# Main_Board.net
KiCad netlist of a schematic drawn in EAGLE
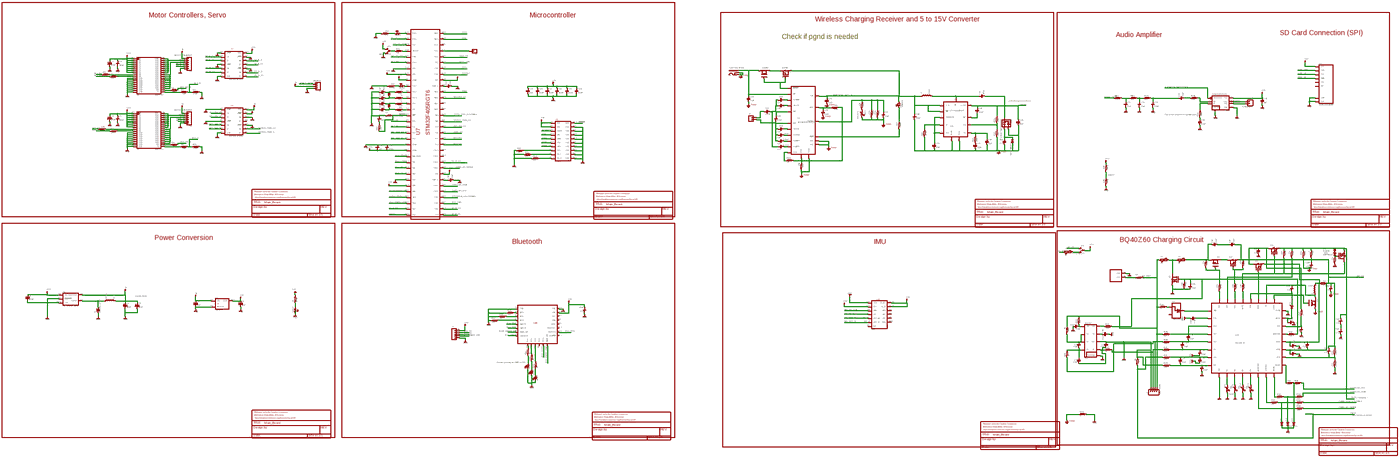
[diagram p0: schematic, sheet 1, overview]
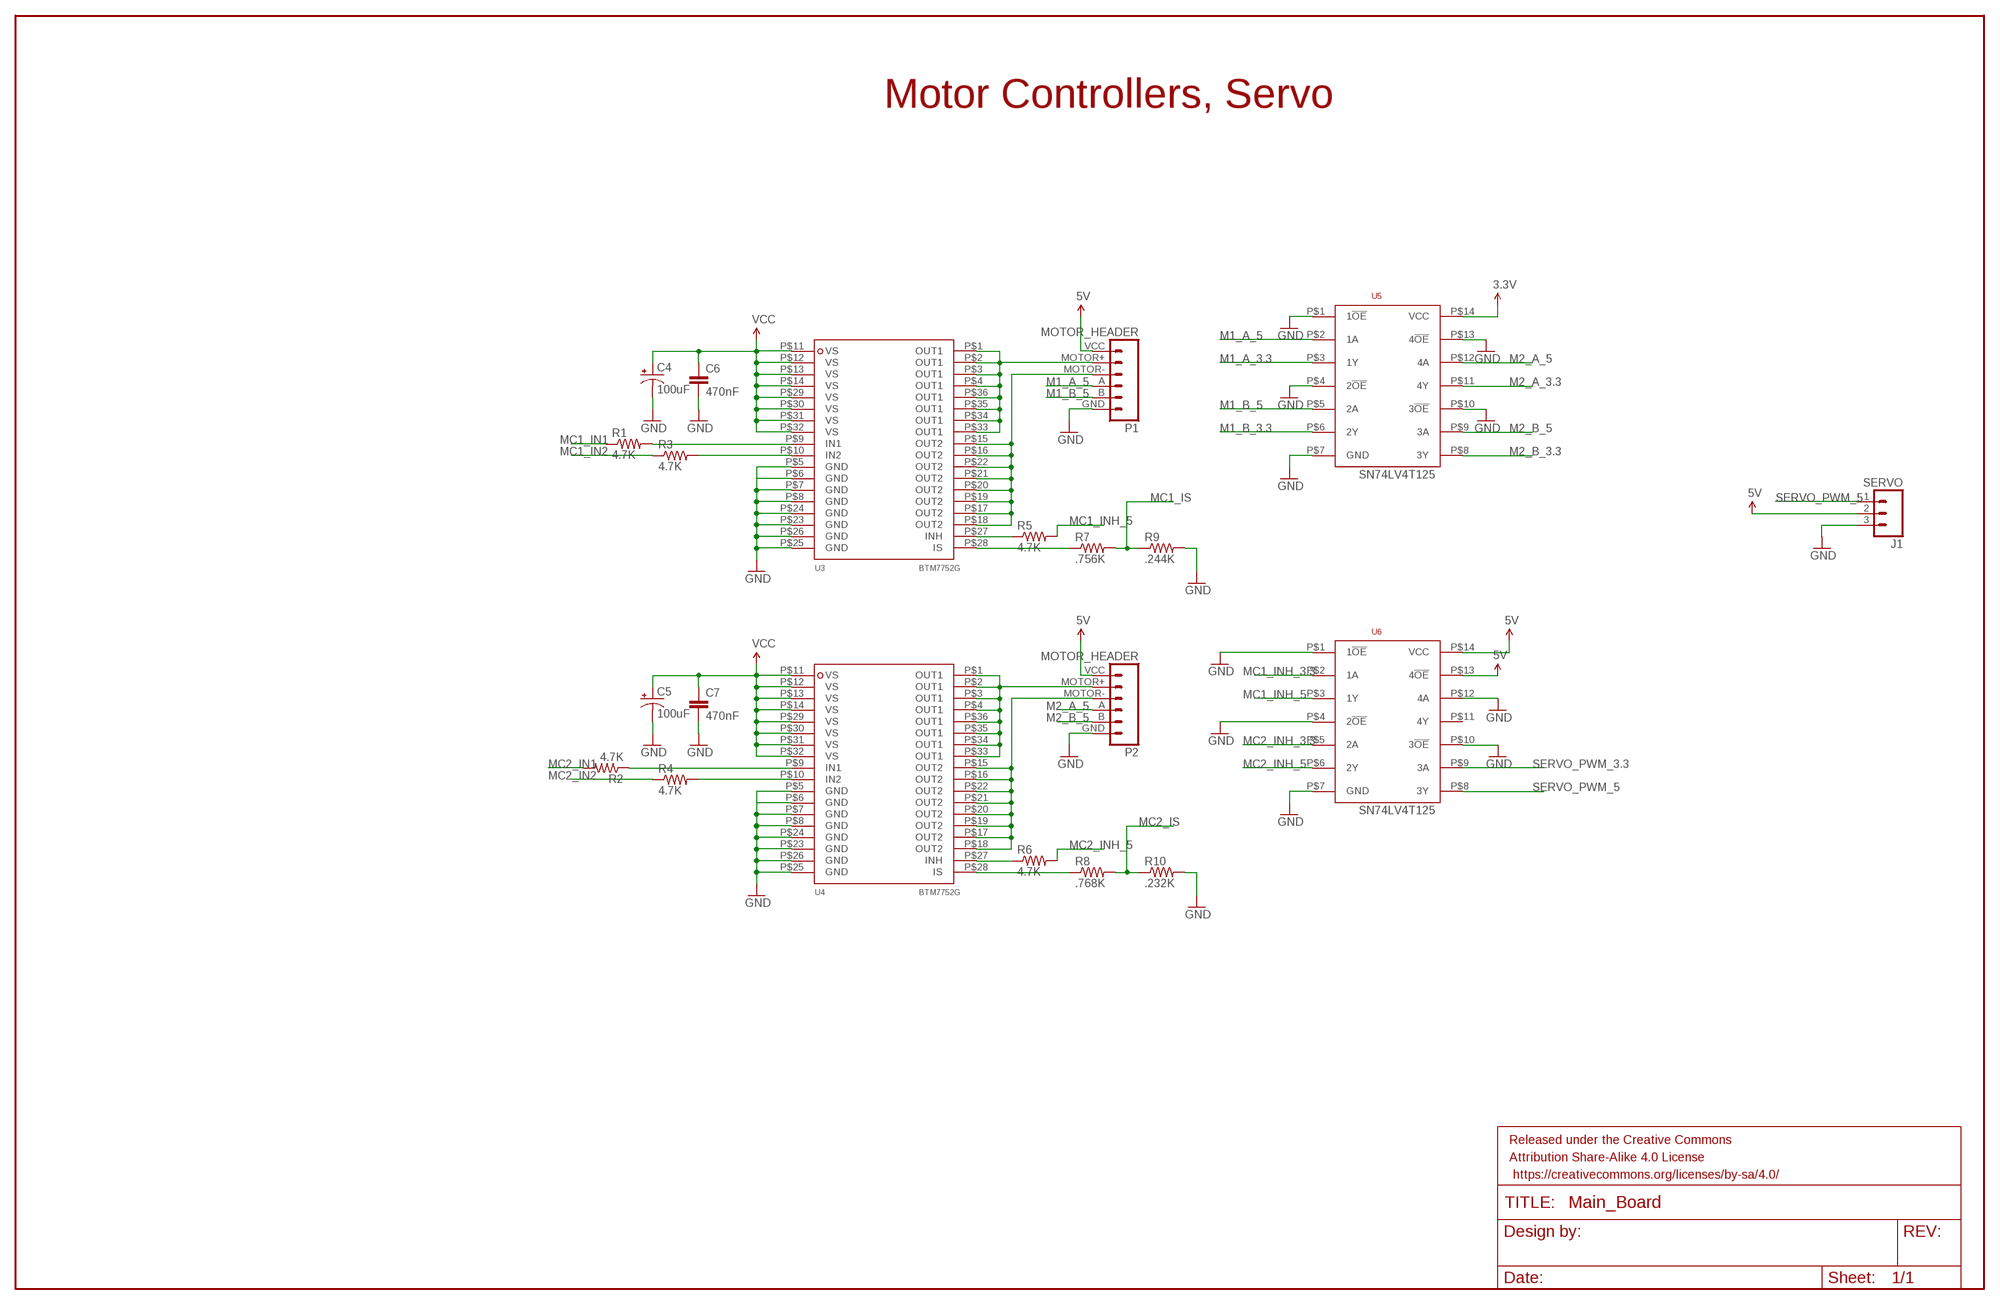
[diagram p1: schematic, sheet 1, part 1 of 8]
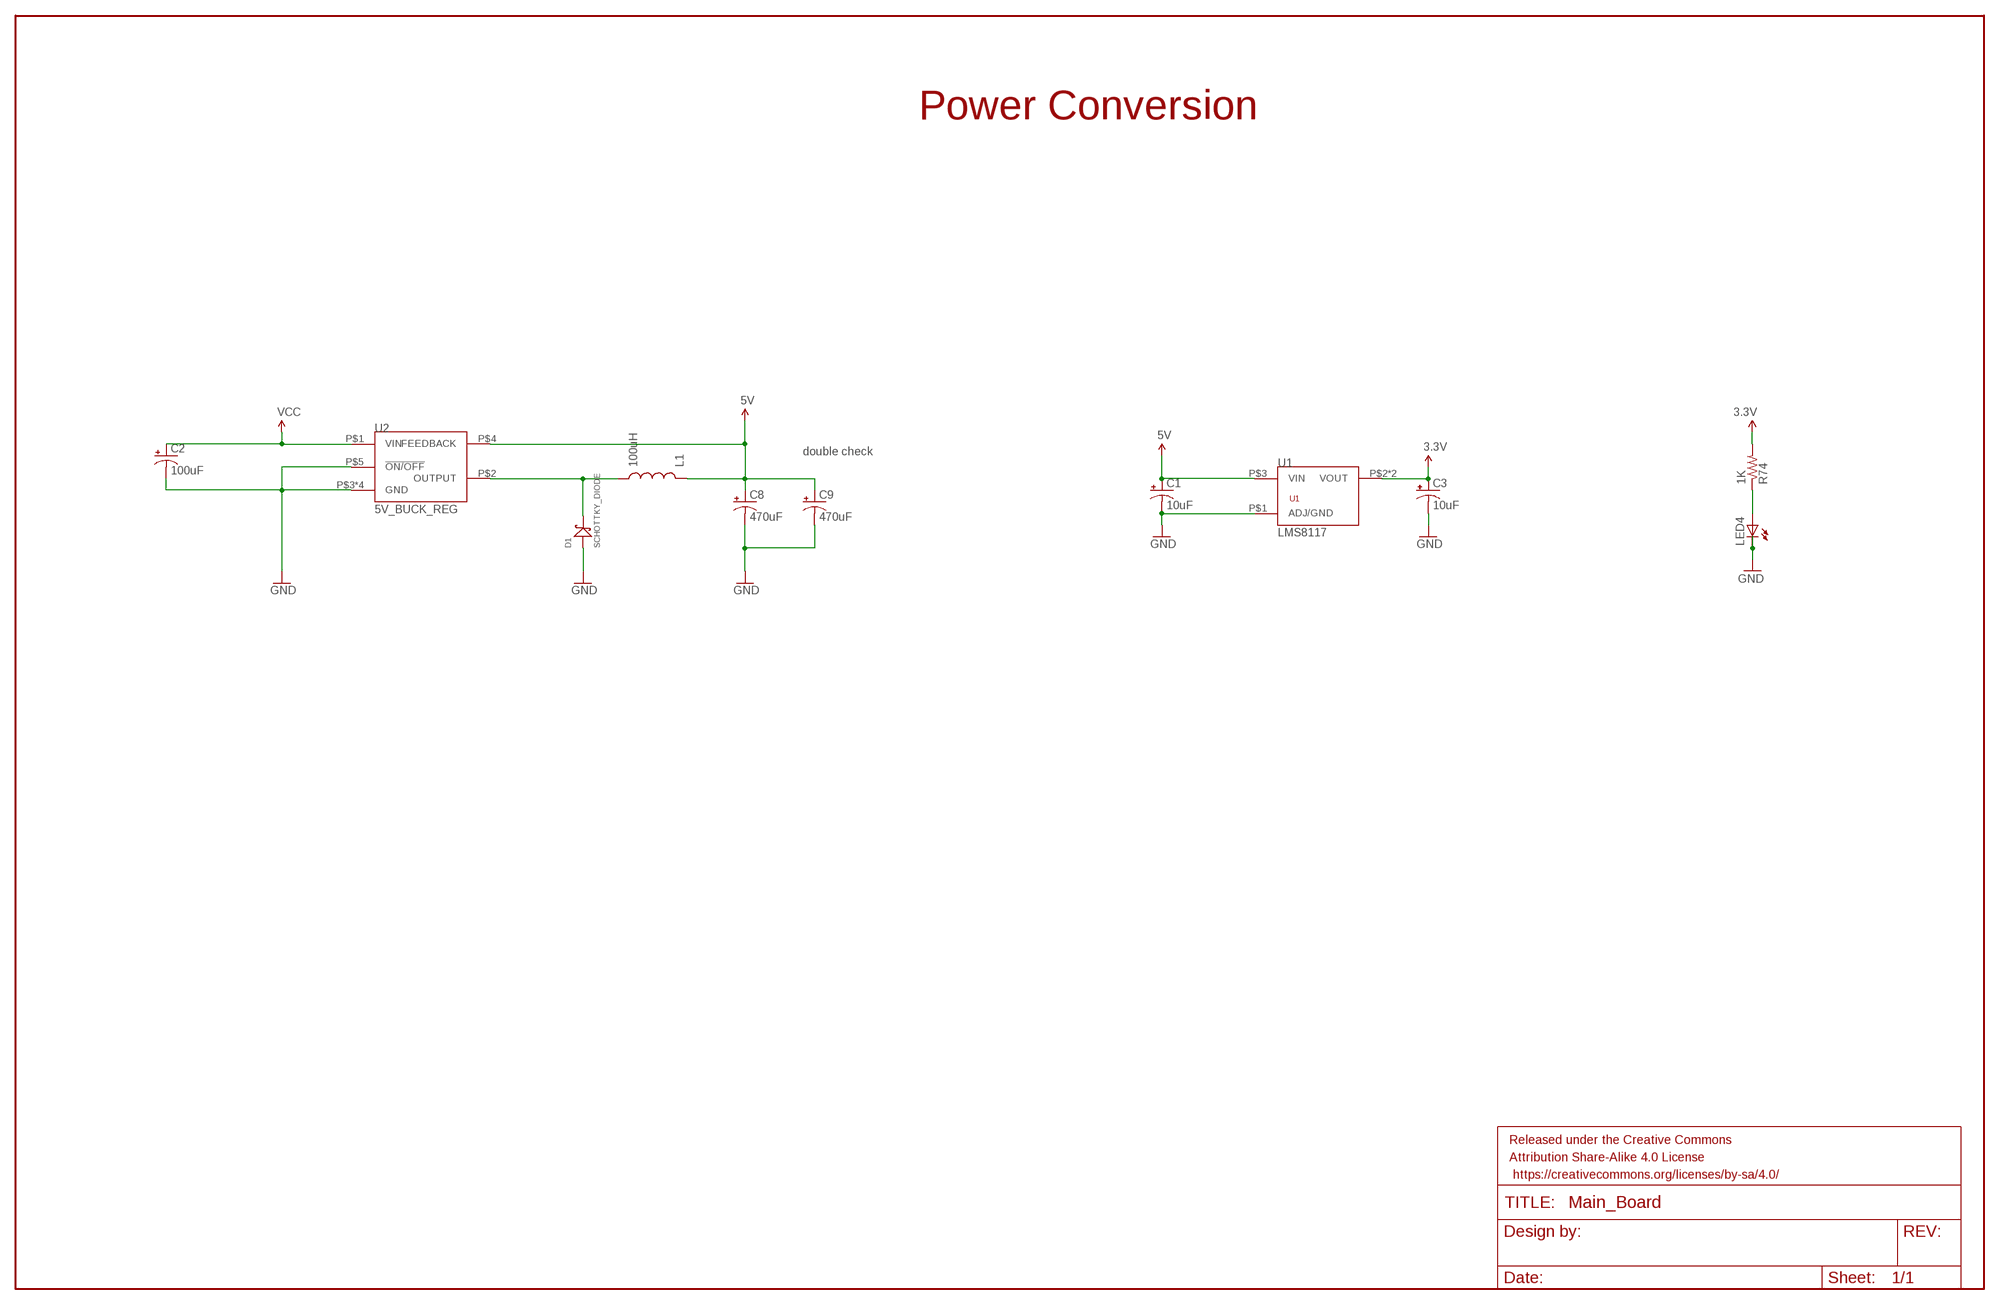
[diagram p2: schematic, sheet 1, part 2 of 8]
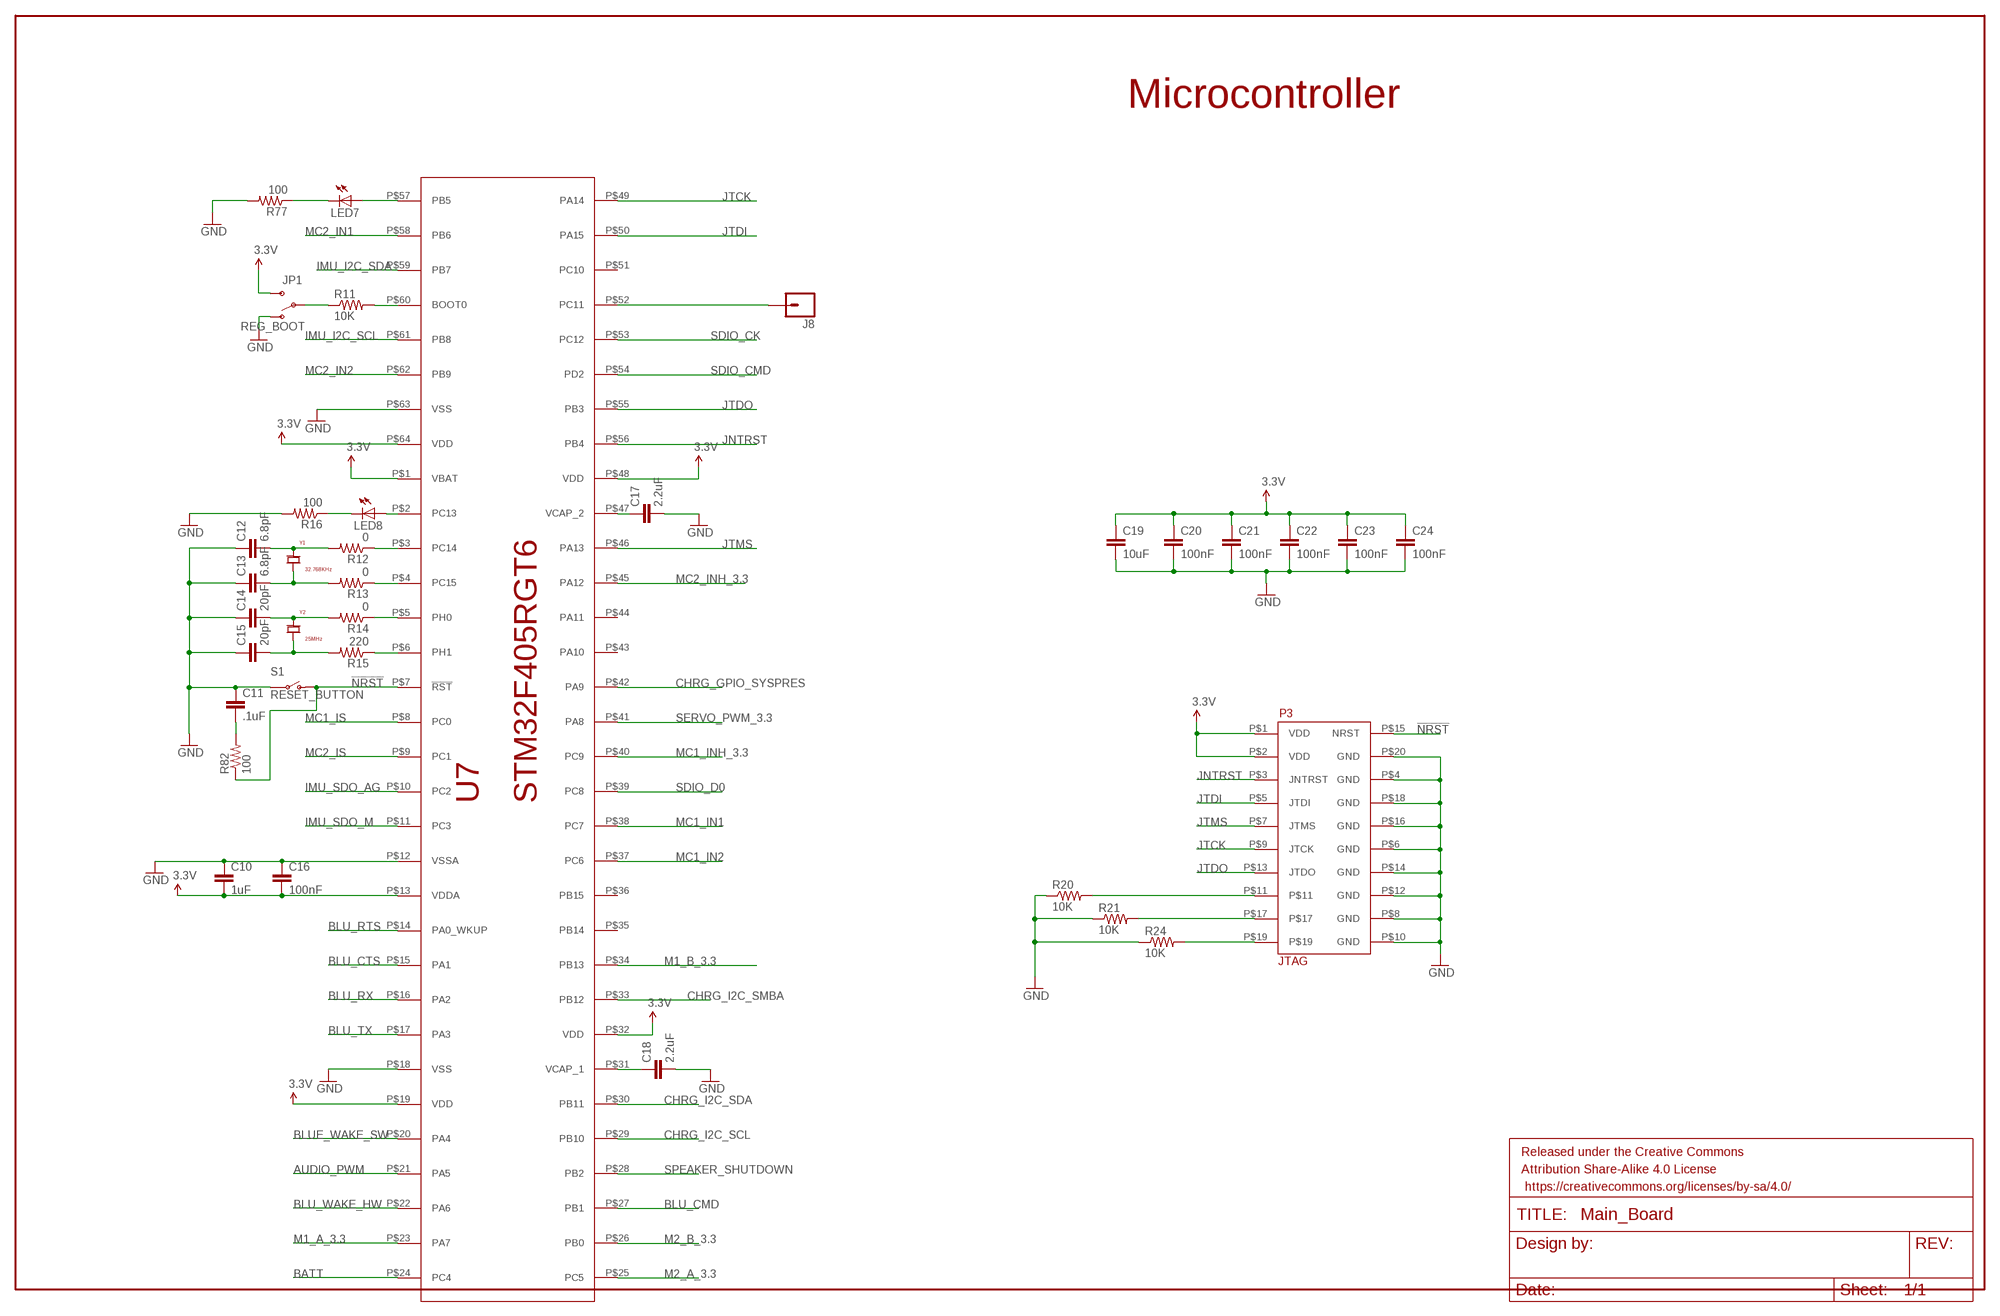
[diagram p3: schematic, sheet 1, part 3 of 8]
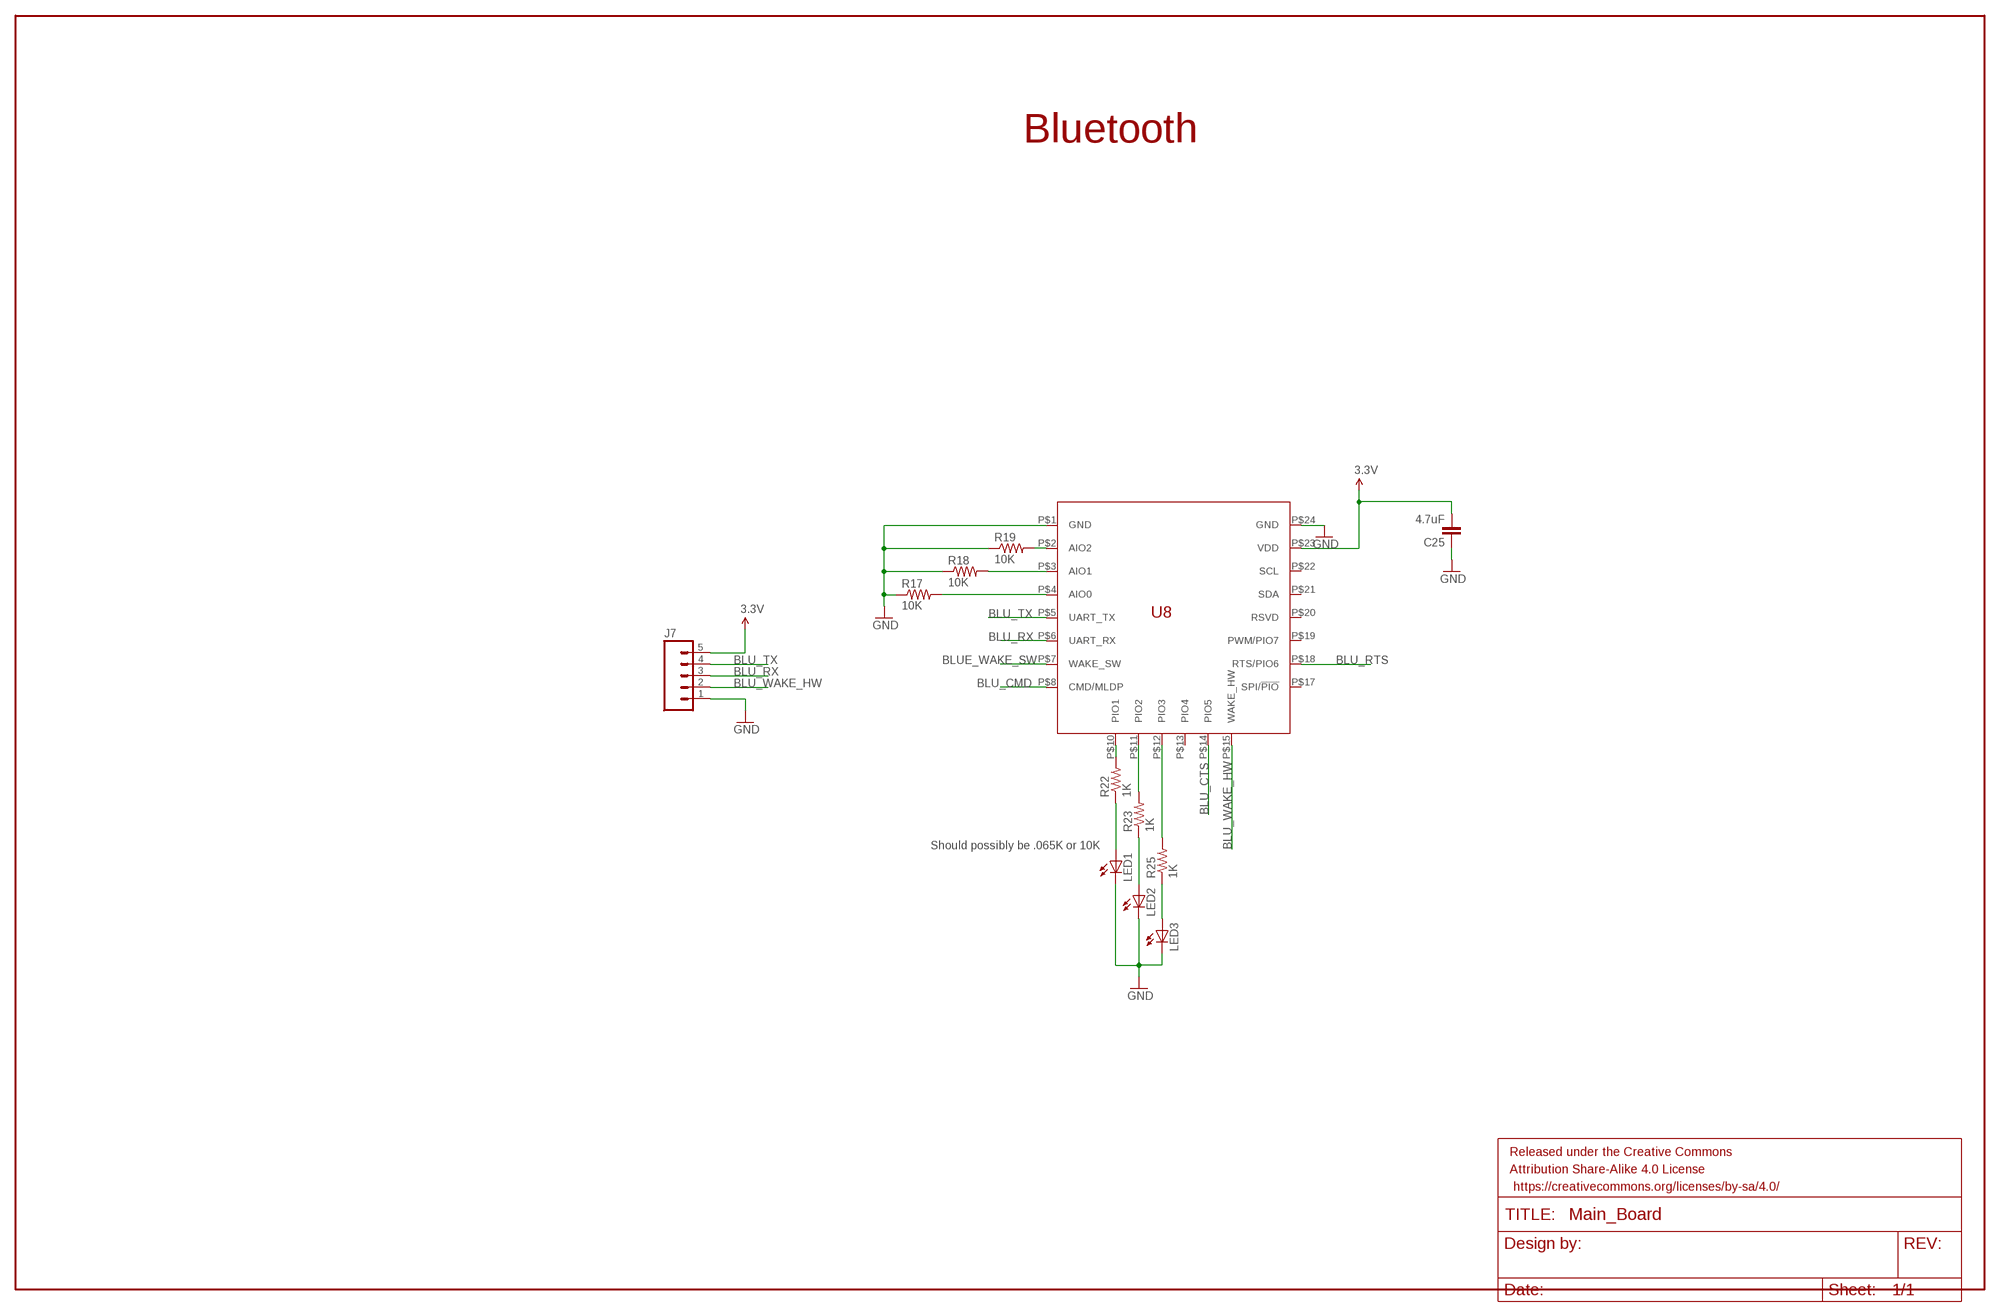
[diagram p4: schematic, sheet 1, part 4 of 8]
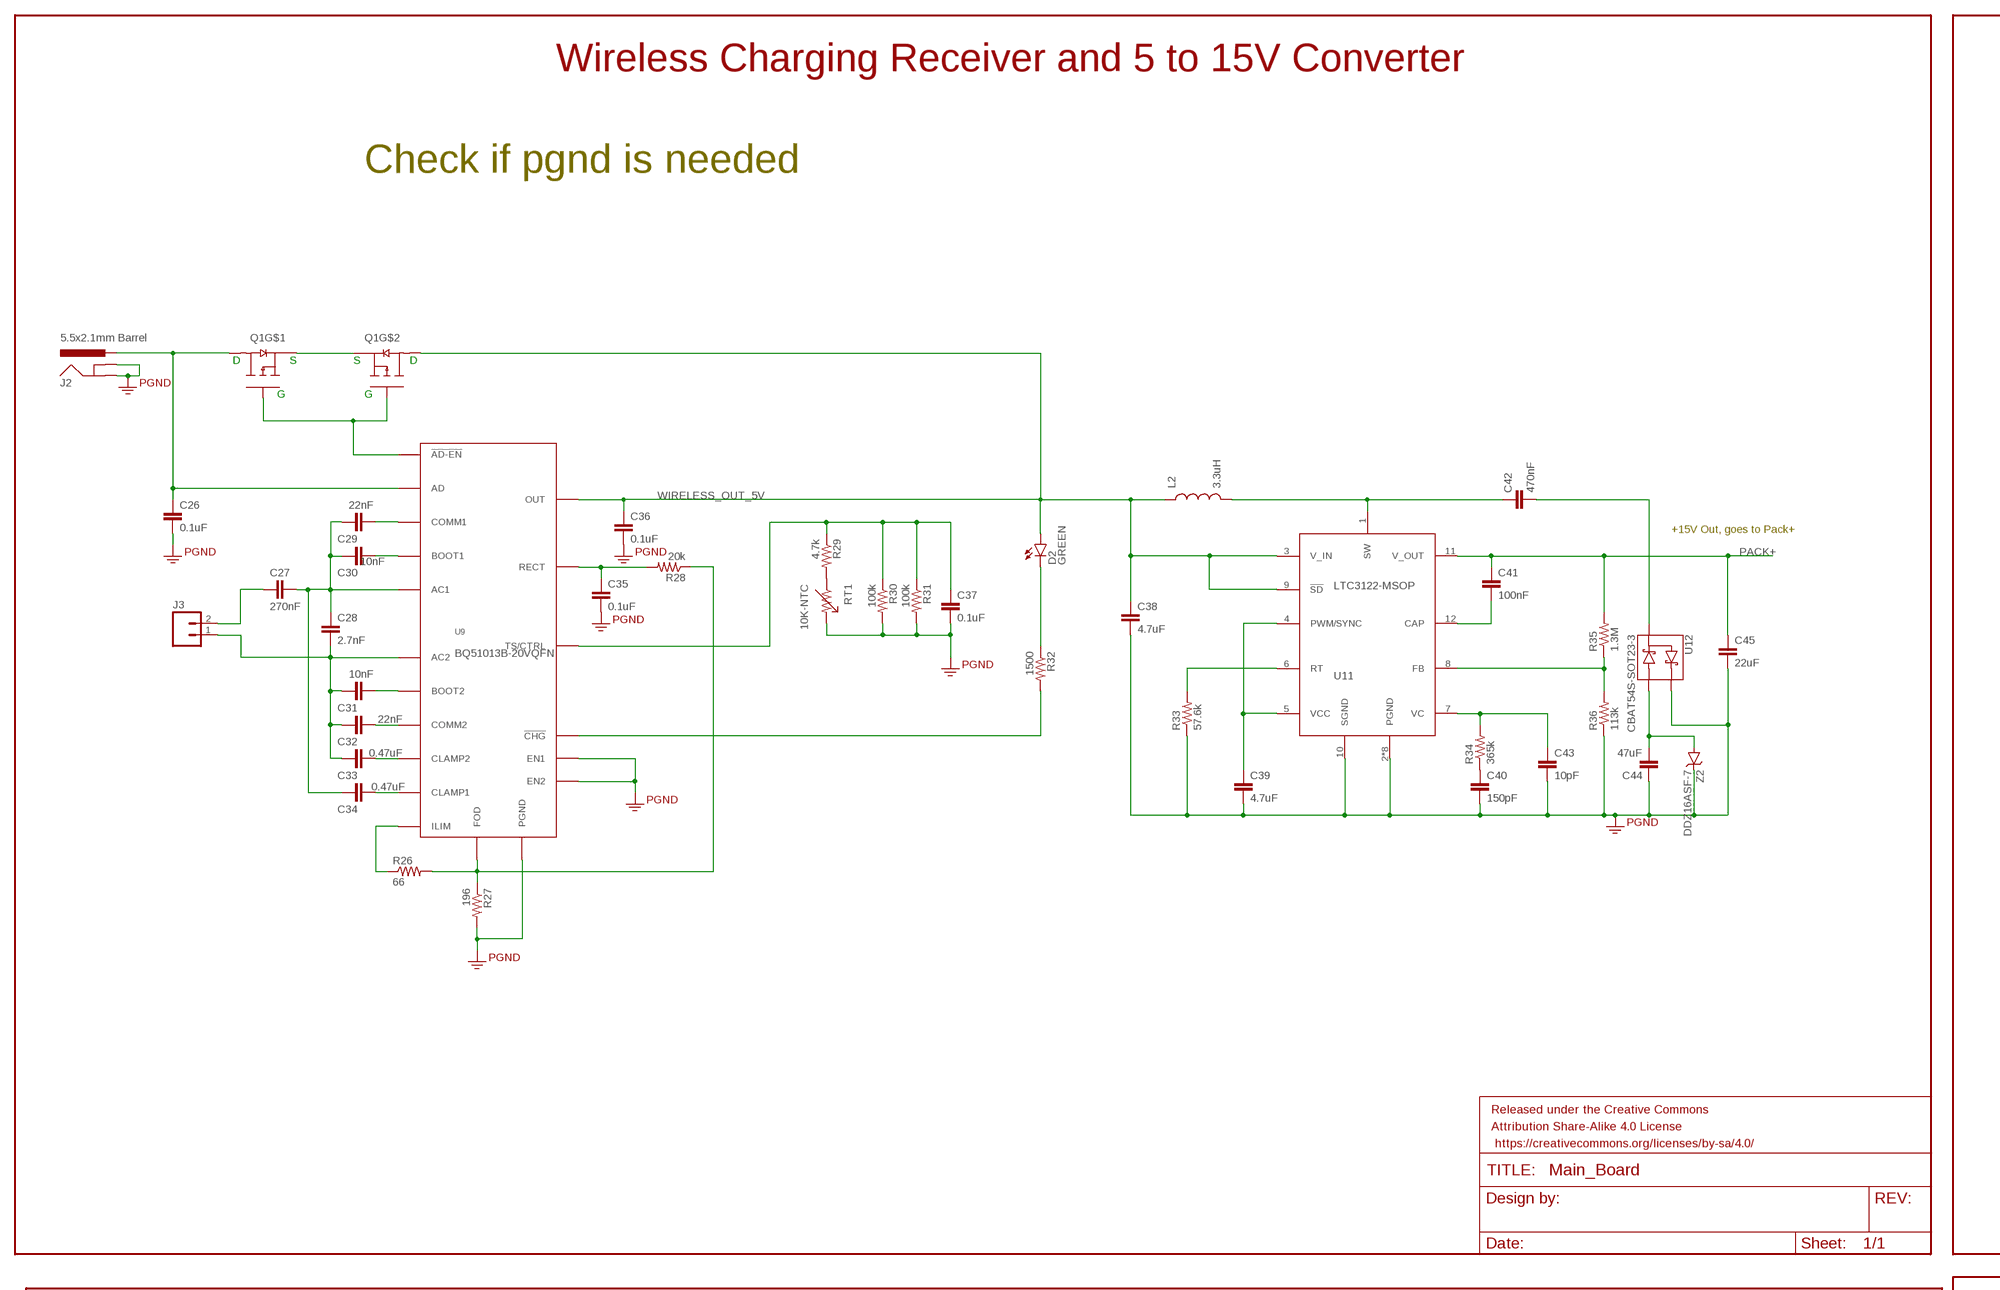
[diagram p5: schematic, sheet 1, part 5 of 8]
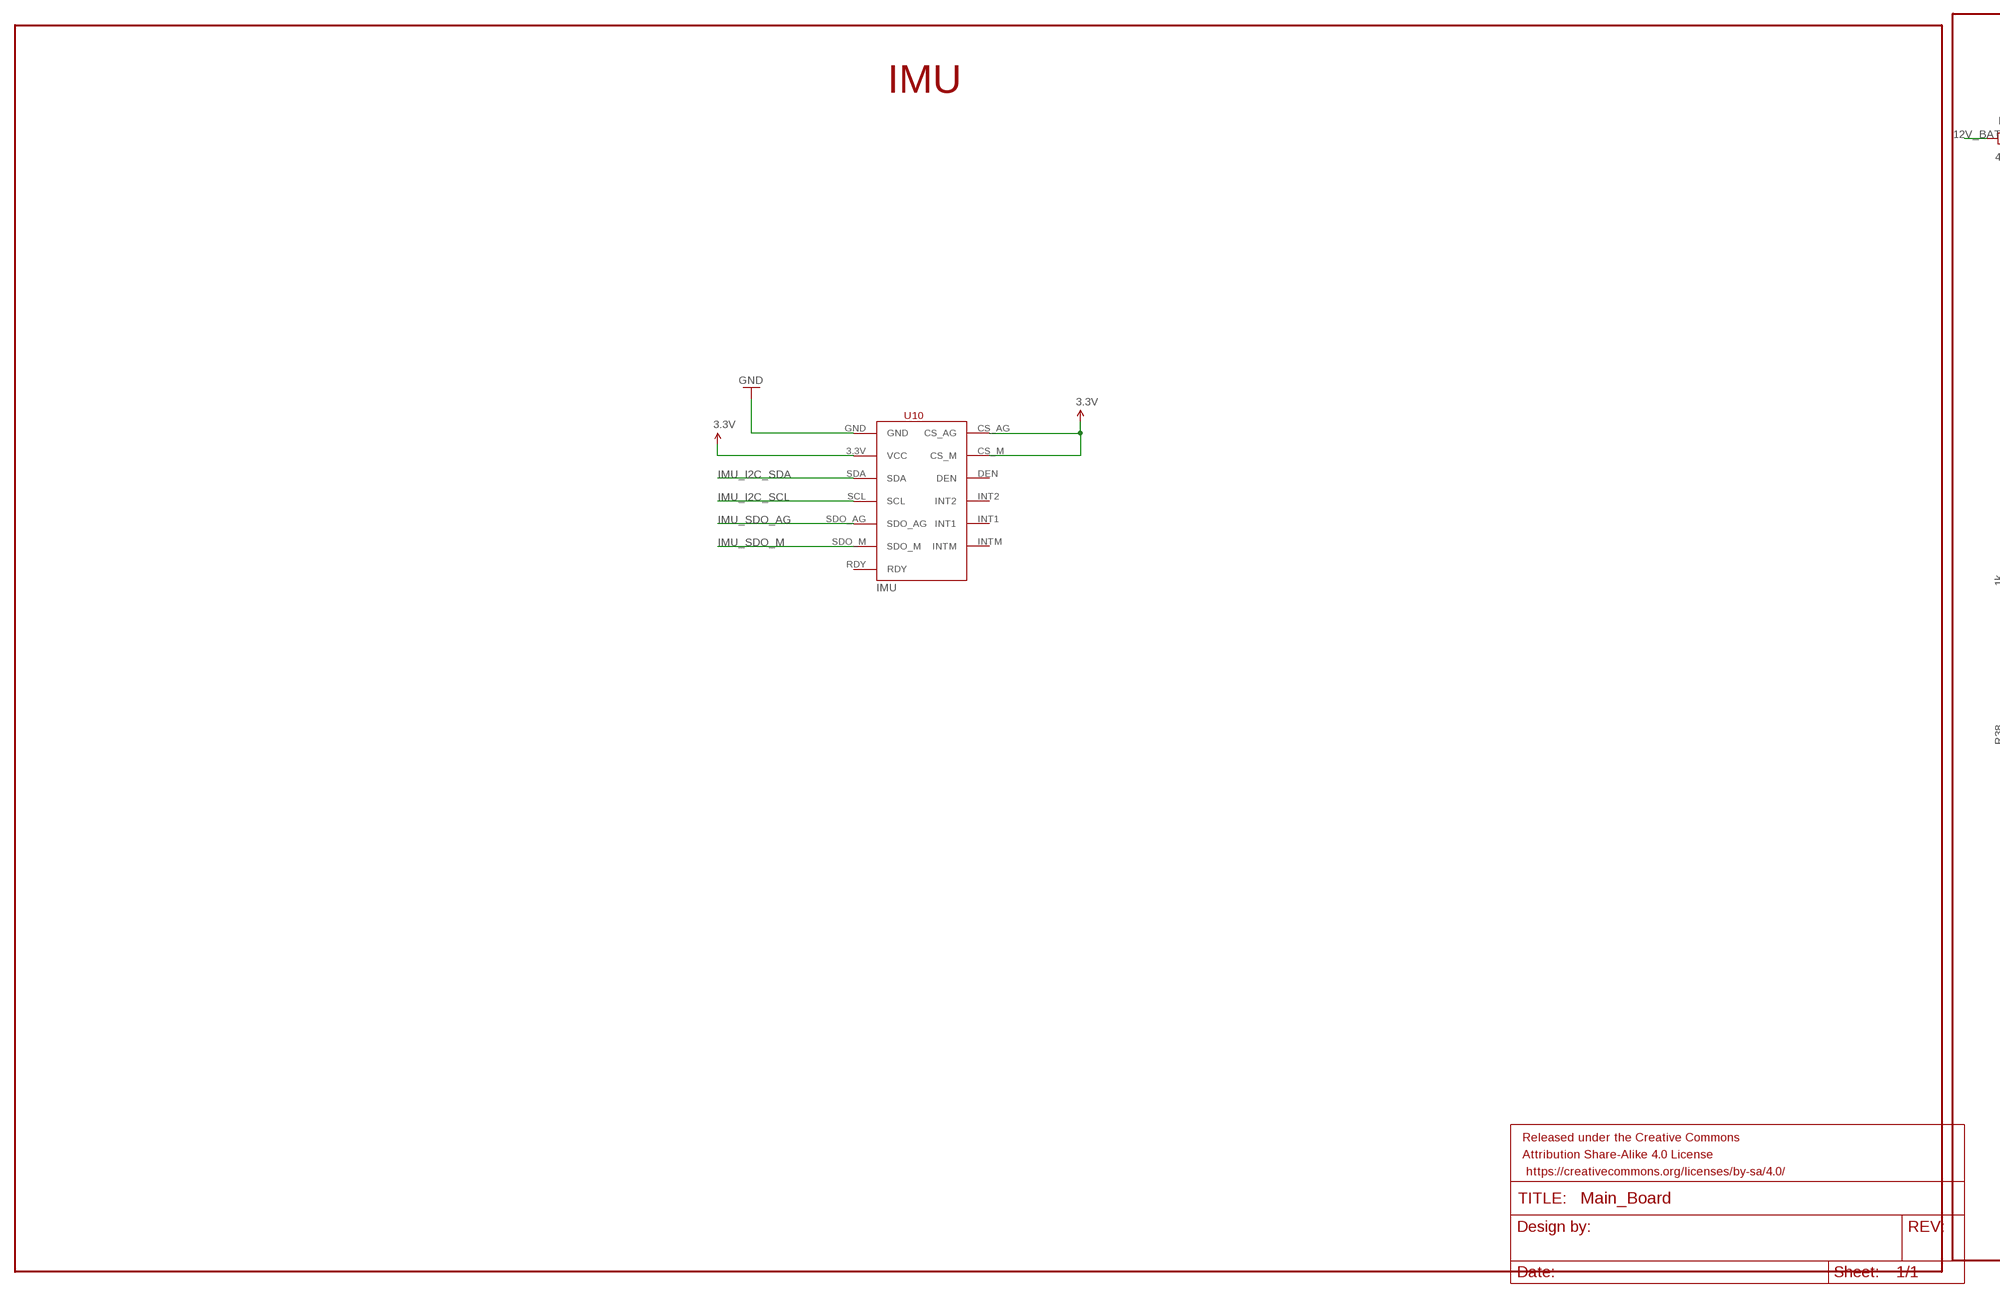
[diagram p6: schematic, sheet 1, part 6 of 8]
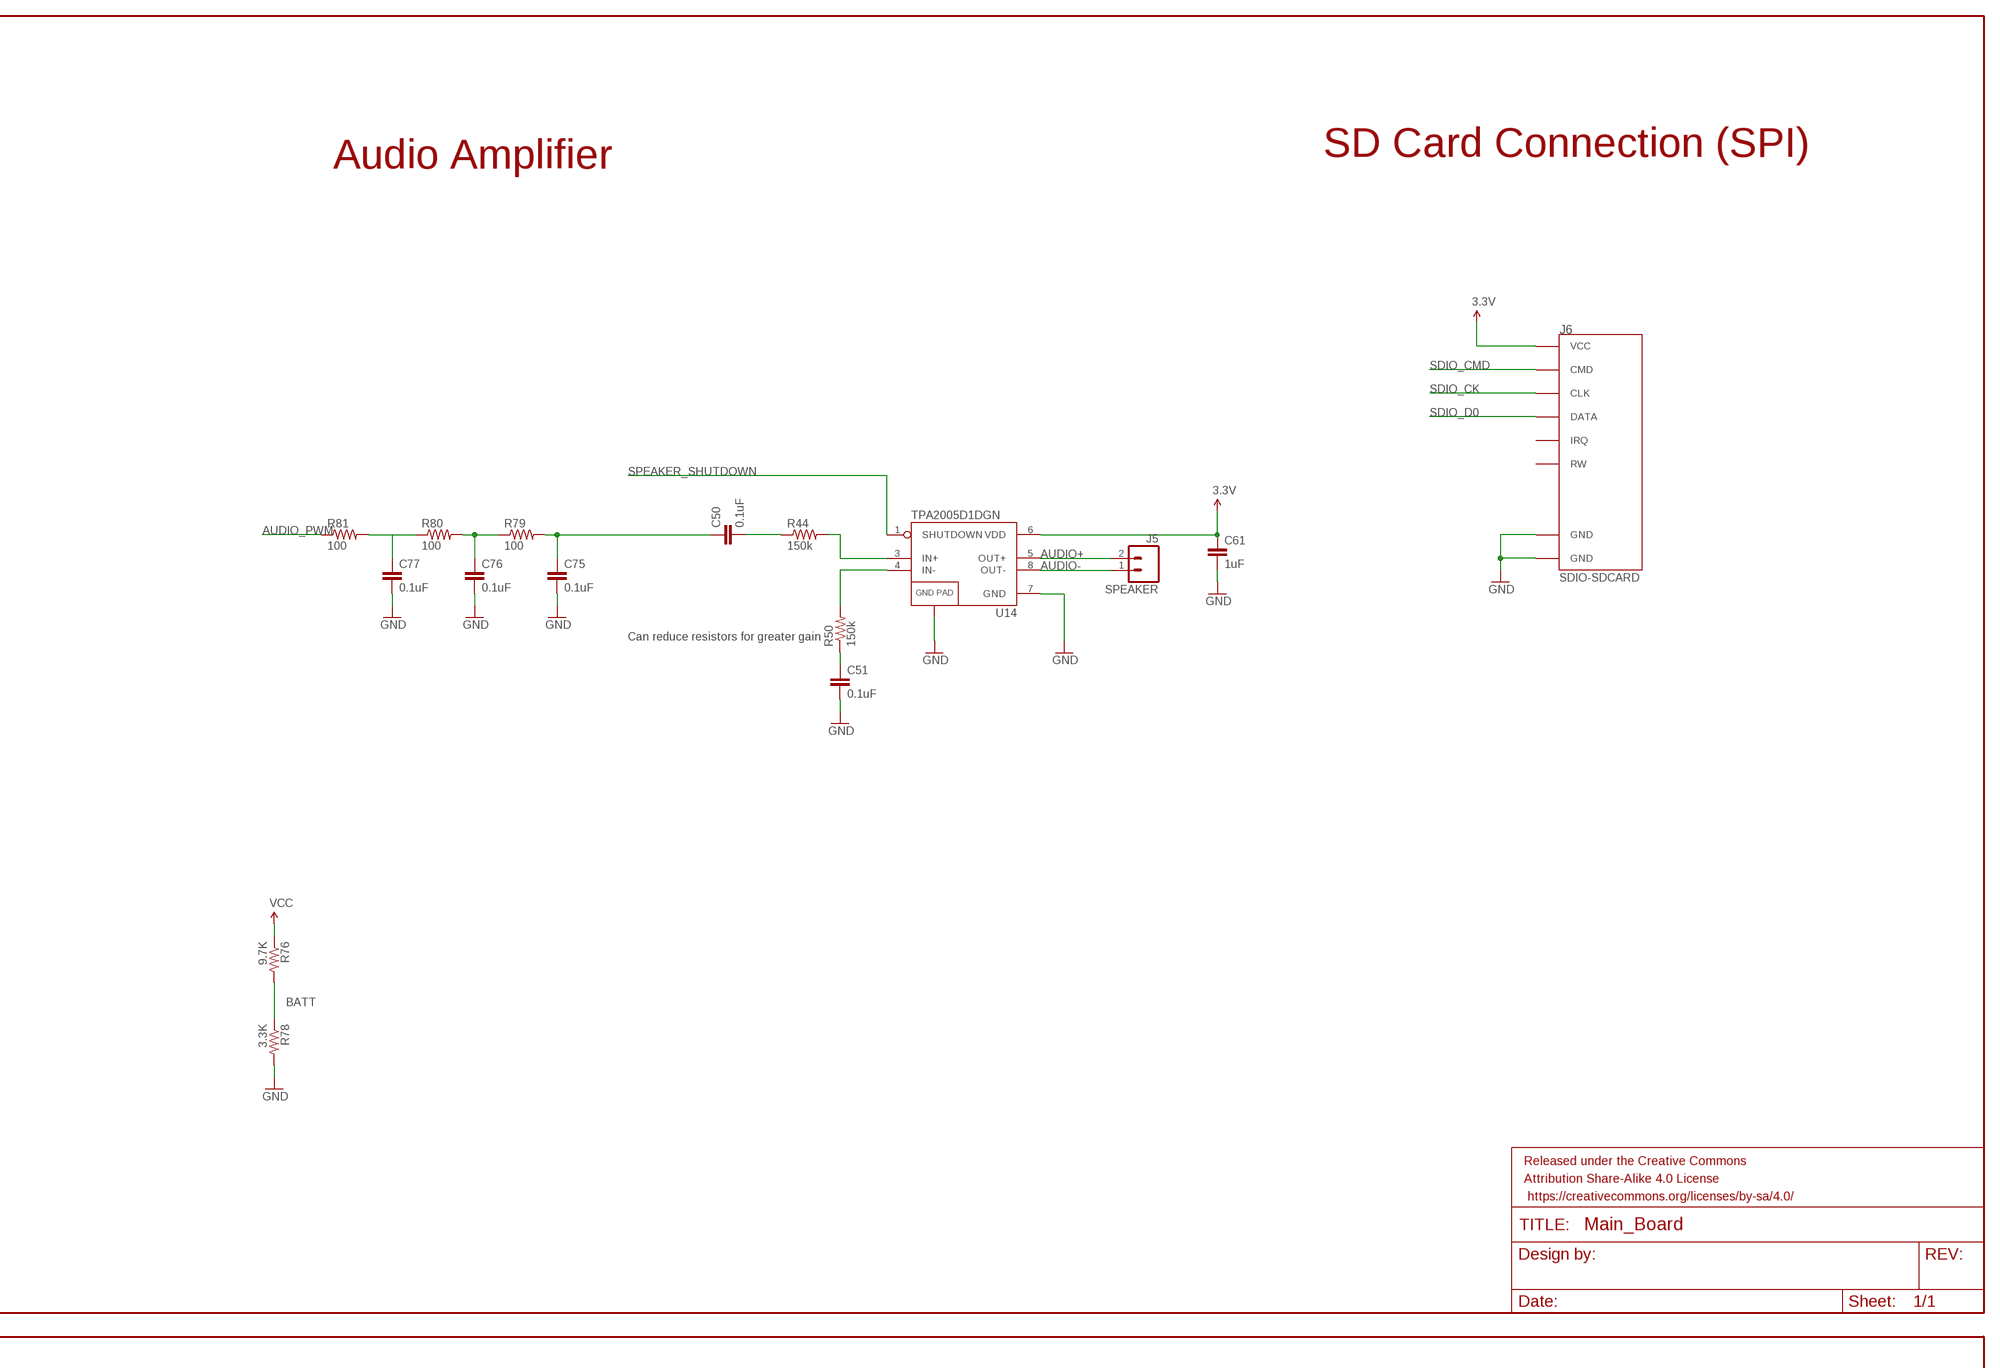
[diagram p7: schematic, sheet 1, part 7 of 8]
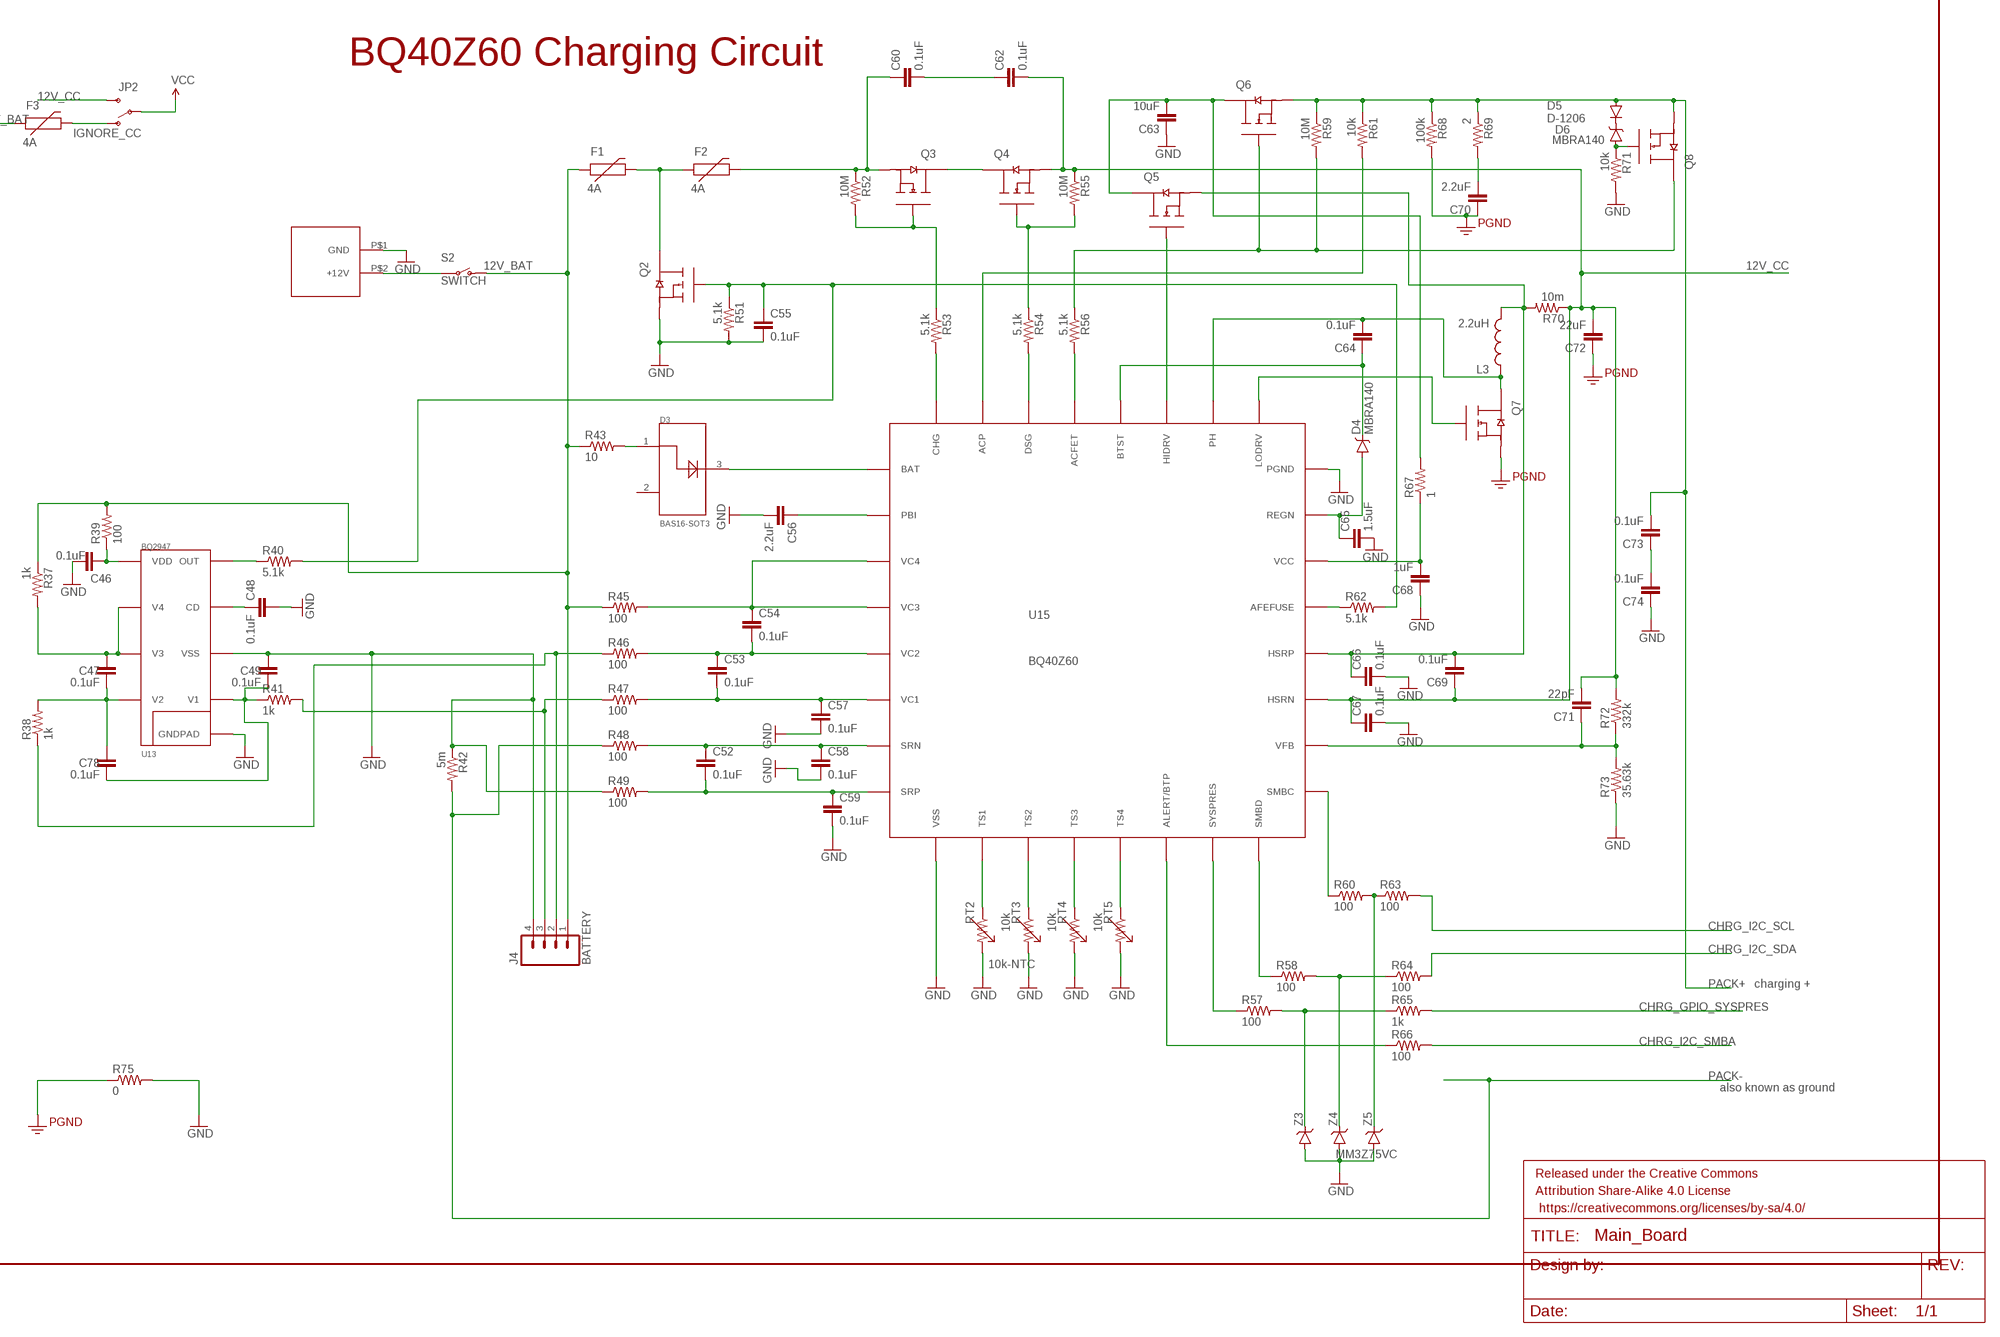
[diagram p8: schematic, sheet 1, part 8 of 8]

(export (version "E")
  (design (tool "Eeschema 10.0.6"))
  (components
    (comp (ref "C1")
      (value "10uF")
      (footprint "eagle-import:RADIAL_CAN_SMD-B")
      (libsource (lib "eagle-import") (part "CAP_POL_PANB"))
    )
    (comp (ref "C2")
      (value "100uF")
      (footprint "eagle-import:RADIAL_CAN_SMD-D8")
      (libsource (lib "eagle-import") (part "CAP_POL_PAN"))
    )
    (comp (ref "C3")
      (value "10uF")
      (footprint "eagle-import:RADIAL_CAN_SMD-B")
      (libsource (lib "eagle-import") (part "CAP_POL_PANB"))
    )
    (comp (ref "C4")
      (value "100uF")
      (footprint "eagle-import:RADIAL_CAN_SMD-D8")
      (libsource (lib "eagle-import") (part "CAP_POL_PAN"))
    )
    (comp (ref "C5")
      (value "100uF")
      (footprint "eagle-import:RADIAL_CAN_SMD-D8")
      (libsource (lib "eagle-import") (part "CAP_POL_PAN"))
    )
    (comp (ref "C6")
      (value "470nF")
      (footprint "eagle-import:0805")
      (libsource (lib "eagle-import") (part "CAP0805"))
    )
    (comp (ref "C7")
      (value "470nF")
      (footprint "eagle-import:0805")
      (libsource (lib "eagle-import") (part "CAP0805"))
    )
    (comp (ref "C8")
      (value "470uF")
      (footprint "eagle-import:RADIAL_CAN_SMD-G")
      (libsource (lib "eagle-import") (part "CAP_POL_PANG"))
    )
    (comp (ref "C9")
      (value "470uF")
      (footprint "eagle-import:RADIAL_CAN_SMD-G")
      (libsource (lib "eagle-import") (part "CAP_POL_PANG"))
    )
    (comp (ref "C10")
      (value "1uF")
      (footprint "eagle-import:0805")
      (libsource (lib "eagle-import") (part "CAP0805"))
    )
    (comp (ref "C11")
      (value ".1uF")
      (footprint "eagle-import:0805")
      (libsource (lib "eagle-import") (part "SparkFun-Passives_CAP0805"))
    )
    (comp (ref "C12")
      (value "6.8pF")
      (footprint "eagle-import:0805")
      (libsource (lib "eagle-import") (part "SparkFun-Passives_CAP0805"))
    )
    (comp (ref "C13")
      (value "6.8pF")
      (footprint "eagle-import:0805")
      (libsource (lib "eagle-import") (part "SparkFun-Passives_CAP0805"))
    )
    (comp (ref "C14")
      (value "20pF")
      (footprint "eagle-import:0805")
      (libsource (lib "eagle-import") (part "SparkFun-Passives_CAP0805"))
    )
    (comp (ref "C15")
      (value "20pF")
      (footprint "eagle-import:0805")
      (libsource (lib "eagle-import") (part "SparkFun-Passives_CAP0805"))
    )
    (comp (ref "C16")
      (value "100nF")
      (footprint "eagle-import:0805")
      (libsource (lib "eagle-import") (part "CAP0805"))
    )
    (comp (ref "C17")
      (value "2.2uF")
      (footprint "eagle-import:0805")
      (libsource (lib "eagle-import") (part "CAP0805"))
    )
    (comp (ref "C18")
      (value "2.2uF")
      (footprint "eagle-import:0805")
      (libsource (lib "eagle-import") (part "CAP0805"))
    )
    (comp (ref "C19")
      (value "10uF")
      (footprint "eagle-import:0805")
      (libsource (lib "eagle-import") (part "CAP0805"))
    )
    (comp (ref "C20")
      (value "100nF")
      (footprint "eagle-import:0805")
      (libsource (lib "eagle-import") (part "CAP0805"))
    )
    (comp (ref "C21")
      (value "100nF")
      (footprint "eagle-import:0805")
      (libsource (lib "eagle-import") (part "CAP0805"))
    )
    (comp (ref "C22")
      (value "100nF")
      (footprint "eagle-import:0805")
      (libsource (lib "eagle-import") (part "CAP0805"))
    )
    (comp (ref "C23")
      (value "100nF")
      (footprint "eagle-import:0805")
      (libsource (lib "eagle-import") (part "CAP0805"))
    )
    (comp (ref "C24")
      (value "100nF")
      (footprint "eagle-import:0805")
      (libsource (lib "eagle-import") (part "CAP0805"))
    )
    (comp (ref "C25")
      (value "4.7uF")
      (footprint "eagle-import:0805")
      (libsource (lib "eagle-import") (part "CAP0805"))
    )
    (comp (ref "C26")
      (value "0.1uF")
      (footprint "eagle-import:0805")
      (libsource (lib "eagle-import") (part "CAP0805"))
    )
    (comp (ref "C27")
      (value "270nF")
      (footprint "eagle-import:0805")
      (libsource (lib "eagle-import") (part "CAP0805"))
    )
    (comp (ref "C28")
      (value "2.7nF")
      (footprint "eagle-import:0805")
      (libsource (lib "eagle-import") (part "CAP0805"))
    )
    (comp (ref "C29")
      (value "22nF")
      (footprint "eagle-import:0805")
      (libsource (lib "eagle-import") (part "CAP0805"))
    )
    (comp (ref "C30")
      (value "10nF")
      (footprint "eagle-import:0805")
      (libsource (lib "eagle-import") (part "CAP0805"))
    )
    (comp (ref "C31")
      (value "10nF")
      (footprint "eagle-import:0805")
      (libsource (lib "eagle-import") (part "CAP0805"))
    )
    (comp (ref "C32")
      (value "22nF")
      (footprint "eagle-import:0805")
      (libsource (lib "eagle-import") (part "CAP0805"))
    )
    (comp (ref "C33")
      (value "0.47uF")
      (footprint "eagle-import:0805")
      (libsource (lib "eagle-import") (part "CAP0805"))
    )
    (comp (ref "C34")
      (value "0.47uF")
      (footprint "eagle-import:0805")
      (libsource (lib "eagle-import") (part "CAP0805"))
    )
    (comp (ref "C35")
      (value "0.1uF")
      (footprint "eagle-import:0805")
      (libsource (lib "eagle-import") (part "CAP0805"))
    )
    (comp (ref "C36")
      (value "0.1uF")
      (footprint "eagle-import:0805")
      (libsource (lib "eagle-import") (part "CAP0805"))
    )
    (comp (ref "C37")
      (value "0.1uF")
      (footprint "eagle-import:0805")
      (libsource (lib "eagle-import") (part "CAP0805"))
    )
    (comp (ref "C38")
      (value "4.7uF")
      (footprint "eagle-import:0805")
      (libsource (lib "eagle-import") (part "CAP0805"))
    )
    (comp (ref "C39")
      (value "4.7uF")
      (footprint "eagle-import:0805")
      (libsource (lib "eagle-import") (part "CAP0805"))
    )
    (comp (ref "C40")
      (value "150pF")
      (footprint "eagle-import:0805")
      (libsource (lib "eagle-import") (part "CAP0805"))
    )
    (comp (ref "C41")
      (value "100nF")
      (footprint "eagle-import:0805")
      (libsource (lib "eagle-import") (part "CAP0805"))
    )
    (comp (ref "C42")
      (value "470nF")
      (footprint "eagle-import:0805")
      (libsource (lib "eagle-import") (part "CAP0805"))
    )
    (comp (ref "C43")
      (value "10pF")
      (footprint "eagle-import:0805")
      (libsource (lib "eagle-import") (part "CAP0805"))
    )
    (comp (ref "C44")
      (value "47uF")
      (footprint "eagle-import:1206-CAP")
      (libsource (lib "eagle-import") (part "CAP-1206"))
    )
    (comp (ref "C45")
      (value "22uF")
      (footprint "eagle-import:0805")
      (libsource (lib "eagle-import") (part "CAP0805"))
    )
    (comp (ref "C46")
      (value "0.1uF")
      (footprint "eagle-import:0805")
      (libsource (lib "eagle-import") (part "CAP0805"))
    )
    (comp (ref "C47")
      (value "0.1uF")
      (footprint "eagle-import:0805")
      (libsource (lib "eagle-import") (part "CAP0805"))
    )
    (comp (ref "C48")
      (value "0.1uF")
      (footprint "eagle-import:0805")
      (libsource (lib "eagle-import") (part "CAP0805"))
    )
    (comp (ref "C49")
      (value "0.1uF")
      (footprint "eagle-import:0805")
      (libsource (lib "eagle-import") (part "CAP0805"))
    )
    (comp (ref "C50")
      (value "0.1uF")
      (footprint "eagle-import:0805")
      (libsource (lib "eagle-import") (part "CAP0805"))
    )
    (comp (ref "C51")
      (value "0.1uF")
      (footprint "eagle-import:0805")
      (libsource (lib "eagle-import") (part "CAP0805"))
    )
    (comp (ref "C52")
      (value "0.1uF")
      (footprint "eagle-import:0805")
      (libsource (lib "eagle-import") (part "CAP0805"))
    )
    (comp (ref "C53")
      (value "0.1uF")
      (footprint "eagle-import:0805")
      (libsource (lib "eagle-import") (part "CAP0805"))
    )
    (comp (ref "C54")
      (value "0.1uF")
      (footprint "eagle-import:0805")
      (libsource (lib "eagle-import") (part "CAP0805"))
    )
    (comp (ref "C55")
      (value "0.1uF")
      (footprint "eagle-import:0805")
      (libsource (lib "eagle-import") (part "CAP0805"))
    )
    (comp (ref "C56")
      (value "2.2uF")
      (footprint "eagle-import:0805")
      (libsource (lib "eagle-import") (part "CAP0805"))
    )
    (comp (ref "C57")
      (value "0.1uF")
      (footprint "eagle-import:0805")
      (libsource (lib "eagle-import") (part "CAP0805"))
    )
    (comp (ref "C58")
      (value "0.1uF")
      (footprint "eagle-import:0805")
      (libsource (lib "eagle-import") (part "CAP0805"))
    )
    (comp (ref "C59")
      (value "0.1uF")
      (footprint "eagle-import:0805")
      (libsource (lib "eagle-import") (part "CAP0805"))
    )
    (comp (ref "C60")
      (value "0.1uF")
      (footprint "eagle-import:0805")
      (libsource (lib "eagle-import") (part "CAP0805"))
    )
    (comp (ref "C61")
      (value "1uF")
      (footprint "eagle-import:0805")
      (libsource (lib "eagle-import") (part "CAP0805"))
    )
    (comp (ref "C62")
      (value "0.1uF")
      (footprint "eagle-import:0805")
      (libsource (lib "eagle-import") (part "CAP0805"))
    )
    (comp (ref "C63")
      (value "10uF")
      (footprint "eagle-import:0805")
      (libsource (lib "eagle-import") (part "CAP0805"))
    )
    (comp (ref "C64")
      (value "0.1uF")
      (footprint "eagle-import:0805")
      (libsource (lib "eagle-import") (part "CAP0805"))
    )
    (comp (ref "C65")
      (value "1.5uF")
      (footprint "eagle-import:0805")
      (libsource (lib "eagle-import") (part "CAP0805"))
    )
    (comp (ref "C66")
      (value "0.1uF")
      (footprint "eagle-import:0805")
      (libsource (lib "eagle-import") (part "CAP0805"))
    )
    (comp (ref "C67")
      (value "0.1uF")
      (footprint "eagle-import:0805")
      (libsource (lib "eagle-import") (part "CAP0805"))
    )
    (comp (ref "C68")
      (value "1uF")
      (footprint "eagle-import:0805")
      (libsource (lib "eagle-import") (part "CAP0805"))
    )
    (comp (ref "C69")
      (value "0.1uF")
      (footprint "eagle-import:0805")
      (libsource (lib "eagle-import") (part "CAP0805"))
    )
    (comp (ref "C70")
      (value "2.2uF")
      (footprint "eagle-import:0805")
      (libsource (lib "eagle-import") (part "CAP0805"))
    )
    (comp (ref "C71")
      (value "22pF")
      (footprint "eagle-import:0805")
      (libsource (lib "eagle-import") (part "CAP0805"))
    )
    (comp (ref "C72")
      (value "22uF")
      (footprint "eagle-import:0805")
      (libsource (lib "eagle-import") (part "CAP0805"))
    )
    (comp (ref "C73")
      (value "0.1uF")
      (footprint "eagle-import:0805")
      (libsource (lib "eagle-import") (part "CAP0805"))
    )
    (comp (ref "C74")
      (value "0.1uF")
      (footprint "eagle-import:0805")
      (libsource (lib "eagle-import") (part "CAP0805"))
    )
    (comp (ref "C75")
      (value "0.1uF")
      (footprint "eagle-import:0805")
      (libsource (lib "eagle-import") (part "CAP0805"))
    )
    (comp (ref "C76")
      (value "0.1uF")
      (footprint "eagle-import:0805")
      (libsource (lib "eagle-import") (part "CAP0805"))
    )
    (comp (ref "C77")
      (value "0.1uF")
      (footprint "eagle-import:0805")
      (libsource (lib "eagle-import") (part "CAP0805"))
    )
    (comp (ref "C78")
      (value "0.1uF")
      (footprint "eagle-import:0805")
      (libsource (lib "eagle-import") (part "CAP0805"))
    )
    (comp (ref "D1")
      (value "SCHOTTKY_DIODE")
      (footprint "eagle-import:DO-214AB2")
      (libsource (lib "eagle-import") (part "SCHOTTKY_DIODE"))
    )
    (comp (ref "D2")
      (value "GREEN")
      (footprint "eagle-import:LED-0603")
      (libsource (lib "eagle-import") (part "LED-BLUE0603"))
    )
    (comp (ref "D3")
      (value "BAS16-SOT3")
      (footprint "eagle-import:SOT23-3")
      (libsource (lib "eagle-import") (part "BAS16-SOT3"))
    )
    (comp (ref "D4")
      (value "MBRA140")
      (footprint "eagle-import:SMA-DIODE")
      (libsource (lib "eagle-import") (part "MBRA140"))
    )
    (comp (ref "D5")
      (value "D-1206")
      (footprint "eagle-import:1206-DIODE")
      (libsource (lib "eagle-import") (part "D-1206"))
    )
    (comp (ref "D6")
      (value "MBRA140")
      (footprint "eagle-import:SMA-DIODE")
      (libsource (lib "eagle-import") (part "DIODE-SCHOTTKY-MBRA140"))
    )
    (comp (ref "F1")
      (value "4A")
      (footprint "eagle-import:PTC-2920")
      (libsource (lib "eagle-import") (part "F2875CT-ND"))
    )
    (comp (ref "F2")
      (value "4A")
      (footprint "eagle-import:PTC-2920")
      (libsource (lib "eagle-import") (part "F2875CT-ND"))
    )
    (comp (ref "F3")
      (value "4A")
      (footprint "eagle-import:PTC-2920")
      (libsource (lib "eagle-import") (part "F2875CT-ND"))
    )
    (comp (ref "FRAME1")
      (value "FRAME-LEDGER")
      (footprint "eagle-import:CREATIVE_COMMONS")
      (libsource (lib "eagle-import") (part "FRAME-LEDGER"))
    )
    (comp (ref "FRAME2")
      (value "FRAME-LEDGER")
      (footprint "eagle-import:CREATIVE_COMMONS")
      (libsource (lib "eagle-import") (part "FRAME-LEDGER"))
    )
    (comp (ref "FRAME3")
      (value "FRAME-LEDGER")
      (footprint "eagle-import:CREATIVE_COMMONS")
      (libsource (lib "eagle-import") (part "FRAME-LEDGER"))
    )
    (comp (ref "FRAME4")
      (value "FRAME-LEDGER")
      (footprint "eagle-import:CREATIVE_COMMONS")
      (libsource (lib "eagle-import") (part "FRAME-LEDGER"))
    )
    (comp (ref "FRAME5")
      (value "FRAME-LEDGER")
      (footprint "eagle-import:CREATIVE_COMMONS")
      (libsource (lib "eagle-import") (part "FRAME-LEDGER"))
    )
    (comp (ref "FRAME6")
      (value "FRAME-LEDGER")
      (footprint "eagle-import:CREATIVE_COMMONS")
      (libsource (lib "eagle-import") (part "FRAME-LEDGER"))
    )
    (comp (ref "FRAME7")
      (value "FRAME-LEDGER")
      (footprint "eagle-import:CREATIVE_COMMONS")
      (libsource (lib "eagle-import") (part "FRAME-LEDGER"))
    )
    (comp (ref "FRAME8")
      (value "FRAME-LEDGER")
      (footprint "eagle-import:CREATIVE_COMMONS")
      (libsource (lib "eagle-import") (part "FRAME-LEDGER"))
    )
    (comp (ref "J1")
      (value "SERVO")
      (footprint "eagle-import:1X03")
      (libsource (lib "eagle-import") (part "M03PTH"))
    )
    (comp (ref "J2")
      (value "5.5x2.1mm Barrel")
      (footprint "eagle-import:POWER_JACK_SMD")
      (libsource (lib "eagle-import") (part "POWER_JACKSMD"))
    )
    (comp (ref "J3")
      (value "2-PIN-JUMPER")
      (footprint "eagle-import:JST-2-PTH-VERT")
      (libsource (lib "eagle-import") (part "2-PIN-JUMPER"))
    )
    (comp (ref "J4")
      (value "BATTERY")
      (footprint "eagle-import:JST-4-PTH-VERT")
      (libsource (lib "eagle-import") (part "JST-XH-04"))
    )
    (comp (ref "J5")
      (value "SPEAKER")
      (footprint "eagle-import:JST-2-PTH-VERT")
      (libsource (lib "eagle-import") (part "2-PIN-JUMPER"))
    )
    (comp (ref "J6")
      (value "SDIO-SDCARD")
      (footprint "eagle-import:SD-5738")
      (libsource (lib "eagle-import") (part "SDIO-SDCARD"))
    )
    (comp (ref "J7")
      (value "M05PTH")
      (footprint "eagle-import:1X05")
      (libsource (lib "eagle-import") (part "M05PTH"))
    )
    (comp (ref "J8")
      (value "M01PTH_NO_SILK_YES_STOP")
      (footprint "eagle-import:1X01_NO_SILK")
      (libsource (lib "eagle-import") (part "M01PTH_NO_SILK_YES_STOP"))
    )
    (comp (ref "JP1")
      (value "REG_BOOT")
      (footprint "eagle-import:1X03")
      (libsource (lib "eagle-import") (part "SPDT_JUMPER"))
    )
    (comp (ref "JP2")
      (value "IGNORE_CC")
      (footprint "eagle-import:1X03")
      (libsource (lib "eagle-import") (part "SPDT_JUMPER"))
    )
    (comp (ref "L1")
      (value "100uH")
      (footprint "eagle-import:SRN8040")
      (libsource (lib "eagle-import") (part "SRN840-101M"))
    )
    (comp (ref "L2")
      (value "3.3uH")
      (footprint "eagle-import:SPM6530")
      (libsource (lib "eagle-import") (part "INDUCTOR-SPM6530"))
    )
    (comp (ref "L3")
      (value "2.2uH")
      (footprint "eagle-import:SPM6530")
      (libsource (lib "eagle-import") (part "INDUCTOR-SPM6530"))
    )
    (comp (ref "LED1")
      (value "LED1206")
      (footprint "eagle-import:LED-1206")
      (libsource (lib "eagle-import") (part "LED1206"))
    )
    (comp (ref "LED2")
      (value "LED1206")
      (footprint "eagle-import:LED-1206")
      (libsource (lib "eagle-import") (part "LED1206"))
    )
    (comp (ref "LED3")
      (value "LED1206")
      (footprint "eagle-import:LED-1206")
      (libsource (lib "eagle-import") (part "LED1206"))
    )
    (comp (ref "LED4")
      (value "LED1206")
      (footprint "eagle-import:LED-1206")
      (libsource (lib "eagle-import") (part "LED1206"))
    )
    (comp (ref "LED7")
      (value "LED1206")
      (footprint "eagle-import:LED-1206")
      (libsource (lib "eagle-import") (part "LED1206"))
    )
    (comp (ref "LED8")
      (value "LED1206")
      (footprint "eagle-import:LED-1206")
      (libsource (lib "eagle-import") (part "LED1206"))
    )
    (comp (ref "P1")
      (value "MOTOR_HEADER")
      (footprint "eagle-import:1X06")
      (libsource (lib "eagle-import") (part "MOTOR_HEADER"))
    )
    (comp (ref "P2")
      (value "MOTOR_HEADER")
      (footprint "eagle-import:1X06")
      (libsource (lib "eagle-import") (part "MOTOR_HEADER"))
    )
    (comp (ref "P3")
      (value "JTAG")
      (footprint "eagle-import:IDC20")
      (libsource (lib "eagle-import") (part "JTAG"))
    )
    (comp (ref "Q1")
      (value "SI9933CDY-PFET")
      (footprint "eagle-import:SO08")
      (libsource (lib "eagle-import") (part "SI9933CDY-PFET"))
    )
    (comp (ref "Q2")
      (value "CSD17308Q3")
      (footprint "eagle-import:SON-8")
      (libsource (lib "eagle-import") (part "CSD17308Q3"))
    )
    (comp (ref "Q3")
      (value "CSD17308Q3")
      (footprint "eagle-import:SON-8")
      (libsource (lib "eagle-import") (part "CSD17308Q3"))
    )
    (comp (ref "Q4")
      (value "CSD17308Q3")
      (footprint "eagle-import:SON-8")
      (libsource (lib "eagle-import") (part "CSD17308Q3"))
    )
    (comp (ref "Q5")
      (value "CSD17308Q3")
      (footprint "eagle-import:SON-8")
      (libsource (lib "eagle-import") (part "CSD17308Q3"))
    )
    (comp (ref "Q6")
      (value "CSD17308Q3")
      (footprint "eagle-import:SON-8")
      (libsource (lib "eagle-import") (part "CSD17308Q3"))
    )
    (comp (ref "Q7")
      (value "CSD17308Q3")
      (footprint "eagle-import:SON-8")
      (libsource (lib "eagle-import") (part "CSD17308Q3"))
    )
    (comp (ref "Q8")
      (value "CSD17308Q3")
      (footprint "eagle-import:SON-8")
      (libsource (lib "eagle-import") (part "CSD17308Q3"))
    )
    (comp (ref "R1")
      (value "4.7K")
      (footprint "eagle-import:0805")
      (libsource (lib "eagle-import") (part "RESISTOR0805-RES"))
    )
    (comp (ref "R2")
      (value "4.7K")
      (footprint "eagle-import:0805")
      (libsource (lib "eagle-import") (part "RESISTOR0805-RES"))
    )
    (comp (ref "R3")
      (value "4.7K")
      (footprint "eagle-import:0805")
      (libsource (lib "eagle-import") (part "RESISTOR0805-RES"))
    )
    (comp (ref "R4")
      (value "4.7K")
      (footprint "eagle-import:0805")
      (libsource (lib "eagle-import") (part "RESISTOR0805-RES"))
    )
    (comp (ref "R5")
      (value "4.7K")
      (footprint "eagle-import:0805")
      (libsource (lib "eagle-import") (part "RESISTOR0805-RES"))
    )
    (comp (ref "R6")
      (value "4.7K")
      (footprint "eagle-import:0805")
      (libsource (lib "eagle-import") (part "RESISTOR0805-RES"))
    )
    (comp (ref "R7")
      (value ".756K")
      (footprint "eagle-import:0805")
      (libsource (lib "eagle-import") (part "RESISTOR0805-RES"))
    )
    (comp (ref "R8")
      (value ".768K")
      (footprint "eagle-import:0805")
      (libsource (lib "eagle-import") (part "RESISTOR0805-RES"))
    )
    (comp (ref "R9")
      (value ".244K")
      (footprint "eagle-import:0805")
      (libsource (lib "eagle-import") (part "RESISTOR0805-RES"))
    )
    (comp (ref "R10")
      (value ".232K")
      (footprint "eagle-import:0805")
      (libsource (lib "eagle-import") (part "RESISTOR0805-RES"))
    )
    (comp (ref "R11")
      (value "10K")
      (footprint "eagle-import:0805")
      (libsource (lib "eagle-import") (part "RESISTOR0805-RES"))
    )
    (comp (ref "R12")
      (value "0")
      (footprint "eagle-import:0805")
      (libsource (lib "eagle-import") (part "RESISTOR0805-RES"))
    )
    (comp (ref "R13")
      (value "0")
      (footprint "eagle-import:0805")
      (libsource (lib "eagle-import") (part "RESISTOR0805-RES"))
    )
    (comp (ref "R14")
      (value "0")
      (footprint "eagle-import:0805")
      (libsource (lib "eagle-import") (part "RESISTOR0805-RES"))
    )
    (comp (ref "R15")
      (value "220")
      (footprint "eagle-import:0805")
      (libsource (lib "eagle-import") (part "RESISTOR0805-RES"))
    )
    (comp (ref "R16")
      (value "100")
      (footprint "eagle-import:0805")
      (libsource (lib "eagle-import") (part "SparkFun-Resistors_RESISTOR0805-RES"))
    )
    (comp (ref "R17")
      (value "10K")
      (footprint "eagle-import:0805")
      (libsource (lib "eagle-import") (part "RESISTOR0805-RES"))
    )
    (comp (ref "R18")
      (value "10K")
      (footprint "eagle-import:0805")
      (libsource (lib "eagle-import") (part "RESISTOR0805-RES"))
    )
    (comp (ref "R19")
      (value "10K")
      (footprint "eagle-import:0805")
      (libsource (lib "eagle-import") (part "RESISTOR0805-RES"))
    )
    (comp (ref "R20")
      (value "10K")
      (footprint "eagle-import:0805")
      (libsource (lib "eagle-import") (part "RESISTOR0805-RES"))
    )
    (comp (ref "R21")
      (value "10K")
      (footprint "eagle-import:0805")
      (libsource (lib "eagle-import") (part "RESISTOR0805-RES"))
    )
    (comp (ref "R22")
      (value "1K")
      (footprint "eagle-import:0805")
      (libsource (lib "eagle-import") (part "RESISTOR0805-RES"))
    )
    (comp (ref "R23")
      (value "1K")
      (footprint "eagle-import:0805")
      (libsource (lib "eagle-import") (part "RESISTOR0805-RES"))
    )
    (comp (ref "R24")
      (value "10K")
      (footprint "eagle-import:0805")
      (libsource (lib "eagle-import") (part "RESISTOR0805-RES"))
    )
    (comp (ref "R25")
      (value "1K")
      (footprint "eagle-import:0805")
      (libsource (lib "eagle-import") (part "RESISTOR0805-RES"))
    )
    (comp (ref "R26")
      (value "66")
      (footprint "eagle-import:0805")
      (libsource (lib "eagle-import") (part "RESISTOR0805-RES"))
    )
    (comp (ref "R27")
      (value "196")
      (footprint "eagle-import:0805")
      (libsource (lib "eagle-import") (part "RESISTOR0805-RES"))
    )
    (comp (ref "R28")
      (value "20k")
      (footprint "eagle-import:0805")
      (libsource (lib "eagle-import") (part "RESISTOR0805-RES"))
    )
    (comp (ref "R29")
      (value "4.7k")
      (footprint "eagle-import:0805")
      (libsource (lib "eagle-import") (part "RESISTOR0805-RES"))
    )
    (comp (ref "R30")
      (value "100k")
      (footprint "eagle-import:0805")
      (libsource (lib "eagle-import") (part "RESISTOR0805-RES"))
    )
    (comp (ref "R31")
      (value "100k")
      (footprint "eagle-import:0805")
      (libsource (lib "eagle-import") (part "RESISTOR0805-RES"))
    )
    (comp (ref "R32")
      (value "1500")
      (footprint "eagle-import:0805")
      (libsource (lib "eagle-import") (part "RESISTOR0805-RES"))
    )
    (comp (ref "R33")
      (value "57.6k")
      (footprint "eagle-import:0805")
      (libsource (lib "eagle-import") (part "RESISTOR0805-RES"))
    )
    (comp (ref "R34")
      (value "365k")
      (footprint "eagle-import:0805")
      (libsource (lib "eagle-import") (part "RESISTOR0805-RES"))
    )
    (comp (ref "R35")
      (value "1.3M")
      (footprint "eagle-import:0805")
      (libsource (lib "eagle-import") (part "RESISTOR0805-RES"))
    )
    (comp (ref "R36")
      (value "113k")
      (footprint "eagle-import:0805")
      (libsource (lib "eagle-import") (part "RESISTOR0805-RES"))
    )
    (comp (ref "R37")
      (value "1k")
      (footprint "eagle-import:0805")
      (libsource (lib "eagle-import") (part "SparkFun-Resistors_RESISTOR0805-RES"))
    )
    (comp (ref "R38")
      (value "1k")
      (footprint "eagle-import:0805")
      (libsource (lib "eagle-import") (part "SparkFun-Resistors_RESISTOR0805-RES"))
    )
    (comp (ref "R39")
      (value "100")
      (footprint "eagle-import:0805")
      (libsource (lib "eagle-import") (part "SparkFun-Resistors_RESISTOR0805-RES"))
    )
    (comp (ref "R40")
      (value "5.1k")
      (footprint "eagle-import:0805")
      (libsource (lib "eagle-import") (part "SparkFun-Resistors_RESISTOR0805-RES"))
    )
    (comp (ref "R41")
      (value "1k")
      (footprint "eagle-import:0805")
      (libsource (lib "eagle-import") (part "SparkFun-Resistors_RESISTOR0805-RES"))
    )
    (comp (ref "R42")
      (value "5m")
      (footprint "eagle-import:0805")
      (libsource (lib "eagle-import") (part "SparkFun-Resistors_RESISTOR0805-RES"))
    )
    (comp (ref "R43")
      (value "10")
      (footprint "eagle-import:0805")
      (libsource (lib "eagle-import") (part "SparkFun-Resistors_RESISTOR0805-RES"))
    )
    (comp (ref "R44")
      (value "150k")
      (footprint "eagle-import:0805")
      (libsource (lib "eagle-import") (part "RESISTOR0805-RES"))
    )
    (comp (ref "R45")
      (value "100")
      (footprint "eagle-import:0805")
      (libsource (lib "eagle-import") (part "SparkFun-Resistors_RESISTOR0805-RES"))
    )
    (comp (ref "R46")
      (value "100")
      (footprint "eagle-import:0805")
      (libsource (lib "eagle-import") (part "SparkFun-Resistors_RESISTOR0805-RES"))
    )
    (comp (ref "R47")
      (value "100")
      (footprint "eagle-import:0805")
      (libsource (lib "eagle-import") (part "SparkFun-Resistors_RESISTOR0805-RES"))
    )
    (comp (ref "R48")
      (value "100")
      (footprint "eagle-import:0805")
      (libsource (lib "eagle-import") (part "SparkFun-Resistors_RESISTOR0805-RES"))
    )
    (comp (ref "R49")
      (value "100")
      (footprint "eagle-import:0805")
      (libsource (lib "eagle-import") (part "SparkFun-Resistors_RESISTOR0805-RES"))
    )
    (comp (ref "R50")
      (value "150k")
      (footprint "eagle-import:0805")
      (libsource (lib "eagle-import") (part "RESISTOR0805-RES"))
    )
    (comp (ref "R51")
      (value "5.1k")
      (footprint "eagle-import:0805")
      (libsource (lib "eagle-import") (part "SparkFun-Resistors_RESISTOR0805-RES"))
    )
    (comp (ref "R52")
      (value "10M")
      (footprint "eagle-import:0805")
      (libsource (lib "eagle-import") (part "SparkFun-Resistors_RESISTOR0805-RES"))
    )
    (comp (ref "R53")
      (value "5.1k")
      (footprint "eagle-import:0805")
      (libsource (lib "eagle-import") (part "SparkFun-Resistors_RESISTOR0805-RES"))
    )
    (comp (ref "R54")
      (value "5.1k")
      (footprint "eagle-import:0805")
      (libsource (lib "eagle-import") (part "SparkFun-Resistors_RESISTOR0805-RES"))
    )
    (comp (ref "R55")
      (value "10M")
      (footprint "eagle-import:0805")
      (libsource (lib "eagle-import") (part "SparkFun-Resistors_RESISTOR0805-RES"))
    )
    (comp (ref "R56")
      (value "5.1k")
      (footprint "eagle-import:0805")
      (libsource (lib "eagle-import") (part "SparkFun-Resistors_RESISTOR0805-RES"))
    )
    (comp (ref "R57")
      (value "100")
      (footprint "eagle-import:0805")
      (libsource (lib "eagle-import") (part "SparkFun-Resistors_RESISTOR0805-RES"))
    )
    (comp (ref "R58")
      (value "100")
      (footprint "eagle-import:0805")
      (libsource (lib "eagle-import") (part "SparkFun-Resistors_RESISTOR0805-RES"))
    )
    (comp (ref "R59")
      (value "10M")
      (footprint "eagle-import:0805")
      (libsource (lib "eagle-import") (part "SparkFun-Resistors_RESISTOR0805-RES"))
    )
    (comp (ref "R60")
      (value "100")
      (footprint "eagle-import:0805")
      (libsource (lib "eagle-import") (part "SparkFun-Resistors_RESISTOR0805-RES"))
    )
    (comp (ref "R61")
      (value "10k")
      (footprint "eagle-import:0805")
      (libsource (lib "eagle-import") (part "SparkFun-Resistors_RESISTOR0805-RES"))
    )
    (comp (ref "R62")
      (value "5.1k")
      (footprint "eagle-import:0805")
      (libsource (lib "eagle-import") (part "SparkFun-Resistors_RESISTOR0805-RES"))
    )
    (comp (ref "R63")
      (value "100")
      (footprint "eagle-import:0805")
      (libsource (lib "eagle-import") (part "SparkFun-Resistors_RESISTOR0805-RES"))
    )
    (comp (ref "R64")
      (value "100")
      (footprint "eagle-import:0805")
      (libsource (lib "eagle-import") (part "SparkFun-Resistors_RESISTOR0805-RES"))
    )
    (comp (ref "R65")
      (value "1k")
      (footprint "eagle-import:0805")
      (libsource (lib "eagle-import") (part "SparkFun-Resistors_RESISTOR0805-RES"))
    )
    (comp (ref "R66")
      (value "100")
      (footprint "eagle-import:0805")
      (libsource (lib "eagle-import") (part "SparkFun-Resistors_RESISTOR0805-RES"))
    )
    (comp (ref "R67")
      (value "1")
      (footprint "eagle-import:0805")
      (libsource (lib "eagle-import") (part "SparkFun-Resistors_RESISTOR0805-RES"))
    )
    (comp (ref "R68")
      (value "100k")
      (footprint "eagle-import:0805")
      (libsource (lib "eagle-import") (part "SparkFun-Resistors_RESISTOR0805-RES"))
    )
    (comp (ref "R69")
      (value "2")
      (footprint "eagle-import:0805")
      (libsource (lib "eagle-import") (part "SparkFun-Resistors_RESISTOR0805-RES"))
    )
    (comp (ref "R70")
      (value "10m")
      (footprint "eagle-import:0805")
      (libsource (lib "eagle-import") (part "SparkFun-Resistors_RESISTOR0805-RES"))
    )
    (comp (ref "R71")
      (value "10k")
      (footprint "eagle-import:0805")
      (libsource (lib "eagle-import") (part "SparkFun-Resistors_RESISTOR0805-RES"))
    )
    (comp (ref "R72")
      (value "332k")
      (footprint "eagle-import:0805")
      (libsource (lib "eagle-import") (part "SparkFun-Resistors_RESISTOR0805-RES"))
    )
    (comp (ref "R73")
      (value "35.63k")
      (footprint "eagle-import:0805")
      (libsource (lib "eagle-import") (part "SparkFun-Resistors_RESISTOR0805-RES"))
    )
    (comp (ref "R74")
      (value "1K")
      (footprint "eagle-import:0805")
      (libsource (lib "eagle-import") (part "RESISTOR0805-RES"))
    )
    (comp (ref "R75")
      (value "0")
      (footprint "eagle-import:0805")
      (libsource (lib "eagle-import") (part "SparkFun-Resistors_RESISTOR0805-RES"))
    )
    (comp (ref "R76")
      (value "9.7K")
      (footprint "eagle-import:0805")
      (libsource (lib "eagle-import") (part "RESISTOR0805-RES"))
    )
    (comp (ref "R77")
      (value "100")
      (footprint "eagle-import:0805")
      (libsource (lib "eagle-import") (part "SparkFun-Resistors_RESISTOR0805-RES"))
    )
    (comp (ref "R78")
      (value "3.3K")
      (footprint "eagle-import:0805")
      (libsource (lib "eagle-import") (part "RESISTOR0805-RES"))
    )
    (comp (ref "R79")
      (value "100")
      (footprint "eagle-import:0805")
      (libsource (lib "eagle-import") (part "RESISTOR0805-RES"))
    )
    (comp (ref "R80")
      (value "100")
      (footprint "eagle-import:0805")
      (libsource (lib "eagle-import") (part "RESISTOR0805-RES"))
    )
    (comp (ref "R81")
      (value "100")
      (footprint "eagle-import:0805")
      (libsource (lib "eagle-import") (part "RESISTOR0805-RES"))
    )
    (comp (ref "R82")
      (value "100")
      (footprint "eagle-import:0805")
      (libsource (lib "eagle-import") (part "SparkFun-Resistors_RESISTOR0805-RES"))
    )
    (comp (ref "RT1")
      (value "10K-NTC")
      (footprint "eagle-import:0805")
      (libsource (lib "eagle-import") (part "THM"))
    )
    (comp (ref "RT2")
      (value "10k-NTC")
      (footprint "eagle-import:0805")
      (libsource (lib "eagle-import") (part "THM"))
    )
    (comp (ref "RT3")
      (value "10k")
      (footprint "eagle-import:0805")
      (libsource (lib "eagle-import") (part "THM"))
    )
    (comp (ref "RT4")
      (value "10k")
      (footprint "eagle-import:0805")
      (libsource (lib "eagle-import") (part "THM"))
    )
    (comp (ref "RT5")
      (value "10k")
      (footprint "eagle-import:0805")
      (libsource (lib "eagle-import") (part "THM"))
    )
    (comp (ref "S1")
      (value "RESET_BUTTON")
      (footprint "eagle-import:5.2X5.2")
      (libsource (lib "eagle-import") (part "RESET_BUTTON"))
    )
    (comp (ref "S2")
      (value "SWITCH")
      (footprint "eagle-import:SWITCH")
      (libsource (lib "eagle-import") (part "SWITCH"))
    )
    (comp (ref "U$1")
      (value "XT60")
      (footprint "eagle-import:XT60")
      (libsource (lib "eagle-import") (part "XT60"))
    )
    (comp (ref "U1")
      (value "LMS8117")
      (footprint "eagle-import:SOT-223")
      (libsource (lib "eagle-import") (part "LMS8117"))
    )
    (comp (ref "U2")
      (value "5V_BUCK_REG")
      (footprint "eagle-import:T0-263-6")
      (libsource (lib "eagle-import") (part "5V_BUCK_REG"))
    )
    (comp (ref "U3")
      (value "BTM7752G")
      (footprint "eagle-import:36-BSSOP")
      (libsource (lib "eagle-import") (part "BTM7752G"))
    )
    (comp (ref "U4")
      (value "BTM7752G")
      (footprint "eagle-import:36-BSSOP")
      (libsource (lib "eagle-import") (part "BTM7752G"))
    )
    (comp (ref "U5")
      (value "SN74LV4T125")
      (footprint "eagle-import:14-TSSOP")
      (libsource (lib "eagle-import") (part "SN74LV4T125"))
    )
    (comp (ref "U6")
      (value "SN74LV4T125")
      (footprint "eagle-import:14-TSSOP")
      (libsource (lib "eagle-import") (part "SN74LV4T125"))
    )
    (comp (ref "U7")
      (value "STM32F405RGT6")
      (footprint "eagle-import:LQFP64")
      (libsource (lib "eagle-import") (part "STM32F405RGT6"))
    )
    (comp (ref "U8")
      (value "RN4020RN4020")
      (footprint "eagle-import:RN4020")
      (libsource (lib "eagle-import") (part "RN4020RN4020"))
    )
    (comp (ref "U9")
      (value "BQ51013B-20VQFN")
      (footprint "eagle-import:20-VQFN")
      (libsource (lib "eagle-import") (part "BQ51013B-20VQFN"))
    )
    (comp (ref "U10")
      (value "IMU")
      (footprint "eagle-import:IMU_BREAKOUT")
      (libsource (lib "eagle-import") (part "IMU"))
    )
    (comp (ref "U11")
      (value "LTC3122-MSOP")
      (footprint "eagle-import:MSOP-12_GND")
      (libsource (lib "eagle-import") (part "LTC3122-MSOP"))
    )
    (comp (ref "U12")
      (value "CBAT54S-SOT23-3")
      (footprint "eagle-import:SOT23-3")
      (libsource (lib "eagle-import") (part "CBAT54S-SOT23-3"))
    )
    (comp (ref "U13")
      (value "BQ2947")
      (footprint "eagle-import:WSON-8")
      (libsource (lib "eagle-import") (part "BQ2947"))
    )
    (comp (ref "U14")
      (value "TPA2005D1DGN")
      (footprint "eagle-import:POWER-SOP8")
      (libsource (lib "eagle-import") (part "TPA2005D1DGN"))
    )
    (comp (ref "U15")
      (value "BQ40Z60")
      (footprint "eagle-import:S-PVQFN-N32")
      (libsource (lib "eagle-import") (part "BQ40Z60"))
    )
    (comp (ref "Y1")
      (value "32.768KHz")
      (footprint "eagle-import:4-SMD,J-LEAD")
      (libsource (lib "eagle-import") (part "MC-30632.768K-E3"))
    )
    (comp (ref "Y2")
      (value "25MHz")
      (footprint "eagle-import:4-SMD,J-LEAD-2")
      (libsource (lib "eagle-import") (part "MA-5066-25.0000M-C0"))
    )
    (comp (ref "Z2")
      (value "DDZ16ASF-7")
      (footprint "eagle-import:SOD-323F")
      (libsource (lib "eagle-import") (part "DDZ16ASF-7"))
    )
    (comp (ref "Z3")
      (value "MM3Z75VC")
      (footprint "eagle-import:SOD-323F")
      (libsource (lib "eagle-import") (part "MM3Z75VC"))
    )
    (comp (ref "Z4")
      (value "MM3Z75VC")
      (footprint "eagle-import:SOD-323F")
      (libsource (lib "eagle-import") (part "MM3Z75VC"))
    )
    (comp (ref "Z5")
      (value "MM3Z75VC")
      (footprint "eagle-import:SOD-323F")
      (libsource (lib "eagle-import") (part "MM3Z75VC"))
    )
  )
  (nets
    (net (code "1") (name "/12V_BAT") (class "Default")
      (node (ref "F1") (pin "1") (pinfunction "1_1") (pintype "bidirectional"))
      (node (ref "F3") (pin "1") (pinfunction "1_1") (pintype "bidirectional"))
      (node (ref "J4") (pin "1") (pinfunction "1_1") (pintype "passive"))
      (node (ref "R37") (pin "1") (pinfunction "1_1") (pintype "passive"))
      (node (ref "R39") (pin "2") (pinfunction "2_2") (pintype "passive"))
      (node (ref "R43") (pin "1") (pinfunction "1_1") (pintype "passive"))
      (node (ref "R45") (pin "1") (pinfunction "1_1") (pintype "passive"))
      (node (ref "S2") (pin "P$4") (pinfunction "O_P$4") (pintype "passive"))
    )
    (net (code "2") (name "/12V_CC") (class "Default")
      (node (ref "C62") (pin "2") (pinfunction "2_2") (pintype "passive"))
      (node (ref "C67") (pin "1") (pinfunction "1_1") (pintype "passive"))
      (node (ref "C69") (pin "1") (pinfunction "1_1") (pintype "passive"))
      (node (ref "C71") (pin "2") (pinfunction "2_2") (pintype "passive"))
      (node (ref "C72") (pin "2") (pinfunction "2_2") (pintype "passive"))
      (node (ref "JP2") (pin "3") (pinfunction "S_3") (pintype "passive"))
      (node (ref "Q4") (pin "P$1") (pinfunction "S1_P$1") (pintype "bidirectional"))
      (node (ref "Q4") (pin "P$2") (pinfunction "S1_P$2") (pintype "bidirectional"))
      (node (ref "Q4") (pin "P$3") (pinfunction "S1_P$3") (pintype "bidirectional"))
      (node (ref "R55") (pin "1") (pinfunction "1_1") (pintype "passive"))
      (node (ref "R70") (pin "1") (pinfunction "1_1") (pintype "passive"))
      (node (ref "R72") (pin "2") (pinfunction "2_2") (pintype "passive"))
      (node (ref "U15") (pin "P$19") (pinfunction "HSRN_P$19") (pintype "bidirectional"))
    )
    (net (code "3") (name "/AUDIO+") (class "Default")
      (node (ref "J5") (pin "2") (pinfunction "2_2") (pintype "passive"))
      (node (ref "U14") (pin "5") (pinfunction "OUT+_5") (pintype "bidirectional"))
    )
    (net (code "4") (name "/AUDIO-") (class "Default")
      (node (ref "J5") (pin "1") (pinfunction "1_1") (pintype "passive"))
      (node (ref "U14") (pin "8") (pinfunction "OUT-_8") (pintype "bidirectional"))
    )
    (net (code "5") (name "/AUDIO_PWM") (class "Default")
      (node (ref "R81") (pin "1") (pinfunction "1_1") (pintype "passive"))
      (node (ref "U7") (pin "P$21") (pinfunction "PA5_P$21") (pintype "bidirectional"))
    )
    (net (code "6") (name "/BATT") (class "Default")
      (node (ref "R76") (pin "2") (pinfunction "2_2") (pintype "passive"))
      (node (ref "R78") (pin "1") (pinfunction "1_1") (pintype "passive"))
      (node (ref "U7") (pin "P$24") (pinfunction "PC4_P$24") (pintype "bidirectional"))
    )
    (net (code "7") (name "/BLUE_WAKE_SW") (class "Default")
      (node (ref "U7") (pin "P$20") (pinfunction "PA4_P$20") (pintype "bidirectional"))
      (node (ref "U8") (pin "P$7") (pinfunction "WAKE_SW_P$7") (pintype "input"))
    )
    (net (code "8") (name "/BLU_CMD") (class "Default")
      (node (ref "U7") (pin "P$27") (pinfunction "PB1_P$27") (pintype "bidirectional"))
      (node (ref "U8") (pin "P$8") (pinfunction "CMD/MLDP_P$8") (pintype "input"))
    )
    (net (code "9") (name "/BLU_CTS") (class "Default")
      (node (ref "U7") (pin "P$15") (pinfunction "PA1_P$15") (pintype "bidirectional"))
      (node (ref "U8") (pin "P$14") (pinfunction "PIO5_P$14") (pintype "bidirectional"))
    )
    (net (code "10") (name "/BLU_RTS") (class "Default")
      (node (ref "U7") (pin "P$14") (pinfunction "PA0_WKUP_P$14") (pintype "bidirectional"))
      (node (ref "U8") (pin "P$18") (pinfunction "RTS/PIO6_P$18") (pintype "bidirectional"))
    )
    (net (code "11") (name "/BLU_RX") (class "Default")
      (node (ref "J7") (pin "3") (pinfunction "3_3") (pintype "passive"))
      (node (ref "U7") (pin "P$16") (pinfunction "PA2_P$16") (pintype "bidirectional"))
      (node (ref "U8") (pin "P$6") (pinfunction "UART_RX_P$6") (pintype "input"))
    )
    (net (code "12") (name "/BLU_TX") (class "Default")
      (node (ref "J7") (pin "4") (pinfunction "4_4") (pintype "passive"))
      (node (ref "U7") (pin "P$17") (pinfunction "PA3_P$17") (pintype "bidirectional"))
      (node (ref "U8") (pin "P$5") (pinfunction "UART_TX_P$5") (pintype "output"))
    )
    (net (code "13") (name "/BLU_WAKE_HW") (class "Default")
      (node (ref "J7") (pin "2") (pinfunction "2_2") (pintype "passive"))
      (node (ref "U7") (pin "P$22") (pinfunction "PA6_P$22") (pintype "bidirectional"))
      (node (ref "U8") (pin "P$15") (pinfunction "WAKE_HW_P$15") (pintype "bidirectional"))
    )
    (net (code "14") (name "/CHRG_GPIO_SYSPRES") (class "Default")
      (node (ref "R65") (pin "2") (pinfunction "2_2") (pintype "passive"))
      (node (ref "U7") (pin "P$42") (pinfunction "PA9_P$42") (pintype "bidirectional"))
    )
    (net (code "15") (name "/CHRG_I2C_SCL") (class "Default")
      (node (ref "R63") (pin "2") (pinfunction "2_2") (pintype "passive"))
      (node (ref "U7") (pin "P$29") (pinfunction "PB10_P$29") (pintype "bidirectional"))
    )
    (net (code "16") (name "/CHRG_I2C_SDA") (class "Default")
      (node (ref "R64") (pin "2") (pinfunction "2_2") (pintype "passive"))
      (node (ref "U7") (pin "P$30") (pinfunction "PB11_P$30") (pintype "bidirectional"))
    )
    (net (code "17") (name "/CHRG_I2C_SMBA") (class "Default")
      (node (ref "R66") (pin "2") (pinfunction "2_2") (pintype "passive"))
      (node (ref "U7") (pin "P$33") (pinfunction "PB12_P$33") (pintype "bidirectional"))
    )
    (net (code "18") (name "/IMU_I2C_SCL") (class "Default")
      (node (ref "U10") (pin "SCL") (pinfunction "SCL_SCL") (pintype "bidirectional"))
      (node (ref "U7") (pin "P$61") (pinfunction "PB8_P$61") (pintype "bidirectional"))
    )
    (net (code "19") (name "/IMU_I2C_SDA") (class "Default")
      (node (ref "U10") (pin "SDA") (pinfunction "SDA_SDA") (pintype "bidirectional"))
      (node (ref "U7") (pin "P$59") (pinfunction "PB7_P$59") (pintype "bidirectional"))
    )
    (net (code "20") (name "/IMU_SDO_AG") (class "Default")
      (node (ref "U10") (pin "SDO_AG") (pinfunction "SDO_AG_SDO_AG") (pintype "bidirectional"))
      (node (ref "U7") (pin "P$10") (pinfunction "PC2_P$10") (pintype "bidirectional"))
    )
    (net (code "21") (name "/IMU_SDO_M") (class "Default")
      (node (ref "U10") (pin "SDO_M") (pinfunction "SDO_M_SDO_M") (pintype "bidirectional"))
      (node (ref "U7") (pin "P$11") (pinfunction "PC3_P$11") (pintype "bidirectional"))
    )
    (net (code "22") (name "/JNTRST") (class "Default")
      (node (ref "P3") (pin "P$3") (pinfunction "JNTRST_P$3") (pintype "bidirectional"))
      (node (ref "U7") (pin "P$56") (pinfunction "PB4_P$56") (pintype "bidirectional"))
    )
    (net (code "23") (name "/JTCK") (class "Default")
      (node (ref "P3") (pin "P$9") (pinfunction "JTCK_P$9") (pintype "bidirectional"))
      (node (ref "U7") (pin "P$49") (pinfunction "PA14_P$49") (pintype "bidirectional"))
    )
    (net (code "24") (name "/JTDI") (class "Default")
      (node (ref "P3") (pin "P$5") (pinfunction "JTDI_P$5") (pintype "bidirectional"))
      (node (ref "U7") (pin "P$50") (pinfunction "PA15_P$50") (pintype "bidirectional"))
    )
    (net (code "25") (name "/JTDO") (class "Default")
      (node (ref "P3") (pin "P$13") (pinfunction "JTDO_P$13") (pintype "bidirectional"))
      (node (ref "U7") (pin "P$55") (pinfunction "PB3_P$55") (pintype "bidirectional"))
    )
    (net (code "26") (name "/JTMS") (class "Default")
      (node (ref "P3") (pin "P$7") (pinfunction "JTMS_P$7") (pintype "bidirectional"))
      (node (ref "U7") (pin "P$46") (pinfunction "PA13_P$46") (pintype "bidirectional"))
    )
    (net (code "27") (name "/M1_A_3.3") (class "Default")
      (node (ref "U5") (pin "P$3") (pinfunction "1Y_P$3") (pintype "bidirectional"))
      (node (ref "U7") (pin "P$23") (pinfunction "PA7_P$23") (pintype "bidirectional"))
    )
    (net (code "28") (name "/M1_A_5") (class "Default")
      (node (ref "P1") (pin "A") (pinfunction "A_A") (pintype "passive"))
      (node (ref "U5") (pin "P$2") (pinfunction "1A_P$2") (pintype "bidirectional"))
    )
    (net (code "29") (name "/M1_B_3.3") (class "Default")
      (node (ref "U5") (pin "P$6") (pinfunction "2Y_P$6") (pintype "bidirectional"))
      (node (ref "U7") (pin "P$34") (pinfunction "PB13_P$34") (pintype "bidirectional"))
    )
    (net (code "30") (name "/M1_B_5") (class "Default")
      (node (ref "P1") (pin "B") (pinfunction "B_B") (pintype "passive"))
      (node (ref "U5") (pin "P$5") (pinfunction "2A_P$5") (pintype "bidirectional"))
    )
    (net (code "31") (name "/M2_A_3.3") (class "Default")
      (node (ref "U5") (pin "P$11") (pinfunction "4Y_P$11") (pintype "bidirectional"))
      (node (ref "U7") (pin "P$25") (pinfunction "PC5_P$25") (pintype "bidirectional"))
    )
    (net (code "32") (name "/M2_A_5") (class "Default")
      (node (ref "P2") (pin "A") (pinfunction "A_A") (pintype "passive"))
      (node (ref "U5") (pin "P$12") (pinfunction "4A_P$12") (pintype "bidirectional"))
    )
    (net (code "33") (name "/M2_B_3.3") (class "Default")
      (node (ref "U5") (pin "P$8") (pinfunction "3Y_P$8") (pintype "bidirectional"))
      (node (ref "U7") (pin "P$26") (pinfunction "PB0_P$26") (pintype "bidirectional"))
    )
    (net (code "34") (name "/M2_B_5") (class "Default")
      (node (ref "P2") (pin "B") (pinfunction "B_B") (pintype "passive"))
      (node (ref "U5") (pin "P$9") (pinfunction "3A_P$9") (pintype "bidirectional"))
    )
    (net (code "35") (name "/MC1_IN1") (class "Default")
      (node (ref "R1") (pin "1") (pinfunction "1_1") (pintype "passive"))
      (node (ref "U7") (pin "P$38") (pinfunction "PC7_P$38") (pintype "bidirectional"))
    )
    (net (code "36") (name "/MC1_IN2") (class "Default")
      (node (ref "R3") (pin "1") (pinfunction "1_1") (pintype "passive"))
      (node (ref "U7") (pin "P$37") (pinfunction "PC6_P$37") (pintype "bidirectional"))
    )
    (net (code "37") (name "/MC1_INH_3.3") (class "Default")
      (node (ref "U6") (pin "P$2") (pinfunction "1A_P$2") (pintype "bidirectional"))
      (node (ref "U7") (pin "P$40") (pinfunction "PC9_P$40") (pintype "bidirectional"))
    )
    (net (code "38") (name "/MC1_INH_5") (class "Default")
      (node (ref "R5") (pin "2") (pinfunction "2_2") (pintype "passive"))
      (node (ref "U6") (pin "P$3") (pinfunction "1Y_P$3") (pintype "bidirectional"))
    )
    (net (code "39") (name "/MC1_IS") (class "Default")
      (node (ref "R7") (pin "2") (pinfunction "2_2") (pintype "passive"))
      (node (ref "R9") (pin "1") (pinfunction "1_1") (pintype "passive"))
      (node (ref "U7") (pin "P$8") (pinfunction "PC0_P$8") (pintype "bidirectional"))
    )
    (net (code "40") (name "/MC2_IN1") (class "Default")
      (node (ref "R2") (pin "2") (pinfunction "2_2") (pintype "passive"))
      (node (ref "U7") (pin "P$58") (pinfunction "PB6_P$58") (pintype "bidirectional"))
    )
    (net (code "41") (name "/MC2_IN2") (class "Default")
      (node (ref "R4") (pin "1") (pinfunction "1_1") (pintype "passive"))
      (node (ref "U7") (pin "P$62") (pinfunction "PB9_P$62") (pintype "bidirectional"))
    )
    (net (code "42") (name "/MC2_INH_3.3") (class "Default")
      (node (ref "U6") (pin "P$5") (pinfunction "2A_P$5") (pintype "bidirectional"))
      (node (ref "U7") (pin "P$45") (pinfunction "PA12_P$45") (pintype "bidirectional"))
    )
    (net (code "43") (name "/MC2_INH_5") (class "Default")
      (node (ref "R6") (pin "2") (pinfunction "2_2") (pintype "passive"))
      (node (ref "U6") (pin "P$6") (pinfunction "2Y_P$6") (pintype "bidirectional"))
    )
    (net (code "44") (name "/MC2_IS") (class "Default")
      (node (ref "R10") (pin "1") (pinfunction "1_1") (pintype "passive"))
      (node (ref "R8") (pin "2") (pinfunction "2_2") (pintype "passive"))
      (node (ref "U7") (pin "P$9") (pinfunction "PC1_P$9") (pintype "bidirectional"))
    )
    (net (code "45") (name "/PACK+") (class "Default")
      (node (ref "C41") (pin "1") (pinfunction "1_1") (pintype "passive"))
      (node (ref "C45") (pin "1") (pinfunction "1_1") (pintype "passive"))
      (node (ref "C73") (pin "2") (pinfunction "2_2") (pintype "passive"))
      (node (ref "D5") (pin "A") (pinfunction "A_A") (pintype "passive"))
      (node (ref "Q6") (pin "P$1") (pinfunction "S1_P$1") (pintype "bidirectional"))
      (node (ref "Q6") (pin "P$2") (pinfunction "S1_P$2") (pintype "bidirectional"))
      (node (ref "Q6") (pin "P$3") (pinfunction "S1_P$3") (pintype "bidirectional"))
      (node (ref "Q8") (pin "P$1") (pinfunction "S1_P$1") (pintype "bidirectional"))
      (node (ref "Q8") (pin "P$2") (pinfunction "S1_P$2") (pintype "bidirectional"))
      (node (ref "Q8") (pin "P$3") (pinfunction "S1_P$3") (pintype "bidirectional"))
      (node (ref "R35") (pin "2") (pinfunction "2_2") (pintype "passive"))
      (node (ref "R59") (pin "1") (pinfunction "1_1") (pintype "passive"))
      (node (ref "R61") (pin "1") (pinfunction "1_1") (pintype "passive"))
      (node (ref "R68") (pin "1") (pinfunction "1_1") (pintype "passive"))
      (node (ref "R69") (pin "1") (pinfunction "1_1") (pintype "passive"))
      (node (ref "U11") (pin "11") (pinfunction "V_OUT_11") (pintype "bidirectional"))
    )
    (net (code "46") (name "/PACK-") (class "Default")
      (node (ref "R42") (pin "2") (pinfunction "2_2") (pintype "passive"))
      (node (ref "R48") (pin "1") (pinfunction "1_1") (pintype "passive"))
    )
    (net (code "47") (name "/SDIO_CK") (class "Default")
      (node (ref "J6") (pin "P$5") (pinfunction "CLK_P$5") (pintype "bidirectional"))
      (node (ref "U7") (pin "P$53") (pinfunction "PC12_P$53") (pintype "bidirectional"))
    )
    (net (code "48") (name "/SDIO_CMD") (class "Default")
      (node (ref "J6") (pin "P$2") (pinfunction "CMD_P$2") (pintype "bidirectional"))
      (node (ref "U7") (pin "P$54") (pinfunction "PD2_P$54") (pintype "bidirectional"))
    )
    (net (code "49") (name "/SDIO_D0") (class "Default")
      (node (ref "J6") (pin "P$7") (pinfunction "DATA_P$7") (pintype "bidirectional"))
      (node (ref "U7") (pin "P$39") (pinfunction "PC8_P$39") (pintype "bidirectional"))
    )
    (net (code "50") (name "/SERVO_PWM_3.3") (class "Default")
      (node (ref "U6") (pin "P$9") (pinfunction "3A_P$9") (pintype "bidirectional"))
      (node (ref "U7") (pin "P$41") (pinfunction "PA8_P$41") (pintype "bidirectional"))
    )
    (net (code "51") (name "/SERVO_PWM_5") (class "Default")
      (node (ref "J1") (pin "1") (pinfunction "1_1") (pintype "passive"))
      (node (ref "U6") (pin "P$8") (pinfunction "3Y_P$8") (pintype "bidirectional"))
    )
    (net (code "52") (name "/SPEAKER_SHUTDOWN") (class "Default")
      (node (ref "U14") (pin "1") (pinfunction "SHUTDOWN_1") (pintype "input"))
      (node (ref "U7") (pin "P$28") (pinfunction "PB2_P$28") (pintype "bidirectional"))
    )
    (net (code "53") (name "/WIRELESS_OUT_5V") (class "Default")
      (node (ref "C36") (pin "1") (pinfunction "1_1") (pintype "passive"))
      (node (ref "C38") (pin "1") (pinfunction "1_1") (pintype "passive"))
      (node (ref "D2") (pin "A") (pinfunction "A_A") (pintype "passive"))
      (node (ref "L2") (pin "P$1") (pinfunction "1_P$1") (pintype "passive"))
      (node (ref "Q1") (pin "5") (pinfunction "D_5") (pintype "bidirectional"))
      (node (ref "Q1") (pin "6") (pinfunction "D_6") (pintype "bidirectional"))
      (node (ref "U11") (pin "3") (pinfunction "V_IN_3") (pintype "bidirectional"))
      (node (ref "U11") (pin "9") (pinfunction "~{SD}_9") (pintype "bidirectional"))
      (node (ref "U9") (pin "P$4") (pinfunction "OUT_P$4") (pintype "bidirectional"))
    )
    (net (code "54") (name "/~{NRST}") (class "Default")
      (node (ref "P3") (pin "P$15") (pinfunction "NRST_P$15") (pintype "bidirectional"))
      (node (ref "R82") (pin "1") (pinfunction "1_1") (pintype "passive"))
      (node (ref "S1") (pin "P$1") (pinfunction "O_P$1") (pintype "passive"))
      (node (ref "S1") (pin "P$2") (pinfunction "O_P$2") (pintype "passive"))
      (node (ref "U7") (pin "P$7") (pinfunction "~{RST}_P$7") (pintype "bidirectional"))
    )
    (net (code "55") (name "3.3V") (class "Default")
      (node (ref "C10") (pin "2") (pinfunction "2_2") (pintype "passive"))
      (node (ref "C16") (pin "2") (pinfunction "2_2") (pintype "passive"))
      (node (ref "C19") (pin "1") (pinfunction "1_1") (pintype "passive"))
      (node (ref "C20") (pin "1") (pinfunction "1_1") (pintype "passive"))
      (node (ref "C21") (pin "1") (pinfunction "1_1") (pintype "passive"))
      (node (ref "C22") (pin "1") (pinfunction "1_1") (pintype "passive"))
      (node (ref "C23") (pin "1") (pinfunction "1_1") (pintype "passive"))
      (node (ref "C24") (pin "1") (pinfunction "1_1") (pintype "passive"))
      (node (ref "C25") (pin "2") (pinfunction "2_2") (pintype "passive"))
      (node (ref "C3") (pin "P$1") (pinfunction "+_P$1") (pintype "passive"))
      (node (ref "C61") (pin "1") (pinfunction "1_1") (pintype "passive"))
      (node (ref "J6") (pin "P$4") (pinfunction "VCC_P$4") (pintype "bidirectional"))
      (node (ref "J7") (pin "5") (pinfunction "5_5") (pintype "passive"))
      (node (ref "JP1") (pin "3") (pinfunction "S_3") (pintype "passive"))
      (node (ref "P3") (pin "P$1") (pinfunction "VDD_P$1") (pintype "bidirectional"))
      (node (ref "P3") (pin "P$2") (pinfunction "VDD_P$2") (pintype "bidirectional"))
      (node (ref "R74") (pin "2") (pinfunction "2_2") (pintype "passive"))
      (node (ref "U1") (pin "P$2") (pinfunction "VOUT_P$2") (pintype "bidirectional"))
      (node (ref "U1") (pin "P$4") (pinfunction "VOUT_P$4") (pintype "bidirectional"))
      (node (ref "U10") (pin "3.3V") (pinfunction "VCC_3.3V") (pintype "bidirectional"))
      (node (ref "U10") (pin "CS_AG") (pinfunction "CS_AG_CS_AG") (pintype "bidirectional"))
      (node (ref "U10") (pin "CS_M") (pinfunction "CS_M_CS_M") (pintype "bidirectional"))
      (node (ref "U14") (pin "6") (pinfunction "VDD_6") (pintype "power_in"))
      (node (ref "U5") (pin "P$14") (pinfunction "VCC_P$14") (pintype "bidirectional"))
      (node (ref "U7") (pin "P$1") (pinfunction "VBAT_P$1") (pintype "bidirectional"))
      (node (ref "U7") (pin "P$13") (pinfunction "VDDA_P$13") (pintype "bidirectional"))
      (node (ref "U7") (pin "P$19") (pinfunction "VDD_P$19") (pintype "bidirectional"))
      (node (ref "U7") (pin "P$32") (pinfunction "VDD_P$32") (pintype "bidirectional"))
      (node (ref "U7") (pin "P$48") (pinfunction "VDD_P$48") (pintype "bidirectional"))
      (node (ref "U7") (pin "P$64") (pinfunction "VDD_P$64") (pintype "bidirectional"))
      (node (ref "U8") (pin "P$23") (pinfunction "VDD_P$23") (pintype "power_in"))
    )
    (net (code "56") (name "5V") (class "Default")
      (node (ref "C1") (pin "P$1") (pinfunction "+_P$1") (pintype "passive"))
      (node (ref "C8") (pin "P$1") (pinfunction "+_P$1") (pintype "passive"))
      (node (ref "C9") (pin "P$1") (pinfunction "+_P$1") (pintype "passive"))
      (node (ref "J1") (pin "2") (pinfunction "2_2") (pintype "passive"))
      (node (ref "L1") (pin "P$1") (pinfunction "1_P$1") (pintype "passive"))
      (node (ref "P1") (pin "VCC") (pinfunction "VCC_VCC") (pintype "passive"))
      (node (ref "P2") (pin "VCC") (pinfunction "VCC_VCC") (pintype "passive"))
      (node (ref "U1") (pin "P$3") (pinfunction "VIN_P$3") (pintype "bidirectional"))
      (node (ref "U2") (pin "P$4") (pinfunction "FEEDBACK_P$4") (pintype "bidirectional"))
      (node (ref "U6") (pin "P$13") (pinfunction "4~{OE}_P$13") (pintype "bidirectional"))
      (node (ref "U6") (pin "P$14") (pinfunction "VCC_P$14") (pintype "bidirectional"))
    )
    (net (code "57") (name "GND") (class "Default")
      (node (ref "C1") (pin "P$2") (pinfunction "-_P$2") (pintype "passive"))
      (node (ref "C10") (pin "1") (pinfunction "1_1") (pintype "passive"))
      (node (ref "C11") (pin "1") (pinfunction "1_1") (pintype "passive"))
      (node (ref "C12") (pin "1") (pinfunction "1_1") (pintype "passive"))
      (node (ref "C13") (pin "1") (pinfunction "1_1") (pintype "passive"))
      (node (ref "C14") (pin "1") (pinfunction "1_1") (pintype "passive"))
      (node (ref "C15") (pin "1") (pinfunction "1_1") (pintype "passive"))
      (node (ref "C16") (pin "1") (pinfunction "1_1") (pintype "passive"))
      (node (ref "C17") (pin "2") (pinfunction "2_2") (pintype "passive"))
      (node (ref "C18") (pin "2") (pinfunction "2_2") (pintype "passive"))
      (node (ref "C19") (pin "2") (pinfunction "2_2") (pintype "passive"))
      (node (ref "C2") (pin "P$2") (pinfunction "-_P$2") (pintype "passive"))
      (node (ref "C20") (pin "2") (pinfunction "2_2") (pintype "passive"))
      (node (ref "C21") (pin "2") (pinfunction "2_2") (pintype "passive"))
      (node (ref "C22") (pin "2") (pinfunction "2_2") (pintype "passive"))
      (node (ref "C23") (pin "2") (pinfunction "2_2") (pintype "passive"))
      (node (ref "C24") (pin "2") (pinfunction "2_2") (pintype "passive"))
      (node (ref "C25") (pin "1") (pinfunction "1_1") (pintype "passive"))
      (node (ref "C3") (pin "P$2") (pinfunction "-_P$2") (pintype "passive"))
      (node (ref "C4") (pin "P$2") (pinfunction "-_P$2") (pintype "passive"))
      (node (ref "C46") (pin "2") (pinfunction "2_2") (pintype "passive"))
      (node (ref "C48") (pin "2") (pinfunction "2_2") (pintype "passive"))
      (node (ref "C49") (pin "1") (pinfunction "1_1") (pintype "passive"))
      (node (ref "C5") (pin "P$2") (pinfunction "-_P$2") (pintype "passive"))
      (node (ref "C51") (pin "2") (pinfunction "2_2") (pintype "passive"))
      (node (ref "C55") (pin "2") (pinfunction "2_2") (pintype "passive"))
      (node (ref "C56") (pin "2") (pinfunction "2_2") (pintype "passive"))
      (node (ref "C57") (pin "2") (pinfunction "2_2") (pintype "passive"))
      (node (ref "C58") (pin "2") (pinfunction "2_2") (pintype "passive"))
      (node (ref "C59") (pin "2") (pinfunction "2_2") (pintype "passive"))
      (node (ref "C6") (pin "2") (pinfunction "2_2") (pintype "passive"))
      (node (ref "C61") (pin "2") (pinfunction "2_2") (pintype "passive"))
      (node (ref "C63") (pin "1") (pinfunction "1_1") (pintype "passive"))
      (node (ref "C65") (pin "2") (pinfunction "2_2") (pintype "passive"))
      (node (ref "C66") (pin "2") (pinfunction "2_2") (pintype "passive"))
      (node (ref "C67") (pin "2") (pinfunction "2_2") (pintype "passive"))
      (node (ref "C68") (pin "1") (pinfunction "1_1") (pintype "passive"))
      (node (ref "C7") (pin "2") (pinfunction "2_2") (pintype "passive"))
      (node (ref "C74") (pin "1") (pinfunction "1_1") (pintype "passive"))
      (node (ref "C75") (pin "2") (pinfunction "2_2") (pintype "passive"))
      (node (ref "C76") (pin "2") (pinfunction "2_2") (pintype "passive"))
      (node (ref "C77") (pin "2") (pinfunction "2_2") (pintype "passive"))
      (node (ref "C8") (pin "P$2") (pinfunction "-_P$2") (pintype "passive"))
      (node (ref "C9") (pin "P$2") (pinfunction "-_P$2") (pintype "passive"))
      (node (ref "D1") (pin "A") (pinfunction "A_A") (pintype "bidirectional"))
      (node (ref "J1") (pin "3") (pinfunction "3_3") (pintype "passive"))
      (node (ref "J4") (pin "4") (pinfunction "4_4") (pintype "passive"))
      (node (ref "J6") (pin "P$3") (pinfunction "GND_P$3") (pintype "bidirectional"))
      (node (ref "J6") (pin "P$6") (pinfunction "GND_P$6") (pintype "bidirectional"))
      (node (ref "J7") (pin "1") (pinfunction "1_1") (pintype "passive"))
      (node (ref "JP1") (pin "1") (pinfunction "O_1") (pintype "passive"))
      (node (ref "LED1") (pin "C") (pinfunction "C_C") (pintype "passive"))
      (node (ref "LED2") (pin "C") (pinfunction "C_C") (pintype "passive"))
      (node (ref "LED3") (pin "C") (pinfunction "C_C") (pintype "passive"))
      (node (ref "LED4") (pin "C") (pinfunction "C_C") (pintype "passive"))
      (node (ref "P1") (pin "GND") (pinfunction "GND_GND") (pintype "passive"))
      (node (ref "P2") (pin "GND") (pinfunction "GND_GND") (pintype "passive"))
      (node (ref "P3") (pin "P$10") (pinfunction "GND_P$10") (pintype "bidirectional"))
      (node (ref "P3") (pin "P$12") (pinfunction "GND_P$12") (pintype "bidirectional"))
      (node (ref "P3") (pin "P$14") (pinfunction "GND_P$14") (pintype "bidirectional"))
      (node (ref "P3") (pin "P$16") (pinfunction "GND_P$16") (pintype "bidirectional"))
      (node (ref "P3") (pin "P$18") (pinfunction "GND_P$18") (pintype "bidirectional"))
      (node (ref "P3") (pin "P$20") (pinfunction "GND_P$20") (pintype "bidirectional"))
      (node (ref "P3") (pin "P$4") (pinfunction "GND_P$4") (pintype "bidirectional"))
      (node (ref "P3") (pin "P$6") (pinfunction "GND_P$6") (pintype "bidirectional"))
      (node (ref "P3") (pin "P$8") (pinfunction "GND_P$8") (pintype "bidirectional"))
      (node (ref "Q2") (pin "P$1") (pinfunction "S1_P$1") (pintype "bidirectional"))
      (node (ref "Q2") (pin "P$2") (pinfunction "S1_P$2") (pintype "bidirectional"))
      (node (ref "Q2") (pin "P$3") (pinfunction "S1_P$3") (pintype "bidirectional"))
      (node (ref "R10") (pin "2") (pinfunction "2_2") (pintype "passive"))
      (node (ref "R16") (pin "2") (pinfunction "2_2") (pintype "passive"))
      (node (ref "R17") (pin "1") (pinfunction "1_1") (pintype "passive"))
      (node (ref "R18") (pin "1") (pinfunction "1_1") (pintype "passive"))
      (node (ref "R19") (pin "1") (pinfunction "1_1") (pintype "passive"))
      (node (ref "R20") (pin "1") (pinfunction "1_1") (pintype "passive"))
      (node (ref "R21") (pin "1") (pinfunction "1_1") (pintype "passive"))
      (node (ref "R24") (pin "1") (pinfunction "1_1") (pintype "passive"))
      (node (ref "R42") (pin "1") (pinfunction "1_1") (pintype "passive"))
      (node (ref "R49") (pin "1") (pinfunction "1_1") (pintype "passive"))
      (node (ref "R51") (pin "2") (pinfunction "2_2") (pintype "passive"))
      (node (ref "R71") (pin "2") (pinfunction "2_2") (pintype "passive"))
      (node (ref "R73") (pin "1") (pinfunction "1_1") (pintype "passive"))
      (node (ref "R75") (pin "2") (pinfunction "2_2") (pintype "passive"))
      (node (ref "R77") (pin "2") (pinfunction "2_2") (pintype "passive"))
      (node (ref "R78") (pin "2") (pinfunction "2_2") (pintype "passive"))
      (node (ref "R9") (pin "2") (pinfunction "2_2") (pintype "passive"))
      (node (ref "RT2") (pin "2") (pinfunction "2_2") (pintype "passive"))
      (node (ref "RT3") (pin "2") (pinfunction "2_2") (pintype "passive"))
      (node (ref "RT4") (pin "2") (pinfunction "2_2") (pintype "passive"))
      (node (ref "RT5") (pin "2") (pinfunction "2_2") (pintype "passive"))
      (node (ref "S1") (pin "P$3") (pinfunction "P_P$3") (pintype "passive"))
      (node (ref "S1") (pin "P$4") (pinfunction "P_P$4") (pintype "passive"))
      (node (ref "U$1") (pin "P$1") (pinfunction "GND_P$1") (pintype "bidirectional"))
      (node (ref "U1") (pin "P$1") (pinfunction "ADJ/GND_P$1") (pintype "bidirectional"))
      (node (ref "U10") (pin "GND") (pinfunction "GND_GND") (pintype "bidirectional"))
      (node (ref "U13") (pin "P$6") (pinfunction "VSS_P$6") (pintype "bidirectional"))
      (node (ref "U13") (pin "P$GND") (pinfunction "GNDPAD_P$GND") (pintype "bidirectional"))
      (node (ref "U14") (pin "7") (pinfunction "GND_7") (pintype "power_in"))
      (node (ref "U14") (pin "9") (pinfunction "GND_9") (pintype "power_in"))
      (node (ref "U15") (pin "P$24") (pinfunction "PGND_P$24") (pintype "bidirectional"))
      (node (ref "U15") (pin "P$33") (pinfunction "PGND_P$33") (pintype "bidirectional"))
      (node (ref "U15") (pin "P$34") (pinfunction "PGND_P$34") (pintype "bidirectional"))
      (node (ref "U15") (pin "P$35") (pinfunction "PGND_P$35") (pintype "bidirectional"))
      (node (ref "U15") (pin "P$36") (pinfunction "PGND_P$36") (pintype "bidirectional"))
      (node (ref "U15") (pin "P$37") (pinfunction "PGND_P$37") (pintype "bidirectional"))
      (node (ref "U15") (pin "P$38") (pinfunction "PGND_P$38") (pintype "bidirectional"))
      (node (ref "U15") (pin "P$39") (pinfunction "PGND_P$39") (pintype "bidirectional"))
      (node (ref "U15") (pin "P$40") (pinfunction "PGND_P$40") (pintype "bidirectional"))
      (node (ref "U15") (pin "P$41") (pinfunction "PGND_P$41") (pintype "bidirectional"))
      (node (ref "U15") (pin "P$9") (pinfunction "VSS_P$9") (pintype "bidirectional"))
      (node (ref "U15") (pin "P$GND") (pinfunction "VSS_P$GND") (pintype "bidirectional"))
      (node (ref "U2") (pin "P$3") (pinfunction "GND_P$3") (pintype "bidirectional"))
      (node (ref "U2") (pin "P$5") (pinfunction "~{ON/OFF}_P$5") (pintype "bidirectional"))
      (node (ref "U2") (pin "P$6") (pinfunction "GND_P$6") (pintype "bidirectional"))
      (node (ref "U2") (pin "P$7") (pinfunction "GND_P$7") (pintype "bidirectional"))
      (node (ref "U2") (pin "P$8") (pinfunction "GND_P$8") (pintype "bidirectional"))
      (node (ref "U3") (pin "P$23") (pinfunction "GND_P$23") (pintype "power_in"))
      (node (ref "U3") (pin "P$24") (pinfunction "GND_P$24") (pintype "power_in"))
      (node (ref "U3") (pin "P$25") (pinfunction "GND_P$25") (pintype "power_in"))
      (node (ref "U3") (pin "P$26") (pinfunction "GND_P$26") (pintype "power_in"))
      (node (ref "U3") (pin "P$5") (pinfunction "GND_P$5") (pintype "power_in"))
      (node (ref "U3") (pin "P$6") (pinfunction "GND_P$6") (pintype "power_in"))
      (node (ref "U3") (pin "P$7") (pinfunction "GND_P$7") (pintype "power_in"))
      (node (ref "U3") (pin "P$8") (pinfunction "GND_P$8") (pintype "power_in"))
      (node (ref "U4") (pin "P$23") (pinfunction "GND_P$23") (pintype "power_in"))
      (node (ref "U4") (pin "P$24") (pinfunction "GND_P$24") (pintype "power_in"))
      (node (ref "U4") (pin "P$25") (pinfunction "GND_P$25") (pintype "power_in"))
      (node (ref "U4") (pin "P$26") (pinfunction "GND_P$26") (pintype "power_in"))
      (node (ref "U4") (pin "P$5") (pinfunction "GND_P$5") (pintype "power_in"))
      (node (ref "U4") (pin "P$6") (pinfunction "GND_P$6") (pintype "power_in"))
      (node (ref "U4") (pin "P$7") (pinfunction "GND_P$7") (pintype "power_in"))
      (node (ref "U4") (pin "P$8") (pinfunction "GND_P$8") (pintype "power_in"))
      (node (ref "U5") (pin "P$1") (pinfunction "1~{OE}_P$1") (pintype "bidirectional"))
      (node (ref "U5") (pin "P$10") (pinfunction "3~{OE}_P$10") (pintype "bidirectional"))
      (node (ref "U5") (pin "P$13") (pinfunction "4~{OE}_P$13") (pintype "bidirectional"))
      (node (ref "U5") (pin "P$4") (pinfunction "2~{OE}_P$4") (pintype "bidirectional"))
      (node (ref "U5") (pin "P$7") (pinfunction "GND_P$7") (pintype "bidirectional"))
      (node (ref "U6") (pin "P$1") (pinfunction "1~{OE}_P$1") (pintype "bidirectional"))
      (node (ref "U6") (pin "P$10") (pinfunction "3~{OE}_P$10") (pintype "bidirectional"))
      (node (ref "U6") (pin "P$12") (pinfunction "4A_P$12") (pintype "bidirectional"))
      (node (ref "U6") (pin "P$4") (pinfunction "2~{OE}_P$4") (pintype "bidirectional"))
      (node (ref "U6") (pin "P$7") (pinfunction "GND_P$7") (pintype "bidirectional"))
      (node (ref "U7") (pin "P$12") (pinfunction "VSSA_P$12") (pintype "bidirectional"))
      (node (ref "U7") (pin "P$18") (pinfunction "VSS_P$18") (pintype "bidirectional"))
      (node (ref "U7") (pin "P$63") (pinfunction "VSS_P$63") (pintype "bidirectional"))
      (node (ref "U8") (pin "P$1") (pinfunction "GND_P$1") (pintype "power_in"))
      (node (ref "U8") (pin "P$24") (pinfunction "GND_P$24") (pintype "power_in"))
      (node (ref "Z3") (pin "1") (pinfunction "A_1") (pintype "passive"))
      (node (ref "Z4") (pin "1") (pinfunction "A_1") (pintype "passive"))
      (node (ref "Z5") (pin "1") (pinfunction "A_1") (pintype "passive"))
    )
    (net (code "58") (name "Net-(C11-Pad2)") (class "Default")
      (node (ref "C11") (pin "2") (pinfunction "2_2") (pintype "passive"))
      (node (ref "R82") (pin "2") (pinfunction "2_2") (pintype "passive"))
    )
    (net (code "59") (name "Net-(C12-Pad2)") (class "Default")
      (node (ref "C12") (pin "2") (pinfunction "2_2") (pintype "passive"))
      (node (ref "R12") (pin "2") (pinfunction "2_2") (pintype "passive"))
      (node (ref "Y1") (pin "P$1") (pinfunction "P$1_P$1") (pintype "bidirectional"))
    )
    (net (code "60") (name "Net-(C13-Pad2)") (class "Default")
      (node (ref "C13") (pin "2") (pinfunction "2_2") (pintype "passive"))
      (node (ref "R13") (pin "2") (pinfunction "2_2") (pintype "passive"))
      (node (ref "Y1") (pin "P$2") (pinfunction "P$2_P$2") (pintype "bidirectional"))
    )
    (net (code "61") (name "Net-(C14-Pad2)") (class "Default")
      (node (ref "C14") (pin "2") (pinfunction "2_2") (pintype "passive"))
      (node (ref "R14") (pin "2") (pinfunction "2_2") (pintype "passive"))
      (node (ref "Y2") (pin "P$1") (pinfunction "P$1_P$1") (pintype "bidirectional"))
    )
    (net (code "62") (name "Net-(C27-Pad1)") (class "Default")
      (node (ref "C27") (pin "1") (pinfunction "1_1") (pintype "passive"))
      (node (ref "J3") (pin "2") (pinfunction "2_2") (pintype "passive"))
    )
    (net (code "63") (name "Net-(C40-Pad1)") (class "Default")
      (node (ref "C40") (pin "1") (pinfunction "1_1") (pintype "passive"))
      (node (ref "R34") (pin "1") (pinfunction "1_1") (pintype "passive"))
    )
    (net (code "64") (name "Net-(C50-Pad1)") (class "Default")
      (node (ref "C50") (pin "1") (pinfunction "1_1") (pintype "passive"))
      (node (ref "C75") (pin "1") (pinfunction "1_1") (pintype "passive"))
      (node (ref "R79") (pin "2") (pinfunction "2_2") (pintype "passive"))
    )
    (net (code "65") (name "Net-(C50-Pad2)") (class "Default")
      (node (ref "C50") (pin "2") (pinfunction "2_2") (pintype "passive"))
      (node (ref "R44") (pin "1") (pinfunction "1_1") (pintype "passive"))
    )
    (net (code "66") (name "Net-(C51-Pad1)") (class "Default")
      (node (ref "C51") (pin "1") (pinfunction "1_1") (pintype "passive"))
      (node (ref "R50") (pin "1") (pinfunction "1_1") (pintype "passive"))
    )
    (net (code "67") (name "Net-(C60-Pad1)") (class "Default")
      (node (ref "C60") (pin "1") (pinfunction "1_1") (pintype "passive"))
      (node (ref "F2") (pin "2") (pinfunction "2_2") (pintype "bidirectional"))
      (node (ref "Q3") (pin "P$1") (pinfunction "S1_P$1") (pintype "bidirectional"))
      (node (ref "Q3") (pin "P$2") (pinfunction "S1_P$2") (pintype "bidirectional"))
      (node (ref "Q3") (pin "P$3") (pinfunction "S1_P$3") (pintype "bidirectional"))
      (node (ref "R52") (pin "1") (pinfunction "1_1") (pintype "passive"))
    )
    (net (code "68") (name "Net-(C60-Pad2)") (class "Default")
      (node (ref "C60") (pin "2") (pinfunction "2_2") (pintype "passive"))
      (node (ref "C62") (pin "1") (pinfunction "1_1") (pintype "passive"))
    )
    (net (code "69") (name "Net-(C63-Pad2)") (class "Default")
      (node (ref "C63") (pin "2") (pinfunction "2_2") (pintype "passive"))
      (node (ref "Q5") (pin "P$5") (pinfunction "D1_P$5") (pintype "bidirectional"))
      (node (ref "Q5") (pin "P$6") (pinfunction "D1_P$6") (pintype "bidirectional"))
      (node (ref "Q5") (pin "P$7") (pinfunction "D1_P$7") (pintype "bidirectional"))
      (node (ref "Q5") (pin "P$8") (pinfunction "D1_P$8") (pintype "bidirectional"))
      (node (ref "Q5") (pin "P$9") (pinfunction "D1_P$9") (pintype "bidirectional"))
      (node (ref "Q6") (pin "P$5") (pinfunction "D1_P$5") (pintype "bidirectional"))
      (node (ref "Q6") (pin "P$6") (pinfunction "D1_P$6") (pintype "bidirectional"))
      (node (ref "Q6") (pin "P$7") (pinfunction "D1_P$7") (pintype "bidirectional"))
      (node (ref "Q6") (pin "P$8") (pinfunction "D1_P$8") (pintype "bidirectional"))
      (node (ref "Q6") (pin "P$9") (pinfunction "D1_P$9") (pintype "bidirectional"))
      (node (ref "R67") (pin "2") (pinfunction "2_2") (pintype "passive"))
    )
    (net (code "70") (name "Net-(C70-Pad2)") (class "Default")
      (node (ref "C70") (pin "2") (pinfunction "2_2") (pintype "passive"))
      (node (ref "R69") (pin "2") (pinfunction "2_2") (pintype "passive"))
    )
    (net (code "71") (name "Net-(C73-Pad1)") (class "Default")
      (node (ref "C73") (pin "1") (pinfunction "1_1") (pintype "passive"))
      (node (ref "C74") (pin "2") (pinfunction "2_2") (pintype "passive"))
    )
    (net (code "72") (name "Net-(C76-Pad1)") (class "Default")
      (node (ref "C76") (pin "1") (pinfunction "1_1") (pintype "passive"))
      (node (ref "R79") (pin "1") (pinfunction "1_1") (pintype "passive"))
      (node (ref "R80") (pin "2") (pinfunction "2_2") (pintype "passive"))
    )
    (net (code "73") (name "Net-(C77-Pad1)") (class "Default")
      (node (ref "C77") (pin "1") (pinfunction "1_1") (pintype "passive"))
      (node (ref "R80") (pin "1") (pinfunction "1_1") (pintype "passive"))
      (node (ref "R81") (pin "2") (pinfunction "2_2") (pintype "passive"))
    )
    (net (code "74") (name "Net-(D2-PadC)") (class "Default")
      (node (ref "D2") (pin "C") (pinfunction "C_C") (pintype "passive"))
      (node (ref "R32") (pin "1") (pinfunction "1_1") (pintype "passive"))
    )
    (net (code "75") (name "Net-(D3-P$1)") (class "Default")
      (node (ref "D3") (pin "1") (pinfunction "P$1_1") (pintype "input"))
      (node (ref "R43") (pin "2") (pinfunction "2_2") (pintype "passive"))
    )
    (net (code "76") (name "Net-(D3-P$3)") (class "Default")
      (node (ref "D3") (pin "3") (pinfunction "P$3_3") (pintype "output"))
      (node (ref "U15") (pin "P$1") (pinfunction "BAT_P$1") (pintype "bidirectional"))
    )
    (net (code "77") (name "Net-(D5-C)") (class "Default")
      (node (ref "D5") (pin "D") (pinfunction "C_D") (pintype "passive"))
      (node (ref "D6") (pin "C") (pinfunction "C_C") (pintype "passive"))
    )
    (net (code "78") (name "Net-(F1-Pad2)") (class "Default")
      (node (ref "F1") (pin "2") (pinfunction "2_2") (pintype "bidirectional"))
      (node (ref "F2") (pin "1") (pinfunction "1_1") (pintype "bidirectional"))
      (node (ref "Q2") (pin "P$5") (pinfunction "D1_P$5") (pintype "bidirectional"))
      (node (ref "Q2") (pin "P$6") (pinfunction "D1_P$6") (pintype "bidirectional"))
      (node (ref "Q2") (pin "P$7") (pinfunction "D1_P$7") (pintype "bidirectional"))
      (node (ref "Q2") (pin "P$8") (pinfunction "D1_P$8") (pintype "bidirectional"))
      (node (ref "Q2") (pin "P$9") (pinfunction "D1_P$9") (pintype "bidirectional"))
    )
    (net (code "79") (name "Net-(J2-PWR)") (class "Default")
      (node (ref "C26") (pin "1") (pinfunction "1_1") (pintype "passive"))
      (node (ref "J2") (pin "VIN0") (pinfunction "PWR_VIN0") (pintype "bidirectional"))
      (node (ref "Q1") (pin "7") (pinfunction "D_7") (pintype "bidirectional"))
      (node (ref "Q1") (pin "8") (pinfunction "D_8") (pintype "bidirectional"))
      (node (ref "U9") (pin "P$9") (pinfunction "AD_P$9") (pintype "bidirectional"))
    )
    (net (code "80") (name "Net-(J4-Pad2)") (class "Default")
      (node (ref "J4") (pin "2") (pinfunction "2_2") (pintype "passive"))
      (node (ref "R38") (pin "1") (pinfunction "1_1") (pintype "passive"))
      (node (ref "R46") (pin "1") (pinfunction "1_1") (pintype "passive"))
    )
    (net (code "81") (name "Net-(J4-Pad3)") (class "Default")
      (node (ref "J4") (pin "3") (pinfunction "3_3") (pintype "passive"))
      (node (ref "R41") (pin "2") (pinfunction "2_2") (pintype "passive"))
      (node (ref "R47") (pin "1") (pinfunction "1_1") (pintype "passive"))
    )
    (net (code "82") (name "Net-(JP1-P)") (class "Default")
      (node (ref "JP1") (pin "2") (pinfunction "P_2") (pintype "passive"))
      (node (ref "R11") (pin "1") (pinfunction "1_1") (pintype "passive"))
    )
    (net (code "83") (name "Net-(JP2-O)") (class "Default")
      (node (ref "F3") (pin "2") (pinfunction "2_2") (pintype "bidirectional"))
      (node (ref "JP2") (pin "1") (pinfunction "O_1") (pintype "passive"))
    )
    (net (code "84") (name "Net-(L1-2)") (class "Default")
      (node (ref "D1") (pin "C") (pinfunction "C_C") (pintype "bidirectional"))
      (node (ref "L1") (pin "P$2") (pinfunction "2_P$2") (pintype "passive"))
      (node (ref "U2") (pin "P$2") (pinfunction "OUTPUT_P$2") (pintype "bidirectional"))
    )
    (net (code "85") (name "Net-(L2-2)") (class "Default")
      (node (ref "C42") (pin "1") (pinfunction "1_1") (pintype "passive"))
      (node (ref "L2") (pin "P$2") (pinfunction "2_P$2") (pintype "passive"))
      (node (ref "U11") (pin "1") (pinfunction "SW_1") (pintype "bidirectional"))
    )
    (net (code "86") (name "Net-(L3-1)") (class "Default")
      (node (ref "C64") (pin "2") (pinfunction "2_2") (pintype "passive"))
      (node (ref "L3") (pin "P$1") (pinfunction "1_P$1") (pintype "passive"))
      (node (ref "Q7") (pin "P$5") (pinfunction "D1_P$5") (pintype "bidirectional"))
      (node (ref "Q7") (pin "P$6") (pinfunction "D1_P$6") (pintype "bidirectional"))
      (node (ref "Q7") (pin "P$7") (pinfunction "D1_P$7") (pintype "bidirectional"))
      (node (ref "Q7") (pin "P$8") (pinfunction "D1_P$8") (pintype "bidirectional"))
      (node (ref "Q7") (pin "P$9") (pinfunction "D1_P$9") (pintype "bidirectional"))
      (node (ref "U15") (pin "P$26") (pinfunction "PH_P$26") (pintype "bidirectional"))
    )
    (net (code "87") (name "Net-(L3-2)") (class "Default")
      (node (ref "C66") (pin "1") (pinfunction "1_1") (pintype "passive"))
      (node (ref "C69") (pin "2") (pinfunction "2_2") (pintype "passive"))
      (node (ref "L3") (pin "P$2") (pinfunction "2_P$2") (pintype "passive"))
      (node (ref "Q5") (pin "P$1") (pinfunction "S1_P$1") (pintype "bidirectional"))
      (node (ref "Q5") (pin "P$2") (pinfunction "S1_P$2") (pintype "bidirectional"))
      (node (ref "Q5") (pin "P$3") (pinfunction "S1_P$3") (pintype "bidirectional"))
      (node (ref "R70") (pin "2") (pinfunction "2_2") (pintype "passive"))
      (node (ref "U15") (pin "P$20") (pinfunction "HSRP_P$20") (pintype "bidirectional"))
    )
    (net (code "88") (name "Net-(LED1-PadA)") (class "Default")
      (node (ref "LED1") (pin "A") (pinfunction "A_A") (pintype "passive"))
      (node (ref "R22") (pin "1") (pinfunction "1_1") (pintype "passive"))
    )
    (net (code "89") (name "Net-(LED2-PadA)") (class "Default")
      (node (ref "LED2") (pin "A") (pinfunction "A_A") (pintype "passive"))
      (node (ref "R23") (pin "1") (pinfunction "1_1") (pintype "passive"))
    )
    (net (code "90") (name "Net-(LED3-PadA)") (class "Default")
      (node (ref "LED3") (pin "A") (pinfunction "A_A") (pintype "passive"))
      (node (ref "R25") (pin "1") (pinfunction "1_1") (pintype "passive"))
    )
    (net (code "91") (name "Net-(LED4-PadA)") (class "Default")
      (node (ref "LED4") (pin "A") (pinfunction "A_A") (pintype "passive"))
      (node (ref "R74") (pin "1") (pinfunction "1_1") (pintype "passive"))
    )
    (net (code "92") (name "Net-(LED7-PadC)") (class "Default")
      (node (ref "LED7") (pin "C") (pinfunction "C_C") (pintype "passive"))
      (node (ref "R77") (pin "1") (pinfunction "1_1") (pintype "passive"))
    )
    (net (code "93") (name "Net-(LED8-PadC)") (class "Default")
      (node (ref "LED8") (pin "C") (pinfunction "C_C") (pintype "passive"))
      (node (ref "R16") (pin "1") (pinfunction "1_1") (pintype "passive"))
    )
    (net (code "94") (name "Net-(P1-PadMOTOR+)") (class "Default")
      (node (ref "P1") (pin "MOTOR+") (pinfunction "MOTOR+_MOTOR+") (pintype "passive"))
      (node (ref "U3") (pin "P$1") (pinfunction "OUT1_P$1") (pintype "output"))
      (node (ref "U3") (pin "P$2") (pinfunction "OUT1_P$2") (pintype "output"))
      (node (ref "U3") (pin "P$3") (pinfunction "OUT1_P$3") (pintype "output"))
      (node (ref "U3") (pin "P$33") (pinfunction "OUT1_P$33") (pintype "output"))
      (node (ref "U3") (pin "P$34") (pinfunction "OUT1_P$34") (pintype "output"))
      (node (ref "U3") (pin "P$35") (pinfunction "OUT1_P$35") (pintype "output"))
      (node (ref "U3") (pin "P$36") (pinfunction "OUT1_P$36") (pintype "output"))
      (node (ref "U3") (pin "P$4") (pinfunction "OUT1_P$4") (pintype "output"))
    )
    (net (code "95") (name "Net-(P1-PadMOTOR-)") (class "Default")
      (node (ref "P1") (pin "MOTOR-") (pinfunction "MOTOR-_MOTOR-") (pintype "passive"))
      (node (ref "U3") (pin "P$15") (pinfunction "OUT2_P$15") (pintype "output"))
      (node (ref "U3") (pin "P$16") (pinfunction "OUT2_P$16") (pintype "output"))
      (node (ref "U3") (pin "P$17") (pinfunction "OUT2_P$17") (pintype "output"))
      (node (ref "U3") (pin "P$18") (pinfunction "OUT2_P$18") (pintype "output"))
      (node (ref "U3") (pin "P$19") (pinfunction "OUT2_P$19") (pintype "output"))
      (node (ref "U3") (pin "P$20") (pinfunction "OUT2_P$20") (pintype "output"))
      (node (ref "U3") (pin "P$21") (pinfunction "OUT2_P$21") (pintype "output"))
      (node (ref "U3") (pin "P$22") (pinfunction "OUT2_P$22") (pintype "output"))
    )
    (net (code "96") (name "Net-(P2-PadMOTOR+)") (class "Default")
      (node (ref "P2") (pin "MOTOR+") (pinfunction "MOTOR+_MOTOR+") (pintype "passive"))
      (node (ref "U4") (pin "P$1") (pinfunction "OUT1_P$1") (pintype "output"))
      (node (ref "U4") (pin "P$2") (pinfunction "OUT1_P$2") (pintype "output"))
      (node (ref "U4") (pin "P$3") (pinfunction "OUT1_P$3") (pintype "output"))
      (node (ref "U4") (pin "P$33") (pinfunction "OUT1_P$33") (pintype "output"))
      (node (ref "U4") (pin "P$34") (pinfunction "OUT1_P$34") (pintype "output"))
      (node (ref "U4") (pin "P$35") (pinfunction "OUT1_P$35") (pintype "output"))
      (node (ref "U4") (pin "P$36") (pinfunction "OUT1_P$36") (pintype "output"))
      (node (ref "U4") (pin "P$4") (pinfunction "OUT1_P$4") (pintype "output"))
    )
    (net (code "97") (name "Net-(P2-PadMOTOR-)") (class "Default")
      (node (ref "P2") (pin "MOTOR-") (pinfunction "MOTOR-_MOTOR-") (pintype "passive"))
      (node (ref "U4") (pin "P$15") (pinfunction "OUT2_P$15") (pintype "output"))
      (node (ref "U4") (pin "P$16") (pinfunction "OUT2_P$16") (pintype "output"))
      (node (ref "U4") (pin "P$17") (pinfunction "OUT2_P$17") (pintype "output"))
      (node (ref "U4") (pin "P$18") (pinfunction "OUT2_P$18") (pintype "output"))
      (node (ref "U4") (pin "P$19") (pinfunction "OUT2_P$19") (pintype "output"))
      (node (ref "U4") (pin "P$20") (pinfunction "OUT2_P$20") (pintype "output"))
      (node (ref "U4") (pin "P$21") (pinfunction "OUT2_P$21") (pintype "output"))
      (node (ref "U4") (pin "P$22") (pinfunction "OUT2_P$22") (pintype "output"))
    )
    (net (code "98") (name "Net-(P3-PadP$11)") (class "Default")
      (node (ref "P3") (pin "P$11") (pinfunction "P$11_P$11") (pintype "bidirectional"))
      (node (ref "R20") (pin "2") (pinfunction "2_2") (pintype "passive"))
    )
    (net (code "99") (name "Net-(P3-PadP$17)") (class "Default")
      (node (ref "P3") (pin "P$17") (pinfunction "P$17_P$17") (pintype "bidirectional"))
      (node (ref "R21") (pin "2") (pinfunction "2_2") (pintype "passive"))
    )
    (net (code "100") (name "Net-(P3-PadP$19)") (class "Default")
      (node (ref "P3") (pin "P$19") (pinfunction "P$19_P$19") (pintype "bidirectional"))
      (node (ref "R24") (pin "2") (pinfunction "2_2") (pintype "passive"))
    )
    (net (code "101") (name "Net-(Q1A-G)") (class "Default")
      (node (ref "Q1") (pin "2") (pinfunction "G_2") (pintype "bidirectional"))
      (node (ref "Q1") (pin "4") (pinfunction "G_4") (pintype "bidirectional"))
      (node (ref "U9") (pin "P$8") (pinfunction "~{AD-EN}_P$8") (pintype "bidirectional"))
    )
    (net (code "102") (name "Net-(Q1A-S)") (class "Default")
      (node (ref "Q1") (pin "1") (pinfunction "S_1") (pintype "bidirectional"))
      (node (ref "Q1") (pin "3") (pinfunction "S_3") (pintype "bidirectional"))
    )
    (net (code "103") (name "Net-(Q2-G1)") (class "Default")
      (node (ref "C55") (pin "1") (pinfunction "1_1") (pintype "passive"))
      (node (ref "Q2") (pin "P$4") (pinfunction "G1_P$4") (pintype "bidirectional"))
      (node (ref "R40") (pin "2") (pinfunction "2_2") (pintype "passive"))
      (node (ref "R51") (pin "1") (pinfunction "1_1") (pintype "passive"))
      (node (ref "R62") (pin "2") (pinfunction "2_2") (pintype "passive"))
    )
    (net (code "104") (name "Net-(Q3-D1-PadP$5)") (class "Default")
      (node (ref "Q3") (pin "P$5") (pinfunction "D1_P$5") (pintype "bidirectional"))
      (node (ref "Q3") (pin "P$6") (pinfunction "D1_P$6") (pintype "bidirectional"))
      (node (ref "Q3") (pin "P$7") (pinfunction "D1_P$7") (pintype "bidirectional"))
      (node (ref "Q3") (pin "P$8") (pinfunction "D1_P$8") (pintype "bidirectional"))
      (node (ref "Q3") (pin "P$9") (pinfunction "D1_P$9") (pintype "bidirectional"))
      (node (ref "Q4") (pin "P$5") (pinfunction "D1_P$5") (pintype "bidirectional"))
      (node (ref "Q4") (pin "P$6") (pinfunction "D1_P$6") (pintype "bidirectional"))
      (node (ref "Q4") (pin "P$7") (pinfunction "D1_P$7") (pintype "bidirectional"))
      (node (ref "Q4") (pin "P$8") (pinfunction "D1_P$8") (pintype "bidirectional"))
      (node (ref "Q4") (pin "P$9") (pinfunction "D1_P$9") (pintype "bidirectional"))
    )
    (net (code "105") (name "Net-(Q3-G1)") (class "Default")
      (node (ref "Q3") (pin "P$4") (pinfunction "G1_P$4") (pintype "bidirectional"))
      (node (ref "R52") (pin "2") (pinfunction "2_2") (pintype "passive"))
      (node (ref "R53") (pin "1") (pinfunction "1_1") (pintype "passive"))
    )
    (net (code "106") (name "Net-(Q4-G1)") (class "Default")
      (node (ref "Q4") (pin "P$4") (pinfunction "G1_P$4") (pintype "bidirectional"))
      (node (ref "R54") (pin "1") (pinfunction "1_1") (pintype "passive"))
      (node (ref "R55") (pin "2") (pinfunction "2_2") (pintype "passive"))
    )
    (net (code "107") (name "Net-(Q5-G1)") (class "Default")
      (node (ref "Q5") (pin "P$4") (pinfunction "G1_P$4") (pintype "bidirectional"))
      (node (ref "U15") (pin "P$27") (pinfunction "HIDRV_P$27") (pintype "bidirectional"))
    )
    (net (code "108") (name "Net-(Q6-G1)") (class "Default")
      (node (ref "Q6") (pin "P$4") (pinfunction "G1_P$4") (pintype "bidirectional"))
      (node (ref "Q8") (pin "P$5") (pinfunction "D1_P$5") (pintype "bidirectional"))
      (node (ref "Q8") (pin "P$6") (pinfunction "D1_P$6") (pintype "bidirectional"))
      (node (ref "Q8") (pin "P$7") (pinfunction "D1_P$7") (pintype "bidirectional"))
      (node (ref "Q8") (pin "P$8") (pinfunction "D1_P$8") (pintype "bidirectional"))
      (node (ref "Q8") (pin "P$9") (pinfunction "D1_P$9") (pintype "bidirectional"))
      (node (ref "R56") (pin "1") (pinfunction "1_1") (pintype "passive"))
      (node (ref "R59") (pin "2") (pinfunction "2_2") (pintype "passive"))
    )
    (net (code "109") (name "Net-(Q7-G1)") (class "Default")
      (node (ref "Q7") (pin "P$4") (pinfunction "G1_P$4") (pintype "bidirectional"))
      (node (ref "U15") (pin "P$25") (pinfunction "LODRV_P$25") (pintype "bidirectional"))
    )
    (net (code "110") (name "Net-(Q8-G1)") (class "Default")
      (node (ref "D6") (pin "A") (pinfunction "A_A") (pintype "passive"))
      (node (ref "Q8") (pin "P$4") (pinfunction "G1_P$4") (pintype "bidirectional"))
      (node (ref "R71") (pin "1") (pinfunction "1_1") (pintype "passive"))
    )
    (net (code "111") (name "Net-(R29-Pad2)") (class "Default")
      (node (ref "R29") (pin "2") (pinfunction "2_2") (pintype "passive"))
      (node (ref "RT1") (pin "1") (pinfunction "1_1") (pintype "passive"))
    )
    (net (code "112") (name "Net-(S2-P)") (class "Default")
      (node (ref "S2") (pin "P$3") (pinfunction "P_P$3") (pintype "passive"))
      (node (ref "U$1") (pin "P$2") (pinfunction "+12V_P$2") (pintype "bidirectional"))
    )
    (net (code "113") (name "Net-(U3-IN1)") (class "Default")
      (node (ref "R1") (pin "2") (pinfunction "2_2") (pintype "passive"))
      (node (ref "U3") (pin "P$9") (pinfunction "IN1_P$9") (pintype "input"))
    )
    (net (code "114") (name "Net-(U3-IN2)") (class "Default")
      (node (ref "R3") (pin "2") (pinfunction "2_2") (pintype "passive"))
      (node (ref "U3") (pin "P$10") (pinfunction "IN2_P$10") (pintype "input"))
    )
    (net (code "115") (name "Net-(U3-INH)") (class "Default")
      (node (ref "R5") (pin "1") (pinfunction "1_1") (pintype "passive"))
      (node (ref "U3") (pin "P$27") (pinfunction "INH_P$27") (pintype "bidirectional"))
    )
    (net (code "116") (name "Net-(U3-IS)") (class "Default")
      (node (ref "R7") (pin "1") (pinfunction "1_1") (pintype "passive"))
      (node (ref "U3") (pin "P$28") (pinfunction "IS_P$28") (pintype "bidirectional"))
    )
    (net (code "117") (name "Net-(U4-IN1)") (class "Default")
      (node (ref "R2") (pin "1") (pinfunction "1_1") (pintype "passive"))
      (node (ref "U4") (pin "P$9") (pinfunction "IN1_P$9") (pintype "input"))
    )
    (net (code "118") (name "Net-(U4-IN2)") (class "Default")
      (node (ref "R4") (pin "2") (pinfunction "2_2") (pintype "passive"))
      (node (ref "U4") (pin "P$10") (pinfunction "IN2_P$10") (pintype "input"))
    )
    (net (code "119") (name "Net-(U4-INH)") (class "Default")
      (node (ref "R6") (pin "1") (pinfunction "1_1") (pintype "passive"))
      (node (ref "U4") (pin "P$27") (pinfunction "INH_P$27") (pintype "bidirectional"))
    )
    (net (code "120") (name "Net-(U4-IS)") (class "Default")
      (node (ref "R8") (pin "1") (pinfunction "1_1") (pintype "passive"))
      (node (ref "U4") (pin "P$28") (pinfunction "IS_P$28") (pintype "bidirectional"))
    )
    (net (code "121") (name "Net-(U7-BOOT0)") (class "Default")
      (node (ref "R11") (pin "2") (pinfunction "2_2") (pintype "passive"))
      (node (ref "U7") (pin "P$60") (pinfunction "BOOT0_P$60") (pintype "bidirectional"))
    )
    (net (code "122") (name "Net-(U7-PB5)") (class "Default")
      (node (ref "LED7") (pin "A") (pinfunction "A_A") (pintype "passive"))
      (node (ref "U7") (pin "P$57") (pinfunction "PB5_P$57") (pintype "bidirectional"))
    )
    (net (code "123") (name "Net-(U7-PC11)") (class "Default")
      (node (ref "J8") (pin "1") (pinfunction "1_1") (pintype "passive"))
      (node (ref "U7") (pin "P$52") (pinfunction "PC11_P$52") (pintype "bidirectional"))
    )
    (net (code "124") (name "Net-(U7-PC13)") (class "Default")
      (node (ref "LED8") (pin "A") (pinfunction "A_A") (pintype "passive"))
      (node (ref "U7") (pin "P$2") (pinfunction "PC13_P$2") (pintype "bidirectional"))
    )
    (net (code "125") (name "Net-(U7-PC14)") (class "Default")
      (node (ref "R12") (pin "1") (pinfunction "1_1") (pintype "passive"))
      (node (ref "U7") (pin "P$3") (pinfunction "PC14_P$3") (pintype "bidirectional"))
    )
    (net (code "126") (name "Net-(U7-PC15)") (class "Default")
      (node (ref "R13") (pin "1") (pinfunction "1_1") (pintype "passive"))
      (node (ref "U7") (pin "P$4") (pinfunction "PC15_P$4") (pintype "bidirectional"))
    )
    (net (code "127") (name "Net-(U7-PH0)") (class "Default")
      (node (ref "R14") (pin "1") (pinfunction "1_1") (pintype "passive"))
      (node (ref "U7") (pin "P$5") (pinfunction "PH0_P$5") (pintype "bidirectional"))
    )
    (net (code "128") (name "Net-(U7-PH1)") (class "Default")
      (node (ref "R15") (pin "1") (pinfunction "1_1") (pintype "passive"))
      (node (ref "U7") (pin "P$6") (pinfunction "PH1_P$6") (pintype "bidirectional"))
    )
    (net (code "129") (name "Net-(U7-VCAP_1)") (class "Default")
      (node (ref "C18") (pin "1") (pinfunction "1_1") (pintype "passive"))
      (node (ref "U7") (pin "P$31") (pinfunction "VCAP_1_P$31") (pintype "bidirectional"))
    )
    (net (code "130") (name "Net-(U7-VCAP_2)") (class "Default")
      (node (ref "C17") (pin "1") (pinfunction "1_1") (pintype "passive"))
      (node (ref "U7") (pin "P$47") (pinfunction "VCAP_2_P$47") (pintype "bidirectional"))
    )
    (net (code "131") (name "Net-(U8-AIO0)") (class "Default")
      (node (ref "R17") (pin "2") (pinfunction "2_2") (pintype "passive"))
      (node (ref "U8") (pin "P$4") (pinfunction "AIO0_P$4") (pintype "bidirectional"))
    )
    (net (code "132") (name "Net-(U8-AIO1)") (class "Default")
      (node (ref "R18") (pin "2") (pinfunction "2_2") (pintype "passive"))
      (node (ref "U8") (pin "P$3") (pinfunction "AIO1_P$3") (pintype "bidirectional"))
    )
    (net (code "133") (name "Net-(U8-AIO2)") (class "Default")
      (node (ref "R19") (pin "2") (pinfunction "2_2") (pintype "passive"))
      (node (ref "U8") (pin "P$2") (pinfunction "AIO2_P$2") (pintype "bidirectional"))
    )
    (net (code "134") (name "Net-(U8-PIO1)") (class "Default")
      (node (ref "R22") (pin "2") (pinfunction "2_2") (pintype "passive"))
      (node (ref "U8") (pin "P$10") (pinfunction "PIO1_P$10") (pintype "bidirectional"))
    )
    (net (code "135") (name "Net-(U8-PIO2)") (class "Default")
      (node (ref "R23") (pin "2") (pinfunction "2_2") (pintype "passive"))
      (node (ref "U8") (pin "P$11") (pinfunction "PIO2_P$11") (pintype "bidirectional"))
    )
    (net (code "136") (name "Net-(U8-PIO3)") (class "Default")
      (node (ref "R25") (pin "2") (pinfunction "2_2") (pintype "passive"))
      (node (ref "U8") (pin "P$12") (pinfunction "PIO3_P$12") (pintype "bidirectional"))
    )
    (net (code "137") (name "Net-(U9-AC1)") (class "Default")
      (node (ref "C27") (pin "2") (pinfunction "2_2") (pintype "passive"))
      (node (ref "C28") (pin "1") (pinfunction "1_1") (pintype "passive"))
      (node (ref "C29") (pin "1") (pinfunction "1_1") (pintype "passive"))
      (node (ref "C30") (pin "1") (pinfunction "1_1") (pintype "passive"))
      (node (ref "C34") (pin "1") (pinfunction "1_1") (pintype "passive"))
      (node (ref "U9") (pin "P$2") (pinfunction "AC1_P$2") (pintype "bidirectional"))
    )
    (net (code "138") (name "Net-(U9-AC2)") (class "Default")
      (node (ref "C28") (pin "2") (pinfunction "2_2") (pintype "passive"))
      (node (ref "C31") (pin "1") (pinfunction "1_1") (pintype "passive"))
      (node (ref "C32") (pin "1") (pinfunction "1_1") (pintype "passive"))
      (node (ref "C33") (pin "1") (pinfunction "1_1") (pintype "passive"))
      (node (ref "J3") (pin "1") (pinfunction "1_1") (pintype "passive"))
      (node (ref "U9") (pin "P$19") (pinfunction "AC2_P$19") (pintype "bidirectional"))
    )
    (net (code "139") (name "Net-(U9-BOOT1)") (class "Default")
      (node (ref "C30") (pin "2") (pinfunction "2_2") (pintype "passive"))
      (node (ref "U9") (pin "P$3") (pinfunction "BOOT1_P$3") (pintype "bidirectional"))
    )
    (net (code "140") (name "Net-(U9-BOOT2)") (class "Default")
      (node (ref "C31") (pin "2") (pinfunction "2_2") (pintype "passive"))
      (node (ref "U9") (pin "P$17") (pinfunction "BOOT2_P$17") (pintype "bidirectional"))
    )
    (net (code "141") (name "Net-(U9-CLAMP1)") (class "Default")
      (node (ref "C34") (pin "2") (pinfunction "2_2") (pintype "passive"))
      (node (ref "U9") (pin "P$5") (pinfunction "CLAMP1_P$5") (pintype "bidirectional"))
    )
    (net (code "142") (name "Net-(U9-CLAMP2)") (class "Default")
      (node (ref "C33") (pin "2") (pinfunction "2_2") (pintype "passive"))
      (node (ref "U9") (pin "P$16") (pinfunction "CLAMP2_P$16") (pintype "bidirectional"))
    )
    (net (code "143") (name "Net-(U9-COMM1)") (class "Default")
      (node (ref "C29") (pin "2") (pinfunction "2_2") (pintype "passive"))
      (node (ref "U9") (pin "P$6") (pinfunction "COMM1_P$6") (pintype "bidirectional"))
    )
    (net (code "144") (name "Net-(U9-COMM2)") (class "Default")
      (node (ref "C32") (pin "2") (pinfunction "2_2") (pintype "passive"))
      (node (ref "U9") (pin "P$15") (pinfunction "COMM2_P$15") (pintype "bidirectional"))
    )
    (net (code "145") (name "Net-(U9-FOD)") (class "Default")
      (node (ref "R26") (pin "2") (pinfunction "2_2") (pintype "passive"))
      (node (ref "R27") (pin "1") (pinfunction "1_1") (pintype "passive"))
      (node (ref "R28") (pin "1") (pinfunction "1_1") (pintype "passive"))
      (node (ref "U9") (pin "P$14") (pinfunction "FOD_P$14") (pintype "bidirectional"))
    )
    (net (code "146") (name "Net-(U9-ILIM)") (class "Default")
      (node (ref "R26") (pin "1") (pinfunction "1_1") (pintype "passive"))
      (node (ref "U9") (pin "P$12") (pinfunction "ILIM_P$12") (pintype "bidirectional"))
    )
    (net (code "147") (name "Net-(U9-RECT)") (class "Default")
      (node (ref "C35") (pin "1") (pinfunction "1_1") (pintype "passive"))
      (node (ref "R28") (pin "2") (pinfunction "2_2") (pintype "passive"))
      (node (ref "U9") (pin "P$18") (pinfunction "RECT_P$18") (pintype "bidirectional"))
    )
    (net (code "148") (name "Net-(U9-TS{slash}CTRL)") (class "Default")
      (node (ref "C37") (pin "1") (pinfunction "1_1") (pintype "passive"))
      (node (ref "R29") (pin "1") (pinfunction "1_1") (pintype "passive"))
      (node (ref "R30") (pin "1") (pinfunction "1_1") (pintype "passive"))
      (node (ref "R31") (pin "1") (pinfunction "1_1") (pintype "passive"))
      (node (ref "U9") (pin "P$13") (pinfunction "TS/CTRL_P$13") (pintype "bidirectional"))
    )
    (net (code "149") (name "Net-(U9-~{CHG})") (class "Default")
      (node (ref "R32") (pin "2") (pinfunction "2_2") (pintype "passive"))
      (node (ref "U9") (pin "P$7") (pinfunction "~{CHG}_P$7") (pintype "bidirectional"))
    )
    (net (code "150") (name "Net-(U11-CAP)") (class "Default")
      (node (ref "C41") (pin "2") (pinfunction "2_2") (pintype "passive"))
      (node (ref "U11") (pin "12") (pinfunction "CAP_12") (pintype "bidirectional"))
    )
    (net (code "151") (name "Net-(U11-FB)") (class "Default")
      (node (ref "R35") (pin "1") (pinfunction "1_1") (pintype "passive"))
      (node (ref "R36") (pin "2") (pinfunction "2_2") (pintype "passive"))
      (node (ref "U11") (pin "8") (pinfunction "FB_8") (pintype "bidirectional"))
    )
    (net (code "152") (name "Net-(U11-PWM{slash}SYNC)") (class "Default")
      (node (ref "C39") (pin "1") (pinfunction "1_1") (pintype "passive"))
      (node (ref "U11") (pin "4") (pinfunction "PWM/SYNC_4") (pintype "bidirectional"))
      (node (ref "U11") (pin "5") (pinfunction "VCC_5") (pintype "bidirectional"))
    )
    (net (code "153") (name "Net-(U11-RT)") (class "Default")
      (node (ref "R33") (pin "2") (pinfunction "2_2") (pintype "passive"))
      (node (ref "U11") (pin "6") (pinfunction "RT_6") (pintype "bidirectional"))
    )
    (net (code "154") (name "Net-(U11-VC)") (class "Default")
      (node (ref "C43") (pin "1") (pinfunction "1_1") (pintype "passive"))
      (node (ref "R34") (pin "2") (pinfunction "2_2") (pintype "passive"))
      (node (ref "U11") (pin "7") (pinfunction "VC_7") (pintype "bidirectional"))
    )
    (net (code "155") (name "Net-(U12-P$1)") (class "Default")
      (node (ref "C44") (pin "2") (pinfunction "2_2") (pintype "passive"))
      (node (ref "U12") (pin "1") (pinfunction "P$1_1") (pintype "bidirectional"))
      (node (ref "Z2") (pin "1") (pinfunction "A_1") (pintype "passive"))
    )
    (net (code "156") (name "Net-(U12-P$3)") (class "Default")
      (node (ref "C42") (pin "2") (pinfunction "2_2") (pintype "passive"))
      (node (ref "U12") (pin "3") (pinfunction "P$3_3") (pintype "bidirectional"))
    )
    (net (code "157") (name "Net-(U13-CD)") (class "Default")
      (node (ref "C48") (pin "1") (pinfunction "1_1") (pintype "passive"))
      (node (ref "U13") (pin "P$7") (pinfunction "CD_P$7") (pintype "bidirectional"))
    )
    (net (code "158") (name "Net-(U13-OUT)") (class "Default")
      (node (ref "R40") (pin "1") (pinfunction "1_1") (pintype "passive"))
      (node (ref "U13") (pin "P$8") (pinfunction "OUT_P$8") (pintype "bidirectional"))
    )
    (net (code "159") (name "Net-(U13-V1)") (class "Default")
      (node (ref "C49") (pin "2") (pinfunction "2_2") (pintype "passive"))
      (node (ref "C78") (pin "2") (pinfunction "2_2") (pintype "passive"))
      (node (ref "R41") (pin "1") (pinfunction "1_1") (pintype "passive"))
      (node (ref "U13") (pin "P$5") (pinfunction "V1_P$5") (pintype "bidirectional"))
    )
    (net (code "160") (name "Net-(U13-V2)") (class "Default")
      (node (ref "C47") (pin "2") (pinfunction "2_2") (pintype "passive"))
      (node (ref "C78") (pin "1") (pinfunction "1_1") (pintype "passive"))
      (node (ref "R38") (pin "2") (pinfunction "2_2") (pintype "passive"))
      (node (ref "U13") (pin "P$4") (pinfunction "V2_P$4") (pintype "bidirectional"))
    )
    (net (code "161") (name "Net-(U13-V3)") (class "Default")
      (node (ref "C47") (pin "1") (pinfunction "1_1") (pintype "passive"))
      (node (ref "R37") (pin "2") (pinfunction "2_2") (pintype "passive"))
      (node (ref "U13") (pin "P$2") (pinfunction "V4_P$2") (pintype "bidirectional"))
      (node (ref "U13") (pin "P$3") (pinfunction "V3_P$3") (pintype "bidirectional"))
    )
    (net (code "162") (name "Net-(U13-VDD)") (class "Default")
      (node (ref "C46") (pin "1") (pinfunction "1_1") (pintype "passive"))
      (node (ref "R39") (pin "1") (pinfunction "1_1") (pintype "passive"))
      (node (ref "U13") (pin "P$1") (pinfunction "VDD_P$1") (pintype "bidirectional"))
    )
    (net (code "163") (name "Net-(U14-IN+)") (class "Default")
      (node (ref "R44") (pin "2") (pinfunction "2_2") (pintype "passive"))
      (node (ref "U14") (pin "3") (pinfunction "IN+_3") (pintype "bidirectional"))
    )
    (net (code "164") (name "Net-(U14-IN-)") (class "Default")
      (node (ref "R50") (pin "2") (pinfunction "2_2") (pintype "passive"))
      (node (ref "U14") (pin "4") (pinfunction "IN-_4") (pintype "bidirectional"))
    )
    (net (code "165") (name "Net-(U15-ACFET)") (class "Default")
      (node (ref "R56") (pin "2") (pinfunction "2_2") (pintype "passive"))
      (node (ref "U15") (pin "P$29") (pinfunction "ACFET_P$29") (pintype "bidirectional"))
    )
    (net (code "166") (name "Net-(U15-ACP)") (class "Default")
      (node (ref "R61") (pin "2") (pinfunction "2_2") (pintype "passive"))
      (node (ref "U15") (pin "P$30") (pinfunction "ACP_P$30") (pintype "bidirectional"))
    )
    (net (code "167") (name "Net-(U15-AFEFUSE)") (class "Default")
      (node (ref "R62") (pin "1") (pinfunction "1_1") (pintype "passive"))
      (node (ref "U15") (pin "P$21") (pinfunction "AFEFUSE_P$21") (pintype "bidirectional"))
    )
    (net (code "168") (name "Net-(U15-ALERT{slash}BTP)") (class "Default")
      (node (ref "R66") (pin "1") (pinfunction "1_1") (pintype "passive"))
      (node (ref "U15") (pin "P$14") (pinfunction "ALERT/BTP_P$14") (pintype "bidirectional"))
    )
    (net (code "169") (name "Net-(U15-BTST)") (class "Default")
      (node (ref "C64") (pin "1") (pinfunction "1_1") (pintype "passive"))
      (node (ref "D4") (pin "C") (pinfunction "C_C") (pintype "passive"))
      (node (ref "U15") (pin "P$28") (pinfunction "BTST_P$28") (pintype "bidirectional"))
    )
    (net (code "170") (name "Net-(U15-CHG)") (class "Default")
      (node (ref "R53") (pin "2") (pinfunction "2_2") (pintype "passive"))
      (node (ref "U15") (pin "P$32") (pinfunction "CHG_P$32") (pintype "bidirectional"))
    )
    (net (code "171") (name "Net-(U15-DSG)") (class "Default")
      (node (ref "R54") (pin "2") (pinfunction "2_2") (pintype "passive"))
      (node (ref "U15") (pin "P$31") (pinfunction "DSG_P$31") (pintype "bidirectional"))
    )
    (net (code "172") (name "Net-(U15-PBI)") (class "Default")
      (node (ref "C56") (pin "1") (pinfunction "1_1") (pintype "passive"))
      (node (ref "U15") (pin "P$2") (pinfunction "PBI_P$2") (pintype "bidirectional"))
    )
    (net (code "173") (name "Net-(U15-REGN)") (class "Default")
      (node (ref "C65") (pin "1") (pinfunction "1_1") (pintype "passive"))
      (node (ref "D4") (pin "A") (pinfunction "A_A") (pintype "passive"))
      (node (ref "U15") (pin "P$23") (pinfunction "REGN_P$23") (pintype "bidirectional"))
    )
    (net (code "174") (name "Net-(U15-SMBC)") (class "Default")
      (node (ref "R60") (pin "1") (pinfunction "1_1") (pintype "passive"))
      (node (ref "U15") (pin "P$17") (pinfunction "SMBC_P$17") (pintype "bidirectional"))
    )
    (net (code "175") (name "Net-(U15-SMBD)") (class "Default")
      (node (ref "R58") (pin "1") (pinfunction "1_1") (pintype "passive"))
      (node (ref "U15") (pin "P$16") (pinfunction "SMBD_P$16") (pintype "bidirectional"))
    )
    (net (code "176") (name "Net-(U15-SRN)") (class "Default")
      (node (ref "C52") (pin "1") (pinfunction "1_1") (pintype "passive"))
      (node (ref "C58") (pin "1") (pinfunction "1_1") (pintype "passive"))
      (node (ref "R48") (pin "2") (pinfunction "2_2") (pintype "passive"))
      (node (ref "U15") (pin "P$7") (pinfunction "SRN_P$7") (pintype "bidirectional"))
    )
    (net (code "177") (name "Net-(U15-SRP)") (class "Default")
      (node (ref "C52") (pin "2") (pinfunction "2_2") (pintype "passive"))
      (node (ref "C59") (pin "1") (pinfunction "1_1") (pintype "passive"))
      (node (ref "R49") (pin "2") (pinfunction "2_2") (pintype "passive"))
      (node (ref "U15") (pin "P$8") (pinfunction "SRP_P$8") (pintype "bidirectional"))
    )
    (net (code "178") (name "Net-(U15-SYSPRES)") (class "Default")
      (node (ref "R57") (pin "1") (pinfunction "1_1") (pintype "passive"))
      (node (ref "U15") (pin "P$15") (pinfunction "SYSPRES_P$15") (pintype "bidirectional"))
    )
    (net (code "179") (name "Net-(U15-TS1)") (class "Default")
      (node (ref "RT2") (pin "1") (pinfunction "1_1") (pintype "passive"))
      (node (ref "U15") (pin "P$10") (pinfunction "TS1_P$10") (pintype "bidirectional"))
    )
    (net (code "180") (name "Net-(U15-TS2)") (class "Default")
      (node (ref "RT3") (pin "1") (pinfunction "1_1") (pintype "passive"))
      (node (ref "U15") (pin "P$11") (pinfunction "TS2_P$11") (pintype "bidirectional"))
    )
    (net (code "181") (name "Net-(U15-TS3)") (class "Default")
      (node (ref "RT4") (pin "1") (pinfunction "1_1") (pintype "passive"))
      (node (ref "U15") (pin "P$12") (pinfunction "TS3_P$12") (pintype "bidirectional"))
    )
    (net (code "182") (name "Net-(U15-TS4)") (class "Default")
      (node (ref "RT5") (pin "1") (pinfunction "1_1") (pintype "passive"))
      (node (ref "U15") (pin "P$13") (pinfunction "TS4_P$13") (pintype "bidirectional"))
    )
    (net (code "183") (name "Net-(U15-VC1)") (class "Default")
      (node (ref "C53") (pin "2") (pinfunction "2_2") (pintype "passive"))
      (node (ref "C57") (pin "1") (pinfunction "1_1") (pintype "passive"))
      (node (ref "R47") (pin "2") (pinfunction "2_2") (pintype "passive"))
      (node (ref "U15") (pin "P$6") (pinfunction "VC1_P$6") (pintype "bidirectional"))
    )
    (net (code "184") (name "Net-(U15-VC2)") (class "Default")
      (node (ref "C53") (pin "1") (pinfunction "1_1") (pintype "passive"))
      (node (ref "C54") (pin "2") (pinfunction "2_2") (pintype "passive"))
      (node (ref "R46") (pin "2") (pinfunction "2_2") (pintype "passive"))
      (node (ref "U15") (pin "P$5") (pinfunction "VC2_P$5") (pintype "bidirectional"))
    )
    (net (code "185") (name "Net-(U15-VC3)") (class "Default")
      (node (ref "C54") (pin "1") (pinfunction "1_1") (pintype "passive"))
      (node (ref "R45") (pin "2") (pinfunction "2_2") (pintype "passive"))
      (node (ref "U15") (pin "P$3") (pinfunction "VC4_P$3") (pintype "bidirectional"))
      (node (ref "U15") (pin "P$4") (pinfunction "VC3_P$4") (pintype "bidirectional"))
    )
    (net (code "186") (name "Net-(U15-VCC)") (class "Default")
      (node (ref "C68") (pin "2") (pinfunction "2_2") (pintype "passive"))
      (node (ref "R67") (pin "1") (pinfunction "1_1") (pintype "passive"))
      (node (ref "U15") (pin "P$22") (pinfunction "VCC_P$22") (pintype "bidirectional"))
    )
    (net (code "187") (name "Net-(U15-VFB)") (class "Default")
      (node (ref "C71") (pin "1") (pinfunction "1_1") (pintype "passive"))
      (node (ref "R72") (pin "1") (pinfunction "1_1") (pintype "passive"))
      (node (ref "R73") (pin "2") (pinfunction "2_2") (pintype "passive"))
      (node (ref "U15") (pin "P$18") (pinfunction "VFB_P$18") (pintype "bidirectional"))
    )
    (net (code "188") (name "Net-(Y2-P$2)") (class "Default")
      (node (ref "C15") (pin "2") (pinfunction "2_2") (pintype "passive"))
      (node (ref "R15") (pin "2") (pinfunction "2_2") (pintype "passive"))
      (node (ref "Y2") (pin "P$4") (pinfunction "P$2_P$4") (pintype "bidirectional"))
    )
    (net (code "189") (name "Net-(Z3-C)") (class "Default")
      (node (ref "R57") (pin "2") (pinfunction "2_2") (pintype "passive"))
      (node (ref "R65") (pin "1") (pinfunction "1_1") (pintype "passive"))
      (node (ref "Z3") (pin "2") (pinfunction "C_2") (pintype "passive"))
    )
    (net (code "190") (name "Net-(Z4-C)") (class "Default")
      (node (ref "R58") (pin "2") (pinfunction "2_2") (pintype "passive"))
      (node (ref "R64") (pin "1") (pinfunction "1_1") (pintype "passive"))
      (node (ref "Z4") (pin "2") (pinfunction "C_2") (pintype "passive"))
    )
    (net (code "191") (name "Net-(Z5-C)") (class "Default")
      (node (ref "R60") (pin "2") (pinfunction "2_2") (pintype "passive"))
      (node (ref "R63") (pin "1") (pinfunction "1_1") (pintype "passive"))
      (node (ref "Z5") (pin "2") (pinfunction "C_2") (pintype "passive"))
    )
    (net (code "192") (name "PGND") (class "Default")
      (node (ref "C26") (pin "2") (pinfunction "2_2") (pintype "passive"))
      (node (ref "C35") (pin "2") (pinfunction "2_2") (pintype "passive"))
      (node (ref "C36") (pin "2") (pinfunction "2_2") (pintype "passive"))
      (node (ref "C37") (pin "2") (pinfunction "2_2") (pintype "passive"))
      (node (ref "C38") (pin "2") (pinfunction "2_2") (pintype "passive"))
      (node (ref "C39") (pin "2") (pinfunction "2_2") (pintype "passive"))
      (node (ref "C40") (pin "2") (pinfunction "2_2") (pintype "passive"))
      (node (ref "C43") (pin "2") (pinfunction "2_2") (pintype "passive"))
      (node (ref "C44") (pin "1") (pinfunction "1_1") (pintype "passive"))
      (node (ref "C45") (pin "2") (pinfunction "2_2") (pintype "passive"))
      (node (ref "C70") (pin "1") (pinfunction "1_1") (pintype "passive"))
      (node (ref "C72") (pin "1") (pinfunction "1_1") (pintype "passive"))
      (node (ref "J2") (pin "GND") (pinfunction "GNDBREAK_GND") (pintype "bidirectional"))
      (node (ref "J2") (pin "P$4") (pinfunction "GND_P$4") (pintype "bidirectional"))
      (node (ref "Q7") (pin "P$1") (pinfunction "S1_P$1") (pintype "bidirectional"))
      (node (ref "Q7") (pin "P$2") (pinfunction "S1_P$2") (pintype "bidirectional"))
      (node (ref "Q7") (pin "P$3") (pinfunction "S1_P$3") (pintype "bidirectional"))
      (node (ref "R27") (pin "2") (pinfunction "2_2") (pintype "passive"))
      (node (ref "R30") (pin "2") (pinfunction "2_2") (pintype "passive"))
      (node (ref "R31") (pin "2") (pinfunction "2_2") (pintype "passive"))
      (node (ref "R33") (pin "1") (pinfunction "1_1") (pintype "passive"))
      (node (ref "R36") (pin "1") (pinfunction "1_1") (pintype "passive"))
      (node (ref "R68") (pin "2") (pinfunction "2_2") (pintype "passive"))
      (node (ref "R75") (pin "1") (pinfunction "1_1") (pintype "passive"))
      (node (ref "RT1") (pin "2") (pinfunction "2_2") (pintype "passive"))
      (node (ref "U11") (pin "10") (pinfunction "SGND_10") (pintype "bidirectional"))
      (node (ref "U11") (pin "13") (pinfunction "PGND_13") (pintype "bidirectional"))
      (node (ref "U11") (pin "2") (pinfunction "PGND_2") (pintype "bidirectional"))
      (node (ref "U11") (pin "P$1") (pinfunction "PGND_P$1") (pintype "bidirectional"))
      (node (ref "U11") (pin "P$2") (pinfunction "PGND_P$2") (pintype "bidirectional"))
      (node (ref "U11") (pin "P$3") (pinfunction "PGND_P$3") (pintype "bidirectional"))
      (node (ref "U11") (pin "P$4") (pinfunction "PGND_P$4") (pintype "bidirectional"))
      (node (ref "U11") (pin "P$5") (pinfunction "PGND_P$5") (pintype "bidirectional"))
      (node (ref "U11") (pin "P$6") (pinfunction "PGND_P$6") (pintype "bidirectional"))
      (node (ref "U12") (pin "2") (pinfunction "P$2_2") (pintype "bidirectional"))
      (node (ref "U9") (pin "P$1") (pinfunction "PGND_P$1") (pintype "bidirectional"))
      (node (ref "U9") (pin "P$10") (pinfunction "EN1_P$10") (pintype "bidirectional"))
      (node (ref "U9") (pin "P$11") (pinfunction "EN2_P$11") (pintype "bidirectional"))
      (node (ref "U9") (pin "P$20") (pinfunction "PGND_P$20") (pintype "bidirectional"))
      (node (ref "U9") (pin "P$21") (pinfunction "PGND_P$21") (pintype "bidirectional"))
      (node (ref "U9") (pin "P$22") (pinfunction "PGND_P$22") (pintype "bidirectional"))
      (node (ref "U9") (pin "P$23") (pinfunction "PGND_P$23") (pintype "bidirectional"))
      (node (ref "U9") (pin "P$24") (pinfunction "PGND_P$24") (pintype "bidirectional"))
      (node (ref "U9") (pin "P$25") (pinfunction "PGND_P$25") (pintype "bidirectional"))
      (node (ref "U9") (pin "P$26") (pinfunction "PGND_P$26") (pintype "bidirectional"))
      (node (ref "U9") (pin "P$27") (pinfunction "PGND_P$27") (pintype "bidirectional"))
      (node (ref "Z2") (pin "2") (pinfunction "C_2") (pintype "passive"))
    )
    (net (code "193") (name "VCC") (class "Default")
      (node (ref "C2") (pin "P$1") (pinfunction "+_P$1") (pintype "passive"))
      (node (ref "C4") (pin "P$1") (pinfunction "+_P$1") (pintype "passive"))
      (node (ref "C5") (pin "P$1") (pinfunction "+_P$1") (pintype "passive"))
      (node (ref "C6") (pin "1") (pinfunction "1_1") (pintype "passive"))
      (node (ref "C7") (pin "1") (pinfunction "1_1") (pintype "passive"))
      (node (ref "JP2") (pin "2") (pinfunction "P_2") (pintype "passive"))
      (node (ref "R76") (pin "1") (pinfunction "1_1") (pintype "passive"))
      (node (ref "U2") (pin "P$1") (pinfunction "VIN_P$1") (pintype "bidirectional"))
      (node (ref "U3") (pin "P$11") (pinfunction "VS_P$11") (pintype "power_in"))
      (node (ref "U3") (pin "P$12") (pinfunction "VS_P$12") (pintype "power_in"))
      (node (ref "U3") (pin "P$13") (pinfunction "VS_P$13") (pintype "power_in"))
      (node (ref "U3") (pin "P$14") (pinfunction "VS_P$14") (pintype "power_in"))
      (node (ref "U3") (pin "P$29") (pinfunction "VS_P$29") (pintype "power_in"))
      (node (ref "U3") (pin "P$30") (pinfunction "VS_P$30") (pintype "power_in"))
      (node (ref "U3") (pin "P$31") (pinfunction "VS_P$31") (pintype "power_in"))
      (node (ref "U3") (pin "P$32") (pinfunction "VS_P$32") (pintype "power_in"))
      (node (ref "U4") (pin "P$11") (pinfunction "VS_P$11") (pintype "power_in"))
      (node (ref "U4") (pin "P$12") (pinfunction "VS_P$12") (pintype "power_in"))
      (node (ref "U4") (pin "P$13") (pinfunction "VS_P$13") (pintype "power_in"))
      (node (ref "U4") (pin "P$14") (pinfunction "VS_P$14") (pintype "power_in"))
      (node (ref "U4") (pin "P$29") (pinfunction "VS_P$29") (pintype "power_in"))
      (node (ref "U4") (pin "P$30") (pinfunction "VS_P$30") (pintype "power_in"))
      (node (ref "U4") (pin "P$31") (pinfunction "VS_P$31") (pintype "power_in"))
      (node (ref "U4") (pin "P$32") (pinfunction "VS_P$32") (pintype "power_in"))
    )
    (net (code "194") (name "unconnected-(D3-P$2-Pad2)") (class "Default")
      (node (ref "D3") (pin "2") (pinfunction "P$2_2") (pintype "no_connect"))
    )
    (net (code "195") (name "unconnected-(J6-IRQ-PadP$8)") (class "Default")
      (node (ref "J6") (pin "P$8") (pinfunction "IRQ_P$8") (pintype "bidirectional"))
    )
    (net (code "196") (name "unconnected-(J6-RW-PadP$9)") (class "Default")
      (node (ref "J6") (pin "P$9") (pinfunction "RW_P$9") (pintype "bidirectional"))
    )
    (net (code "197") (name "unconnected-(U6-4Y-PadP$11)") (class "Default")
      (node (ref "U6") (pin "P$11") (pinfunction "4Y_P$11") (pintype "bidirectional"))
    )
    (net (code "198") (name "unconnected-(U7-PA10-PadP$43)") (class "Default")
      (node (ref "U7") (pin "P$43") (pinfunction "PA10_P$43") (pintype "bidirectional"))
    )
    (net (code "199") (name "unconnected-(U7-PA11-PadP$44)") (class "Default")
      (node (ref "U7") (pin "P$44") (pinfunction "PA11_P$44") (pintype "bidirectional"))
    )
    (net (code "200") (name "unconnected-(U7-PB14-PadP$35)") (class "Default")
      (node (ref "U7") (pin "P$35") (pinfunction "PB14_P$35") (pintype "bidirectional"))
    )
    (net (code "201") (name "unconnected-(U7-PB15-PadP$36)") (class "Default")
      (node (ref "U7") (pin "P$36") (pinfunction "PB15_P$36") (pintype "bidirectional"))
    )
    (net (code "202") (name "unconnected-(U7-PC10-PadP$51)") (class "Default")
      (node (ref "U7") (pin "P$51") (pinfunction "PC10_P$51") (pintype "bidirectional"))
    )
    (net (code "203") (name "unconnected-(U8-PIO4-PadP$13)") (class "Default")
      (node (ref "U8") (pin "P$13") (pinfunction "PIO4_P$13") (pintype "bidirectional"))
    )
    (net (code "204") (name "unconnected-(U8-PWM{slash}PIO7-PadP$19)") (class "Default")
      (node (ref "U8") (pin "P$19") (pinfunction "PWM/PIO7_P$19") (pintype "bidirectional"))
    )
    (net (code "205") (name "unconnected-(U8-RSVD-PadP$20)") (class "Default")
      (node (ref "U8") (pin "P$20") (pinfunction "RSVD_P$20") (pintype "no_connect"))
    )
    (net (code "206") (name "unconnected-(U8-SCL-PadP$22)") (class "Default")
      (node (ref "U8") (pin "P$22") (pinfunction "SCL_P$22") (pintype "bidirectional"))
    )
    (net (code "207") (name "unconnected-(U8-SDA-PadP$21)") (class "Default")
      (node (ref "U8") (pin "P$21") (pinfunction "SDA_P$21") (pintype "bidirectional"))
    )
    (net (code "208") (name "unconnected-(U8-SPI{slash}~{PIO}-PadP$17)") (class "Default")
      (node (ref "U8") (pin "P$17") (pinfunction "SPI/~{PIO}_P$17") (pintype "input"))
    )
    (net (code "209") (name "unconnected-(U10-PadDEN)") (class "Default")
      (node (ref "U10") (pin "DEN") (pinfunction "DEN_DEN") (pintype "bidirectional"))
    )
    (net (code "210") (name "unconnected-(U10-PadINT1)") (class "Default")
      (node (ref "U10") (pin "INT1") (pinfunction "INT1_INT1") (pintype "bidirectional"))
    )
    (net (code "211") (name "unconnected-(U10-PadINT2)") (class "Default")
      (node (ref "U10") (pin "INT2") (pinfunction "INT2_INT2") (pintype "bidirectional"))
    )
    (net (code "212") (name "unconnected-(U10-PadINTM)") (class "Default")
      (node (ref "U10") (pin "INTM") (pinfunction "INTM_INTM") (pintype "bidirectional"))
    )
    (net (code "213") (name "unconnected-(U10-PadRDY)") (class "Default")
      (node (ref "U10") (pin "RDY") (pinfunction "RDY_RDY") (pintype "bidirectional"))
    )
  )
)
